# Titan_Teknic_v1p01c.net
KiCad netlist of a schematic drawn in EAGLE
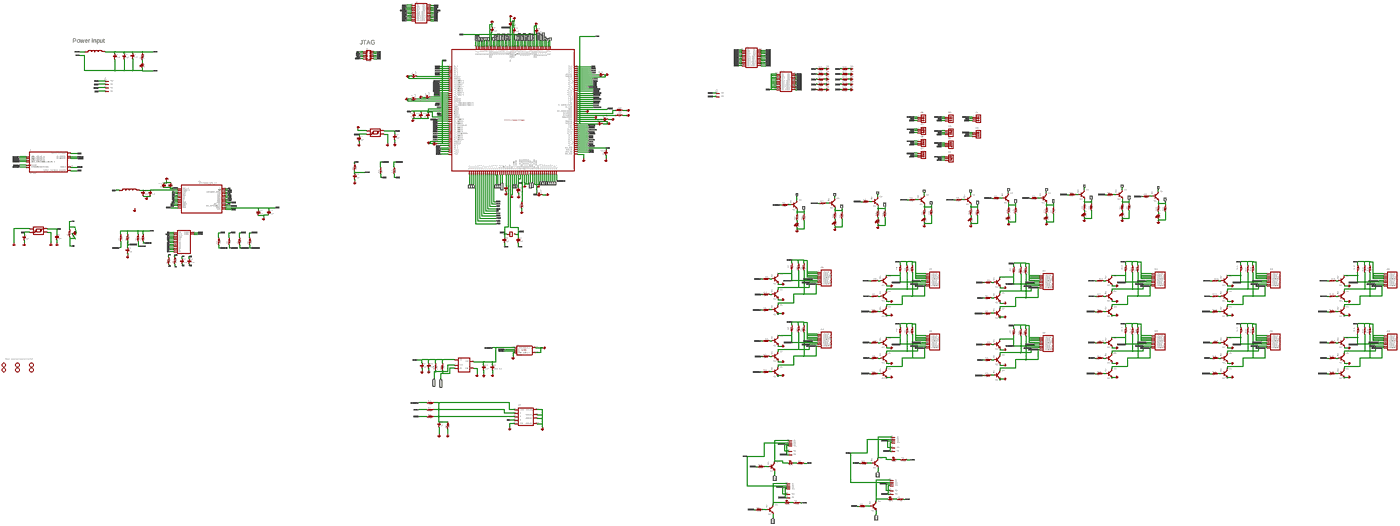
[diagram p0: schematic, sheet 1, overview]
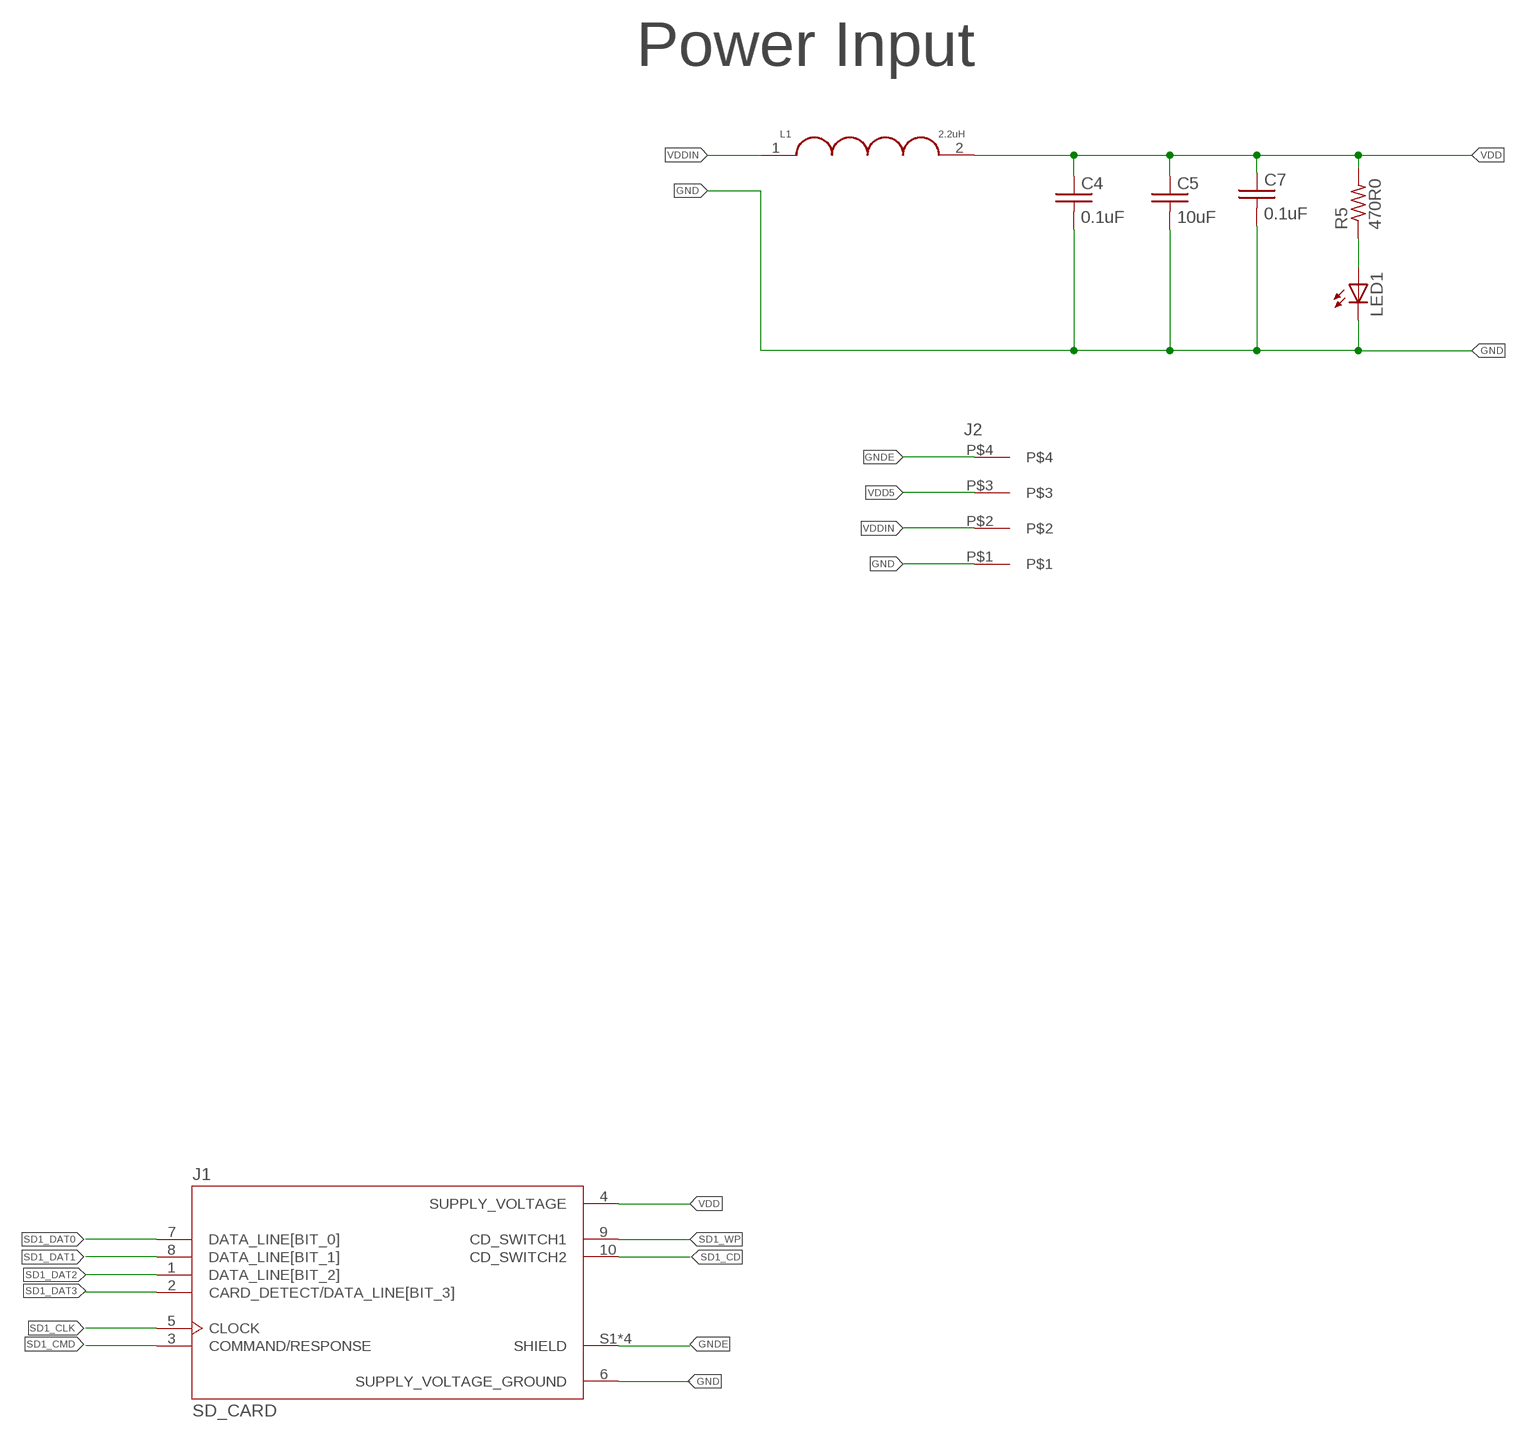
[diagram p1: schematic, sheet 1, part 1 of 9]
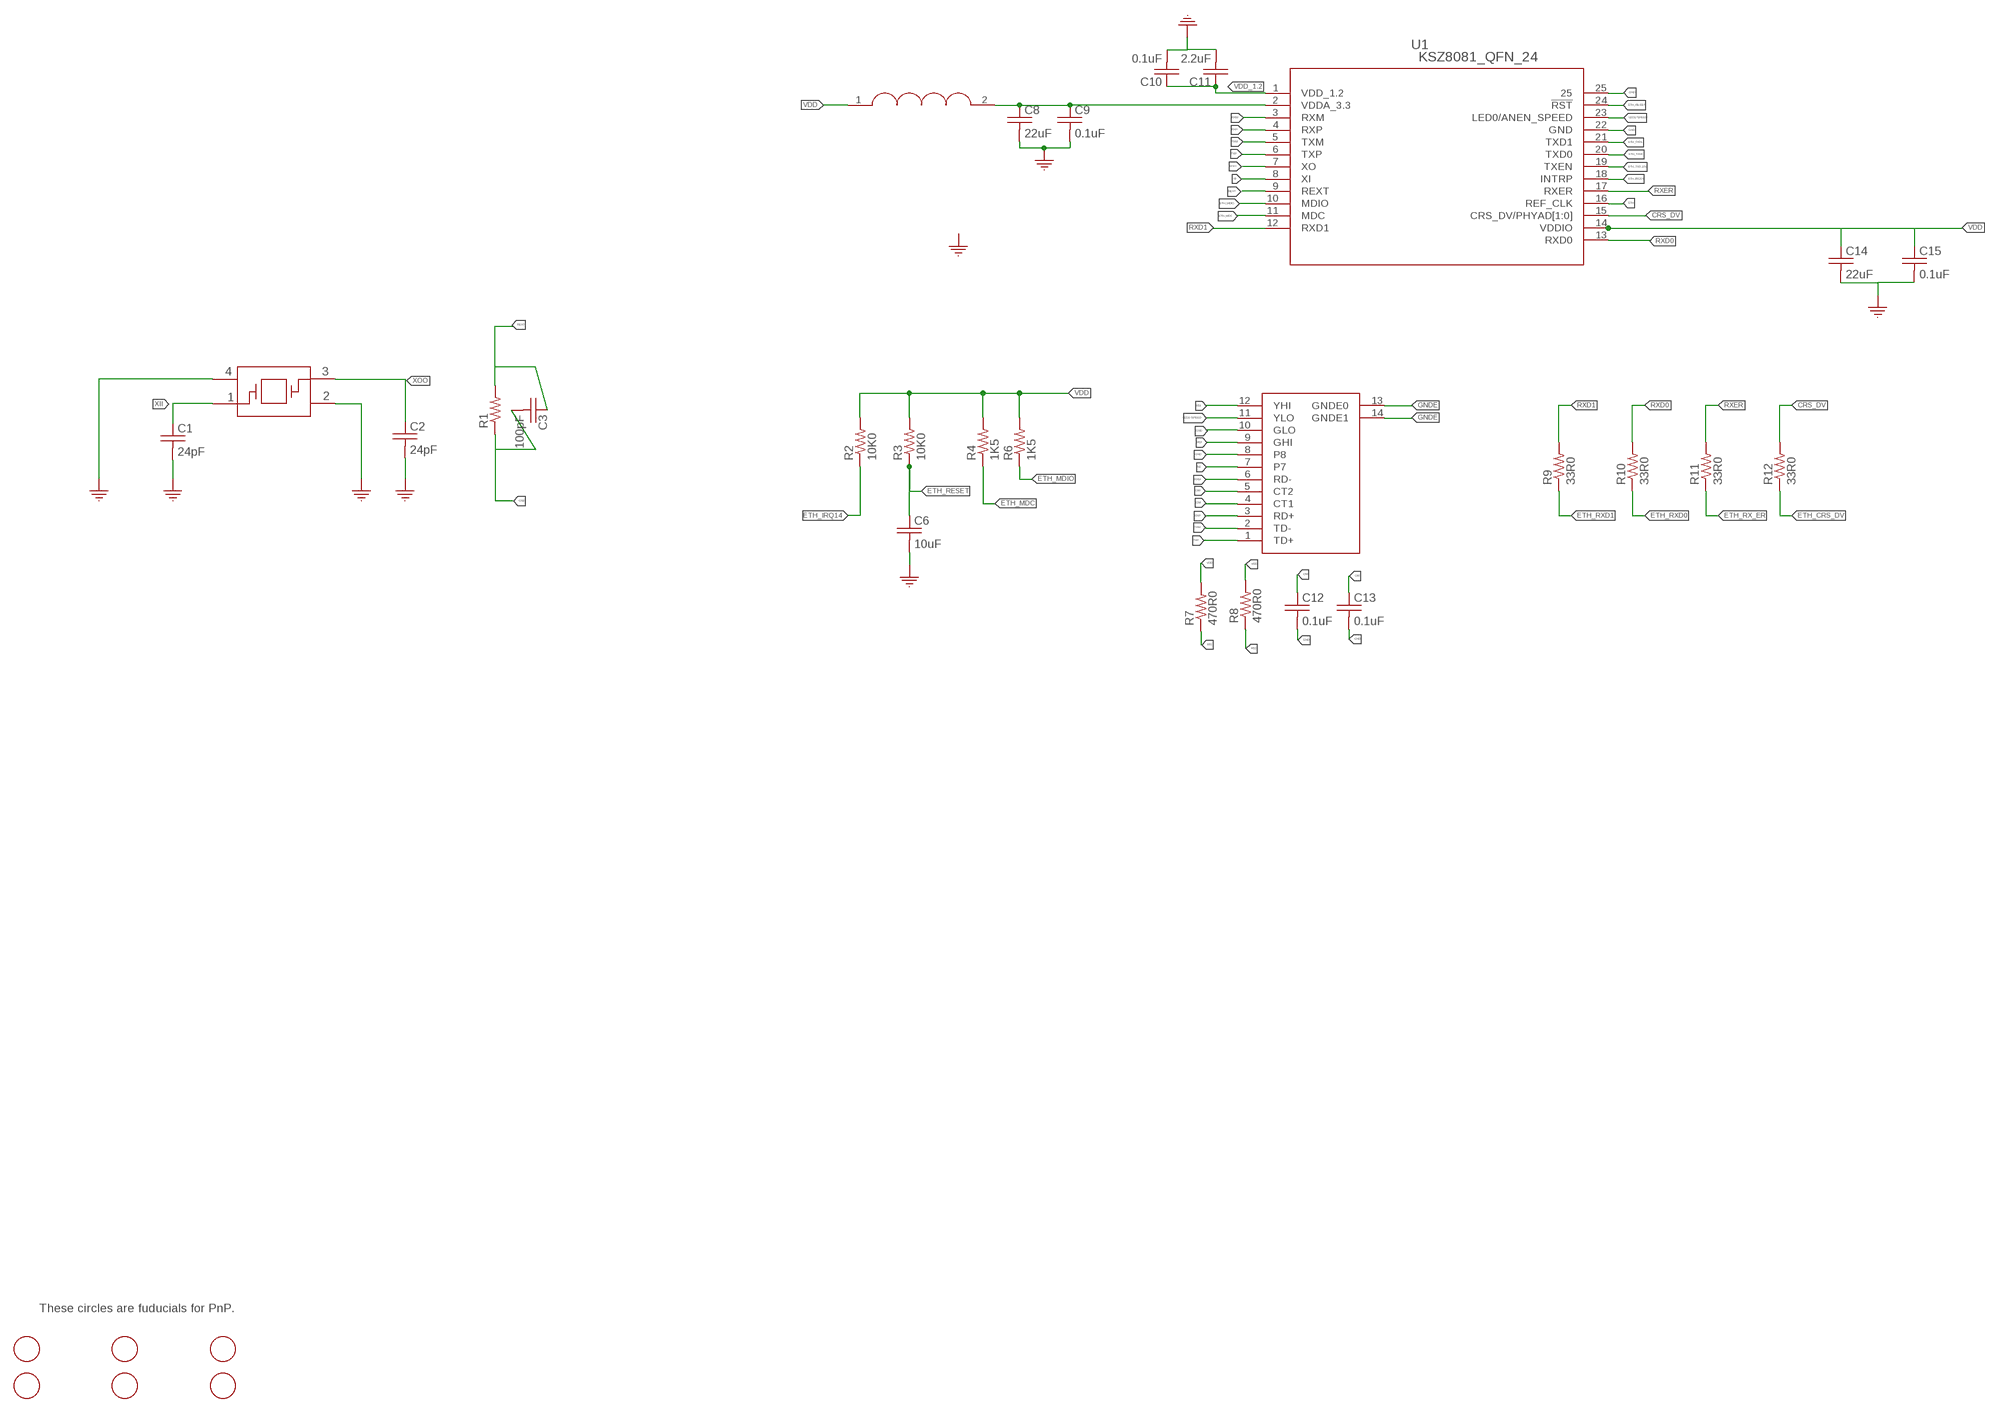
[diagram p2: schematic, sheet 1, part 2 of 9]
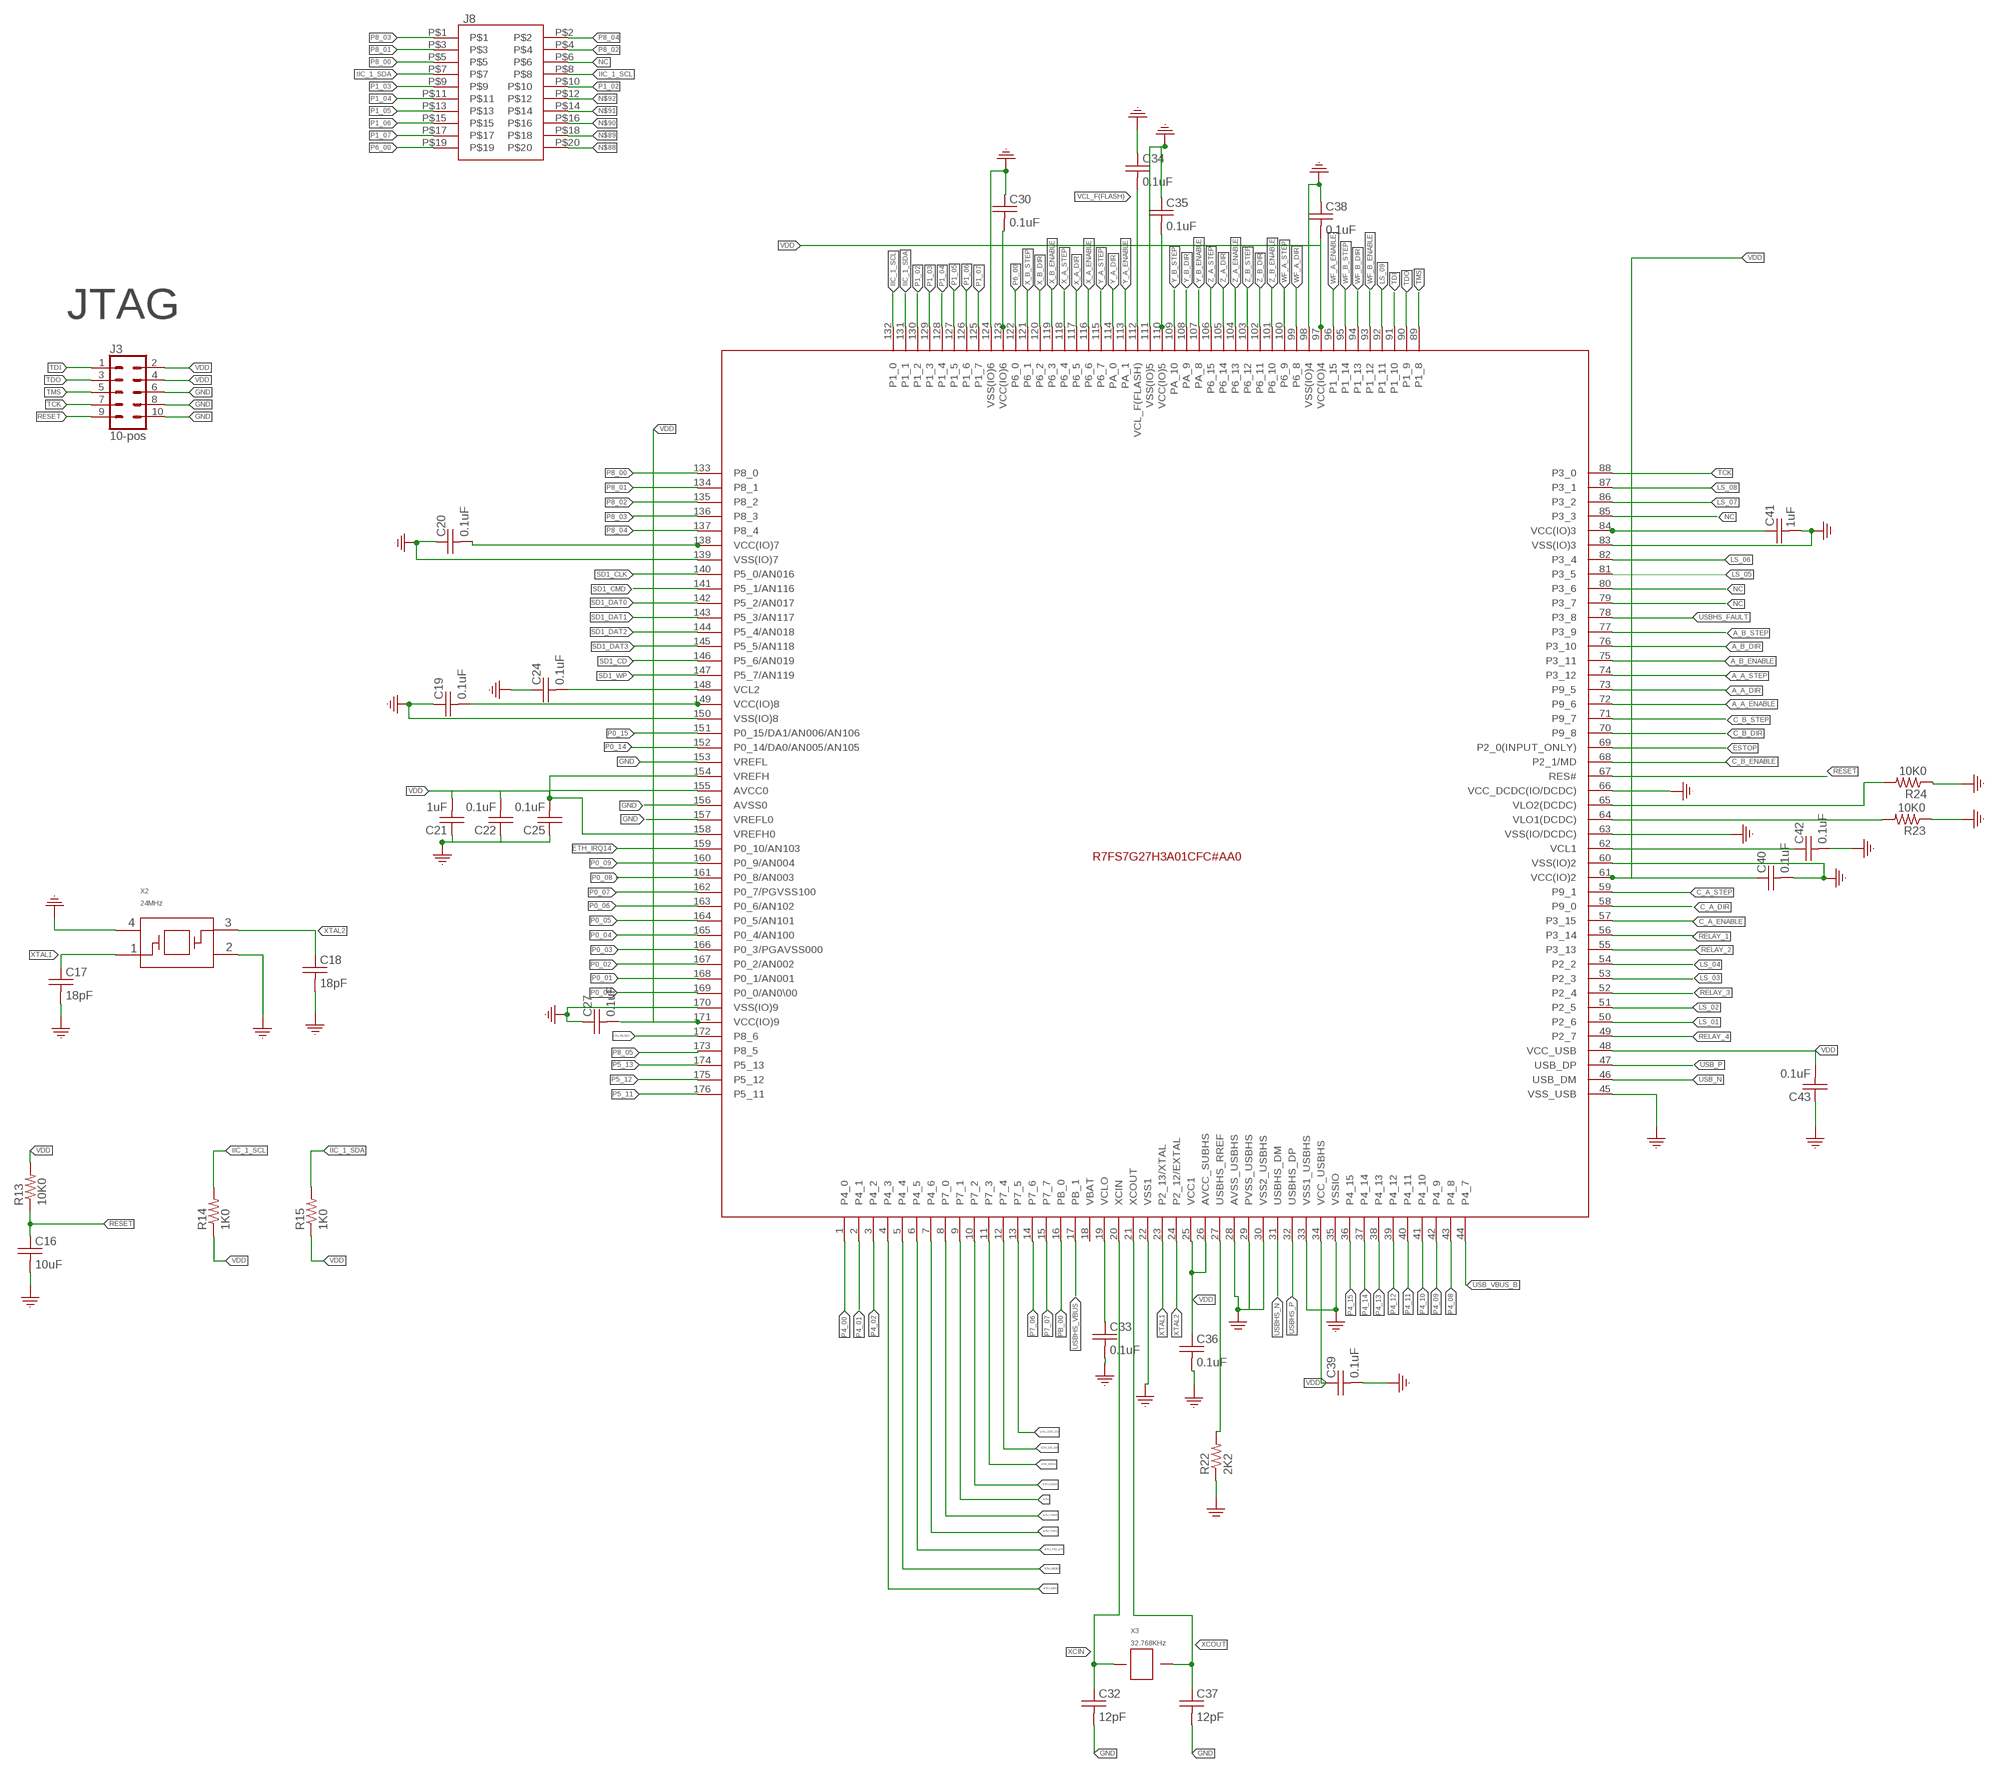
[diagram p3: schematic, sheet 1, part 3 of 9]
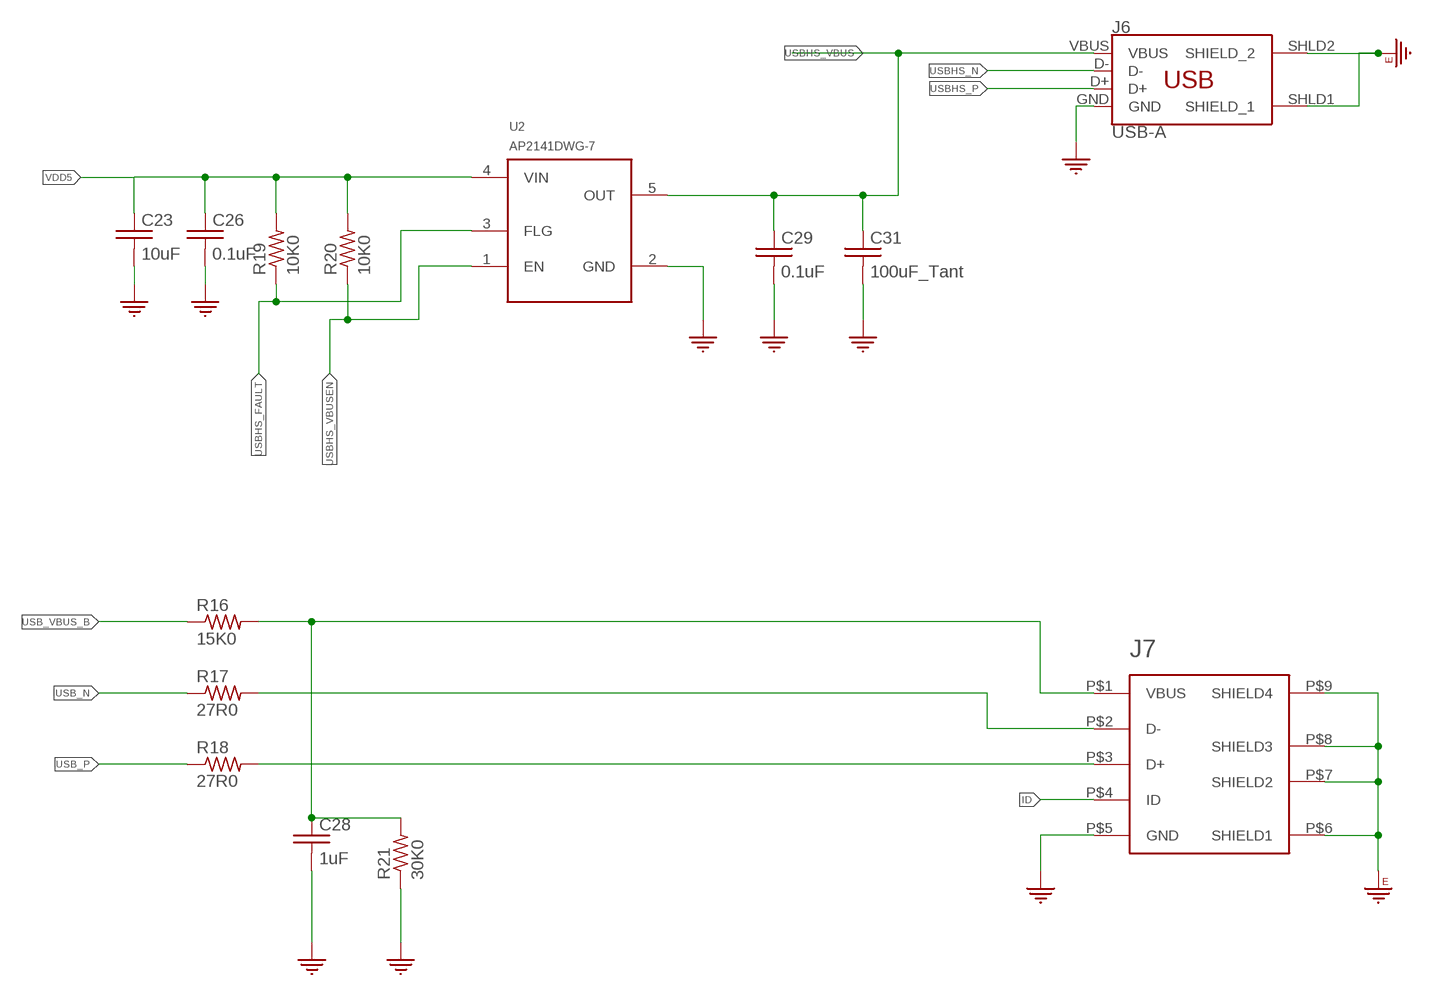
[diagram p4: schematic, sheet 1, part 4 of 9]
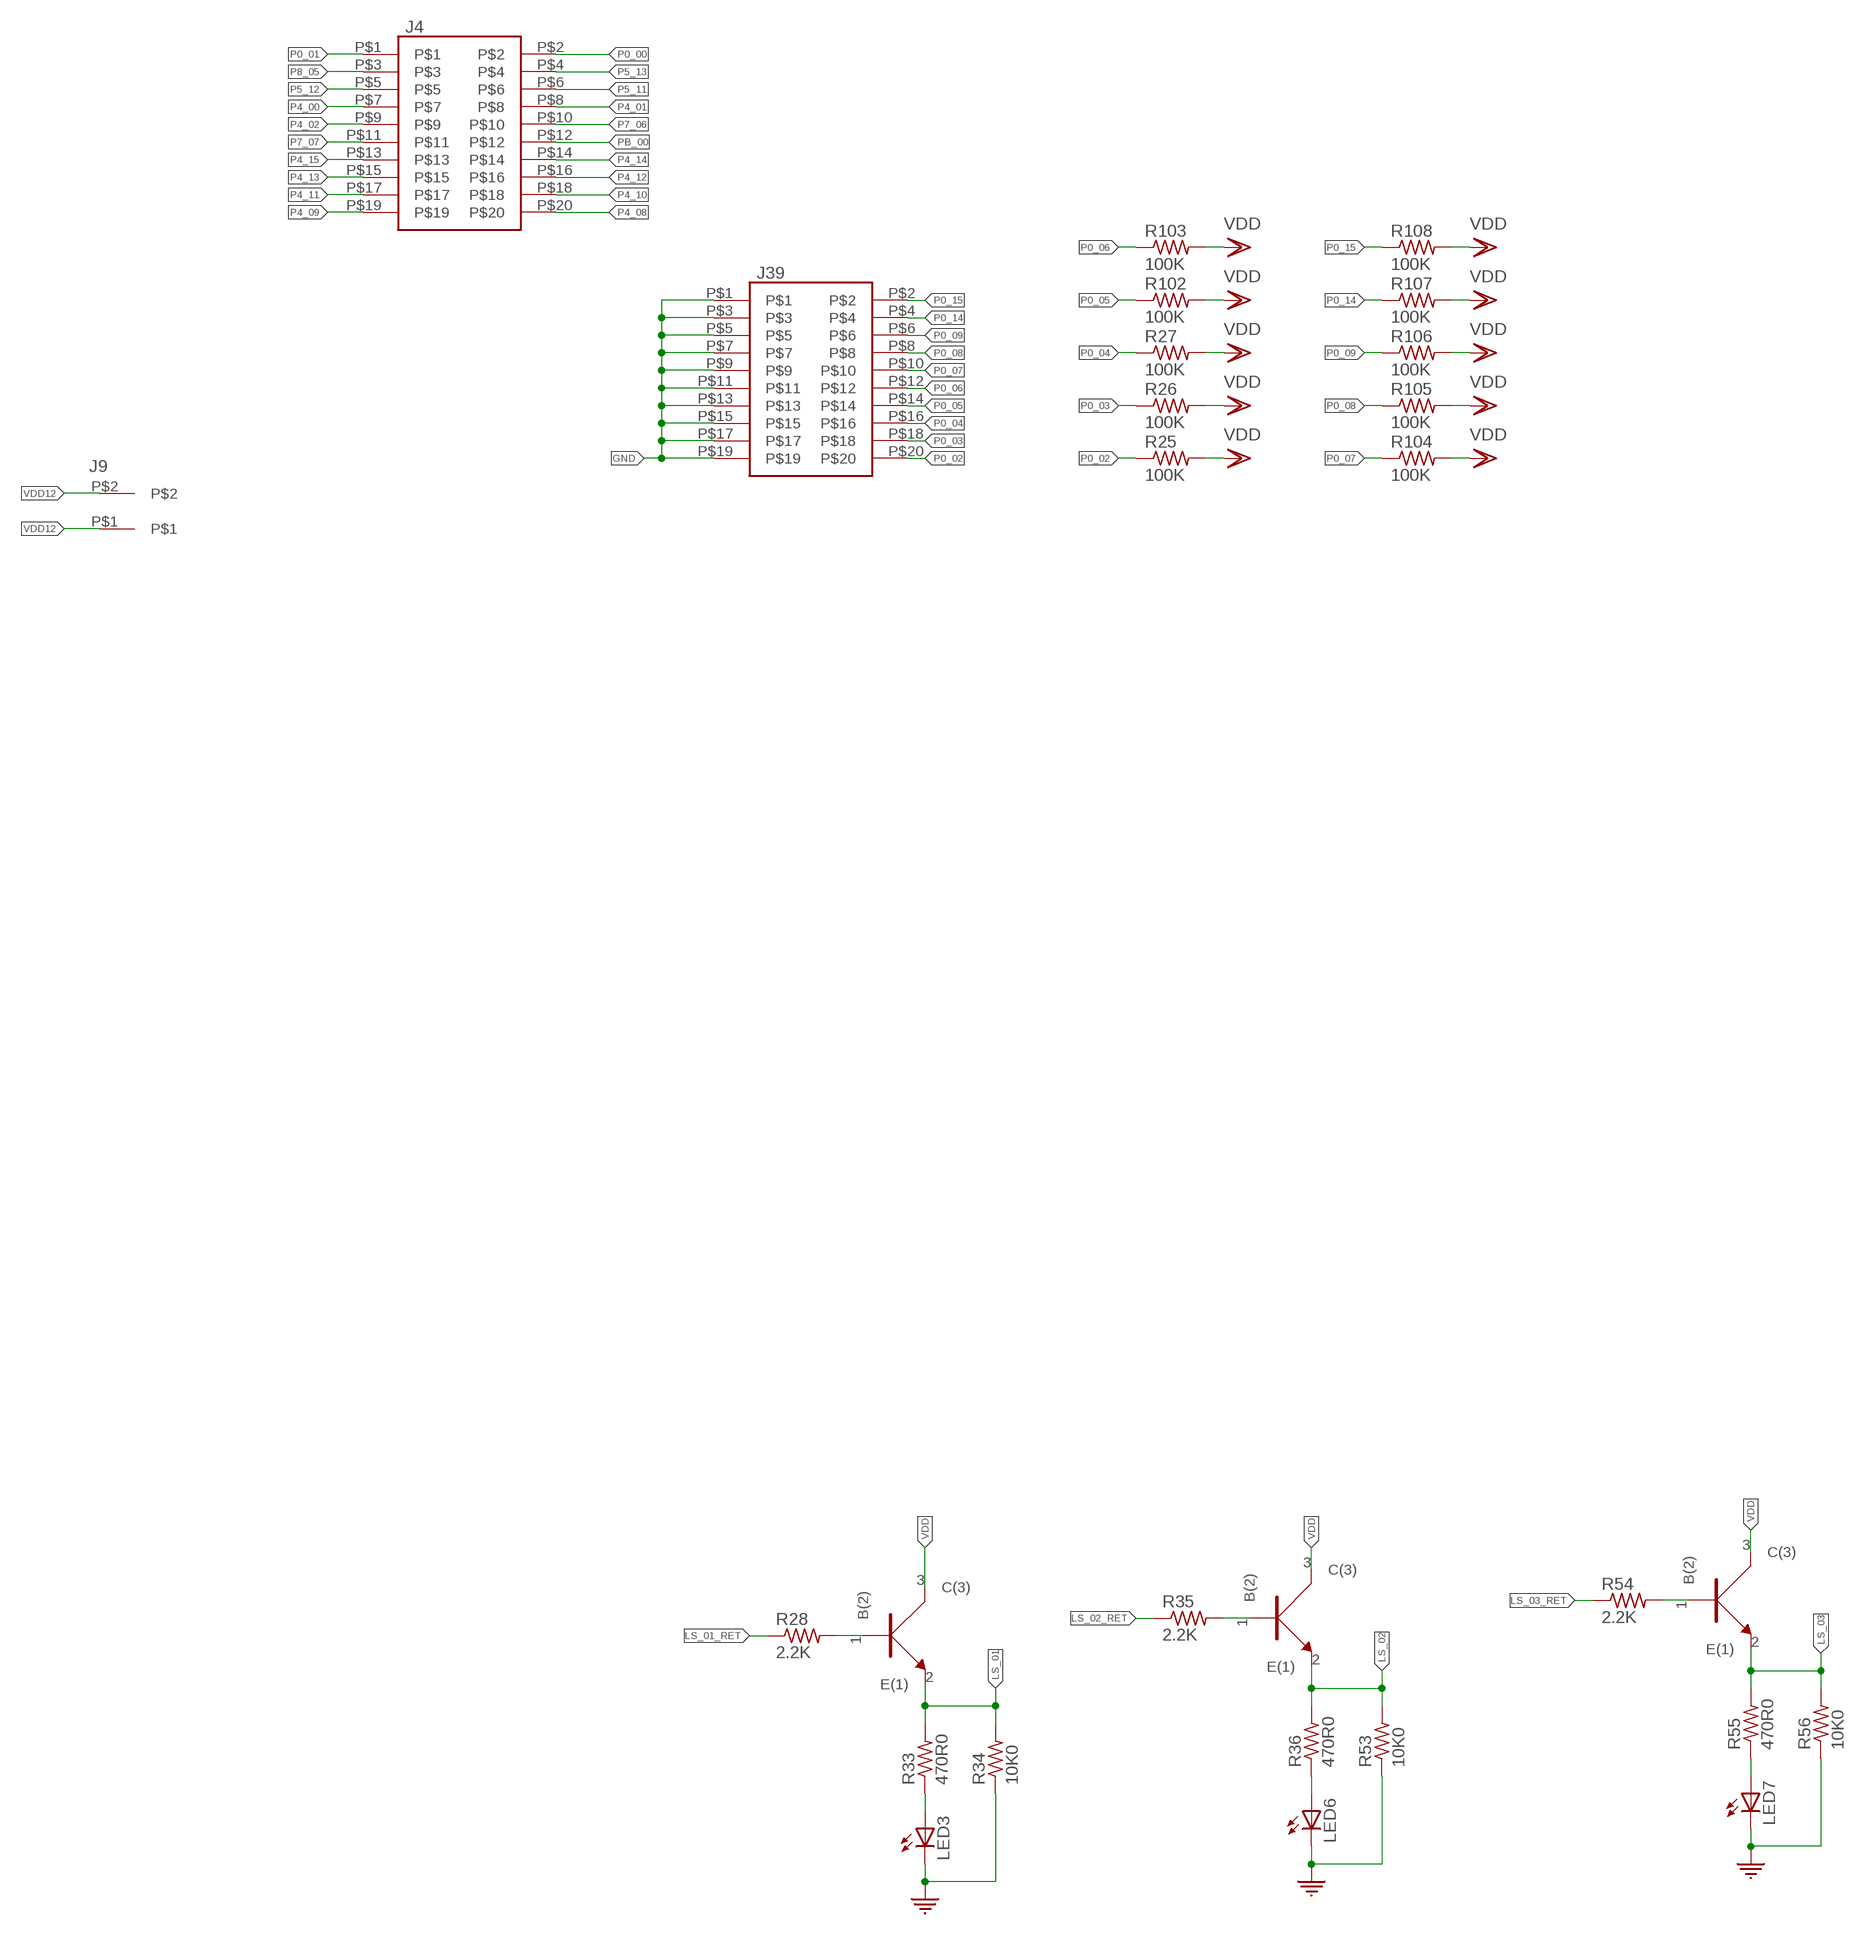
[diagram p5: schematic, sheet 1, part 5 of 9]
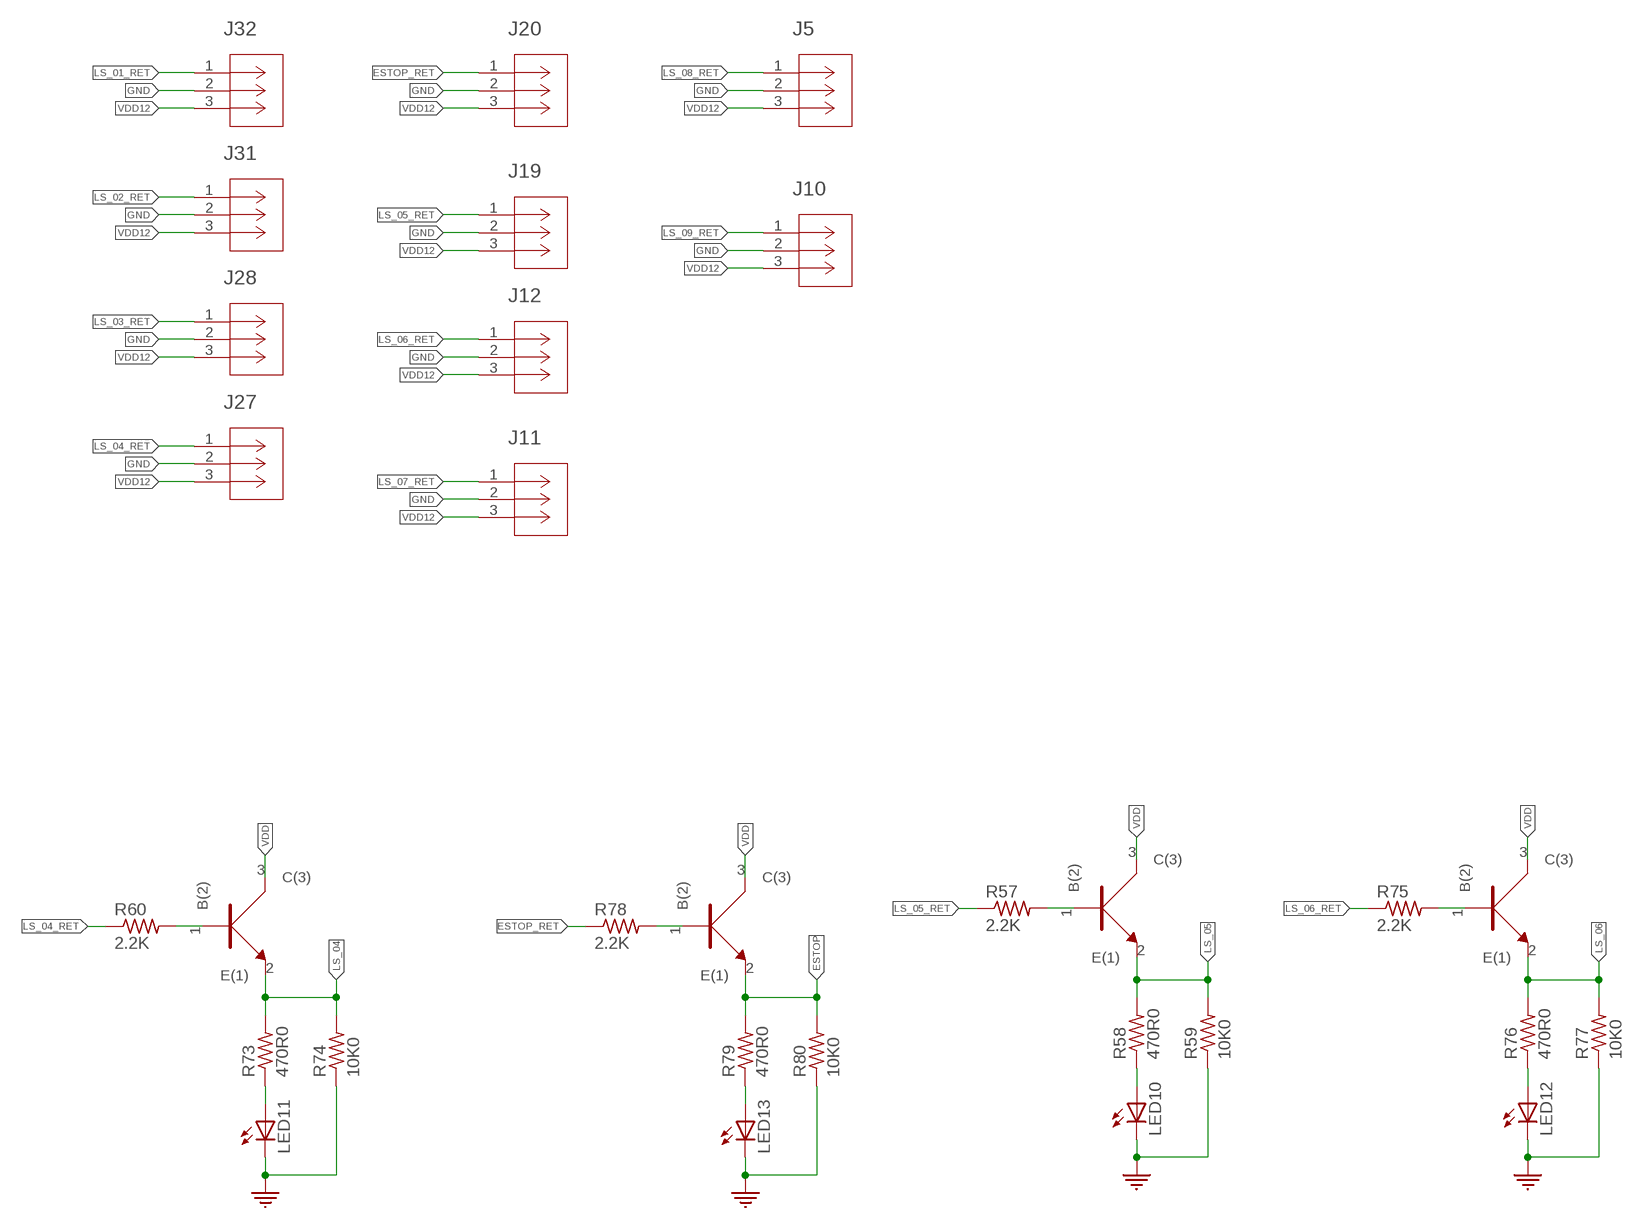
[diagram p6: schematic, sheet 1, part 6 of 9]
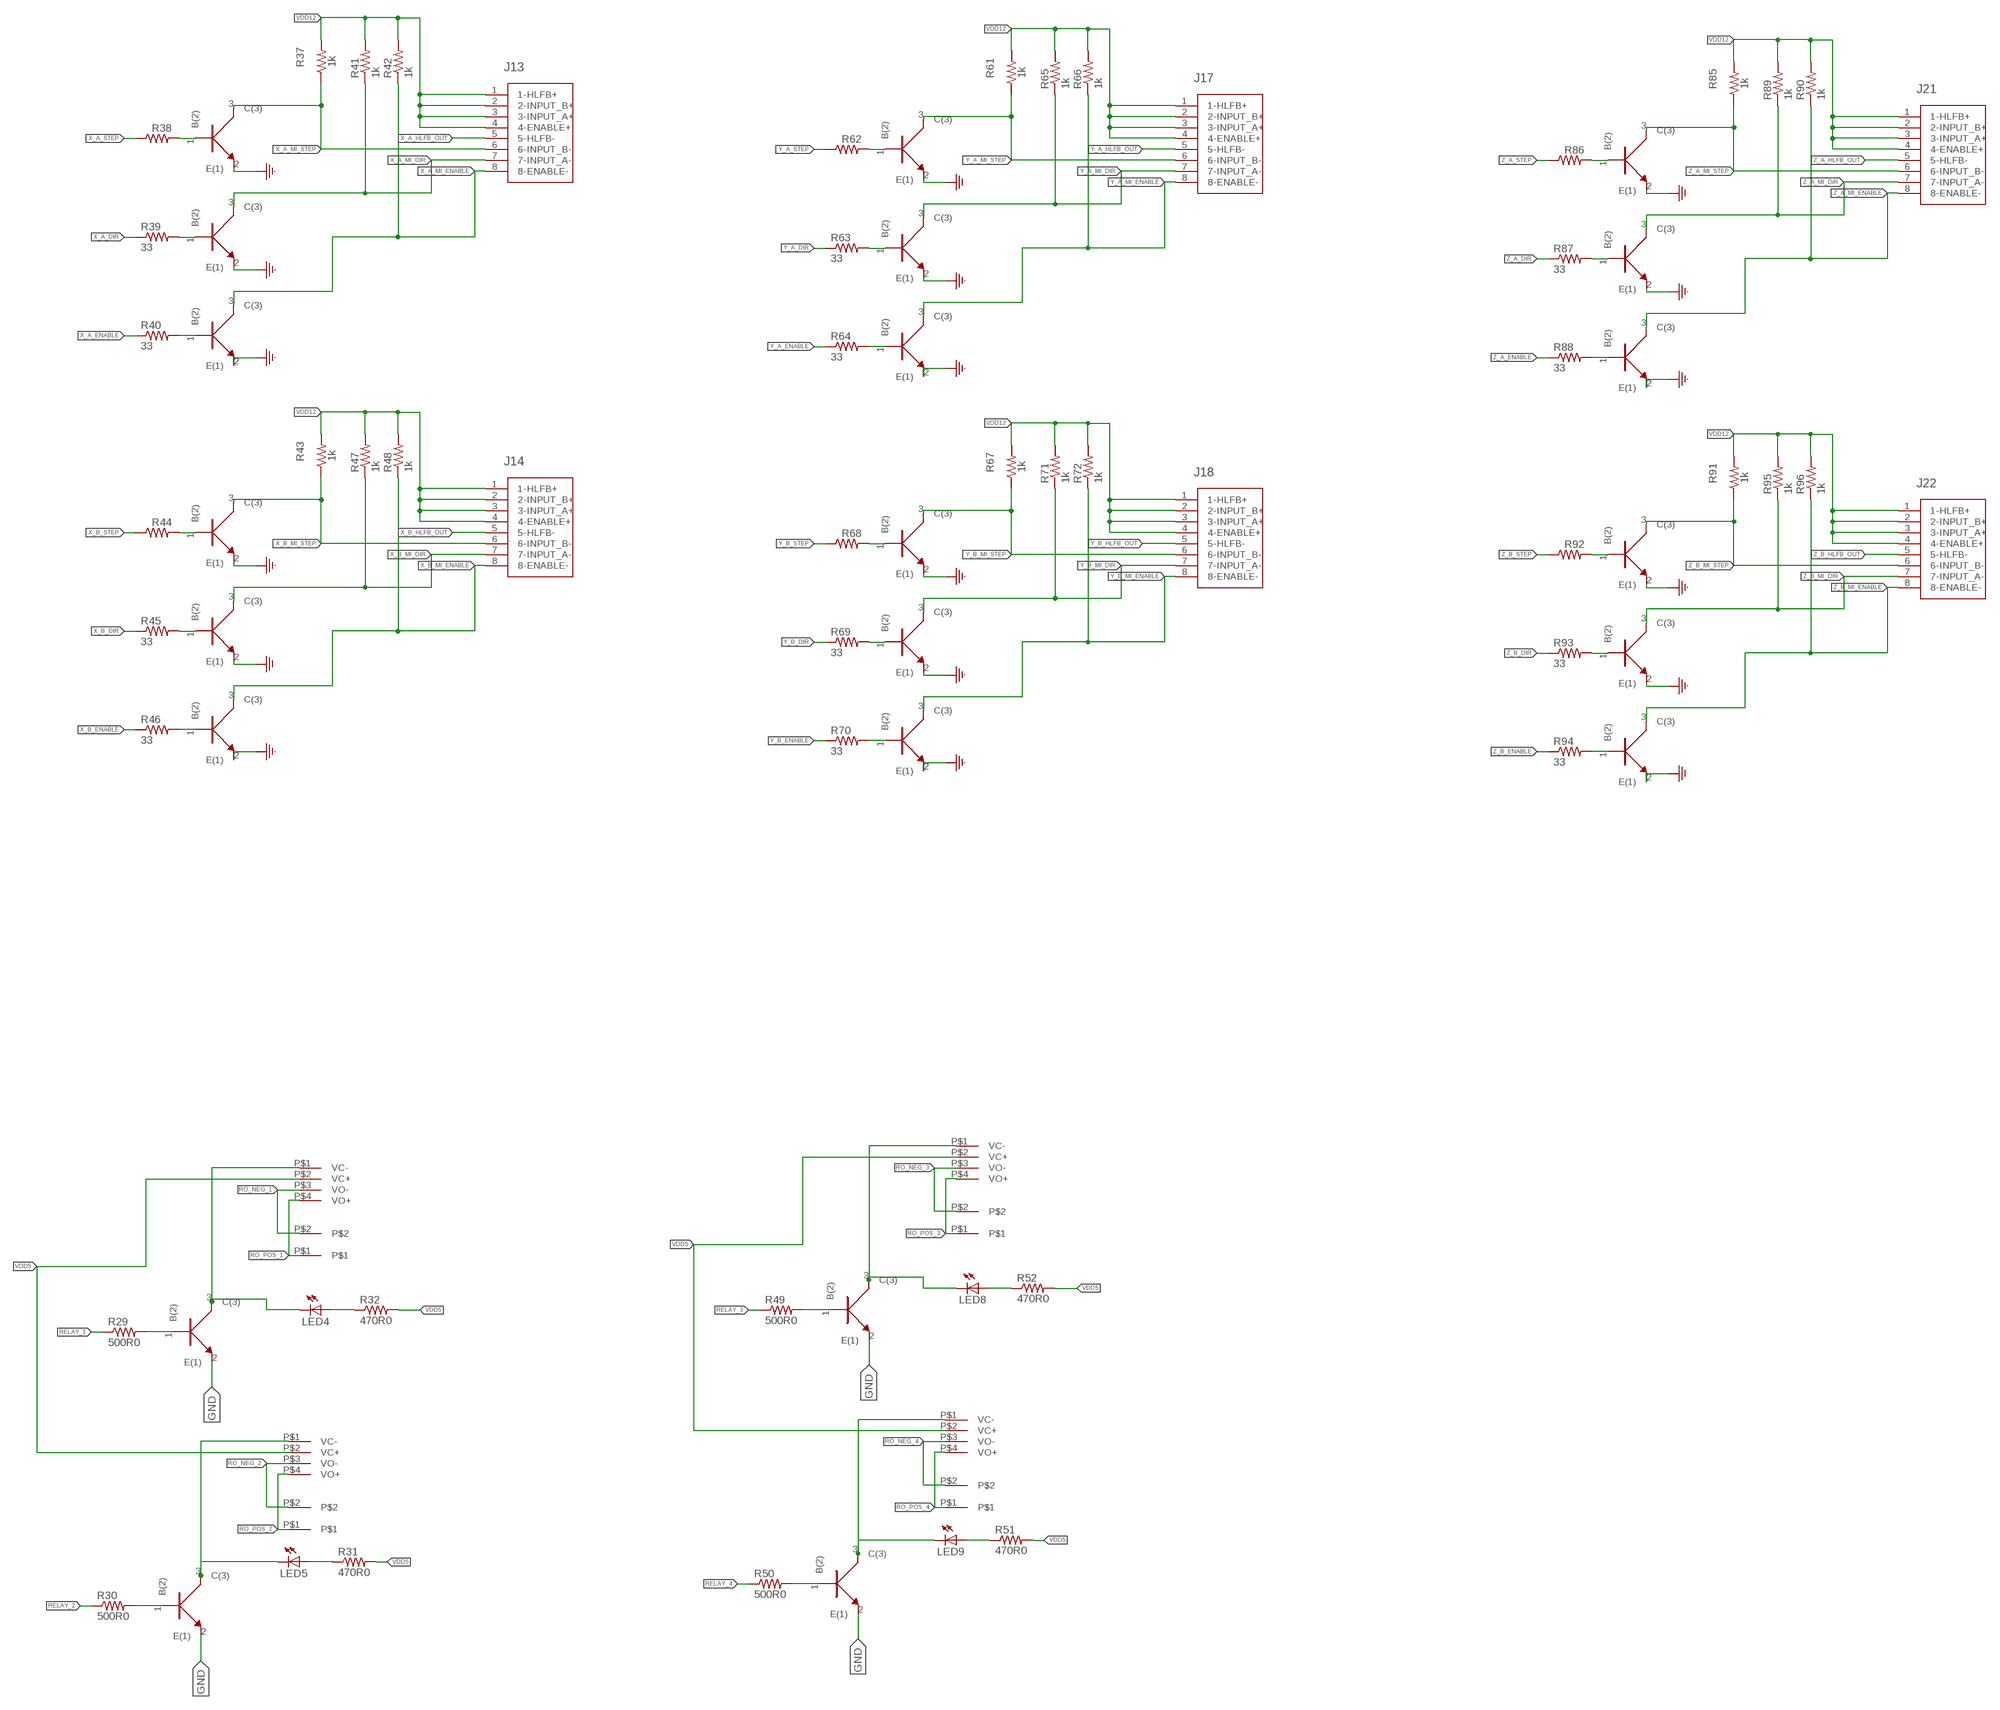
[diagram p7: schematic, sheet 1, part 7 of 9]
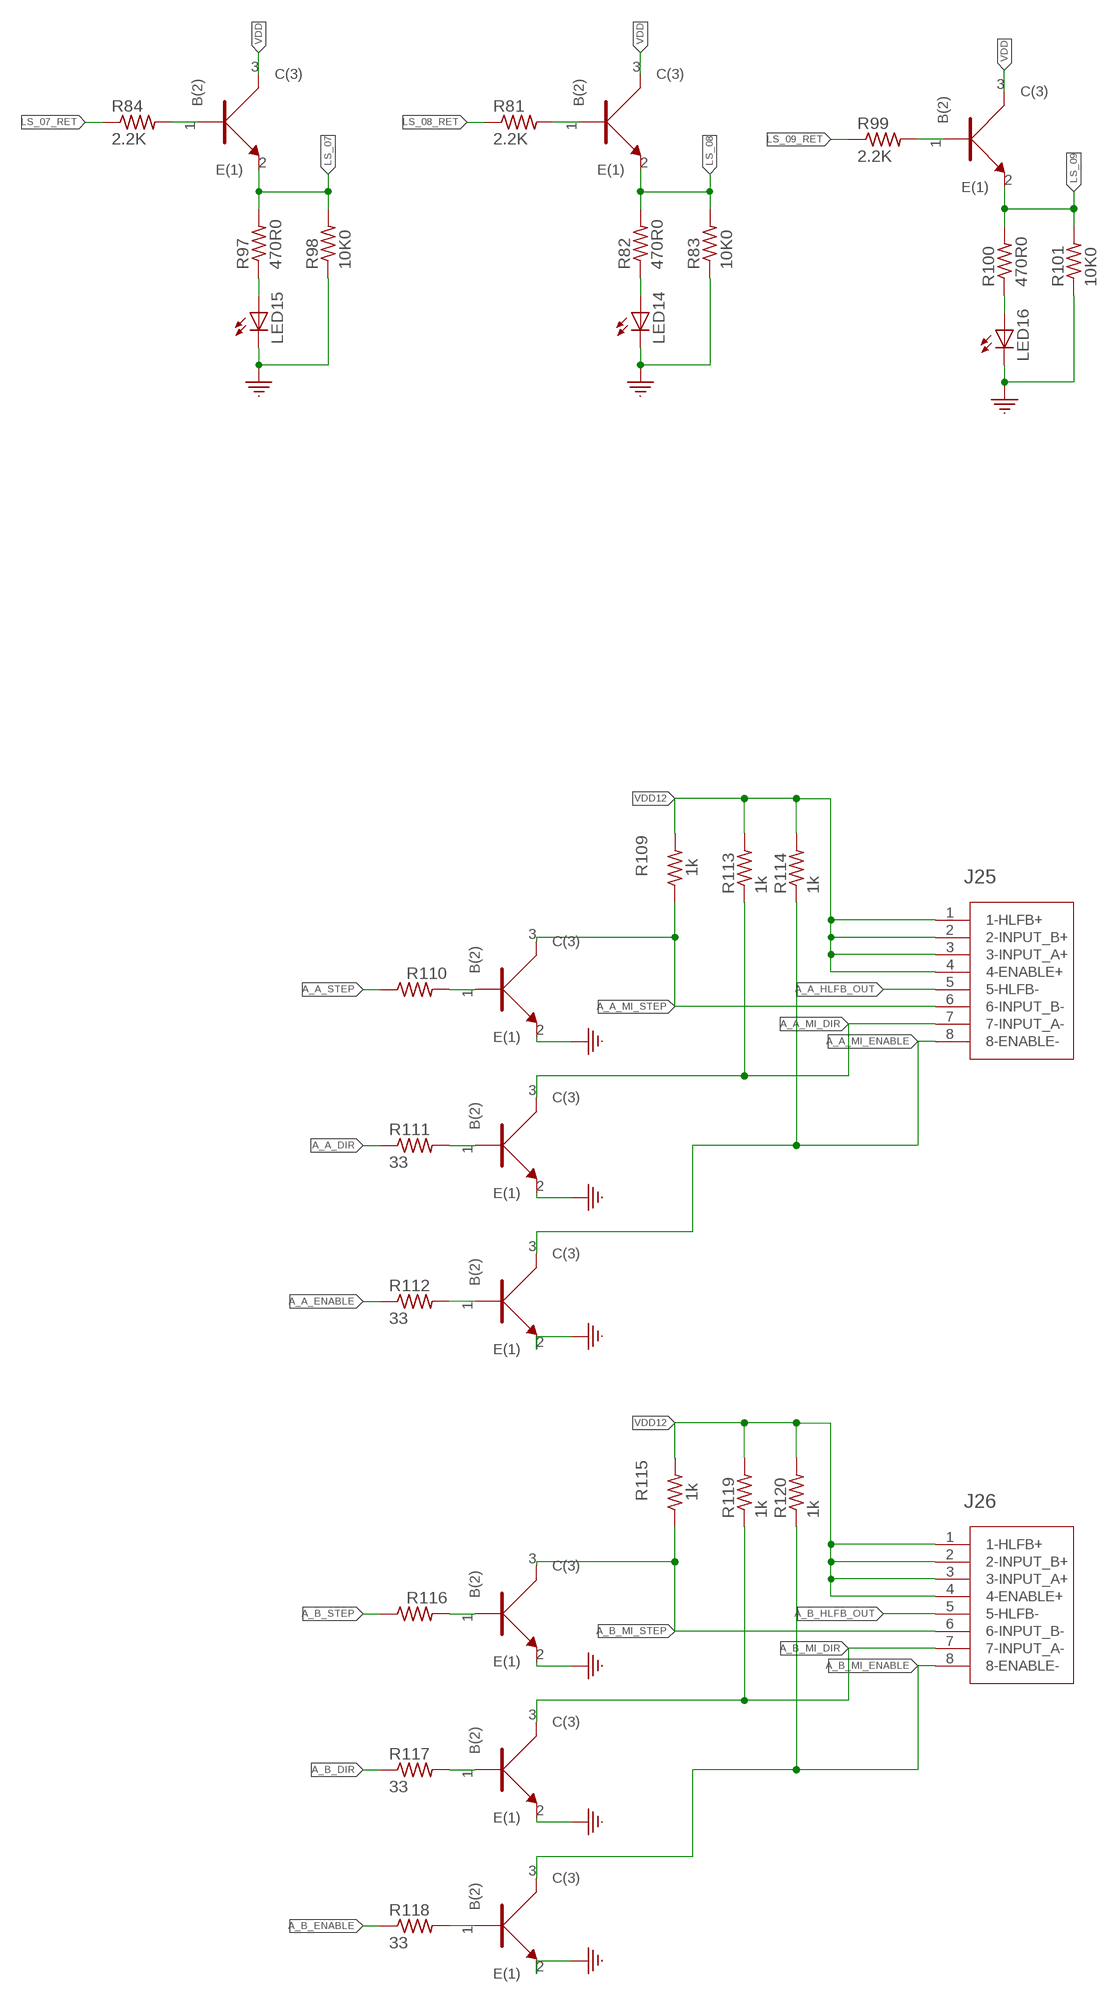
[diagram p8: schematic, sheet 1, part 8 of 9]
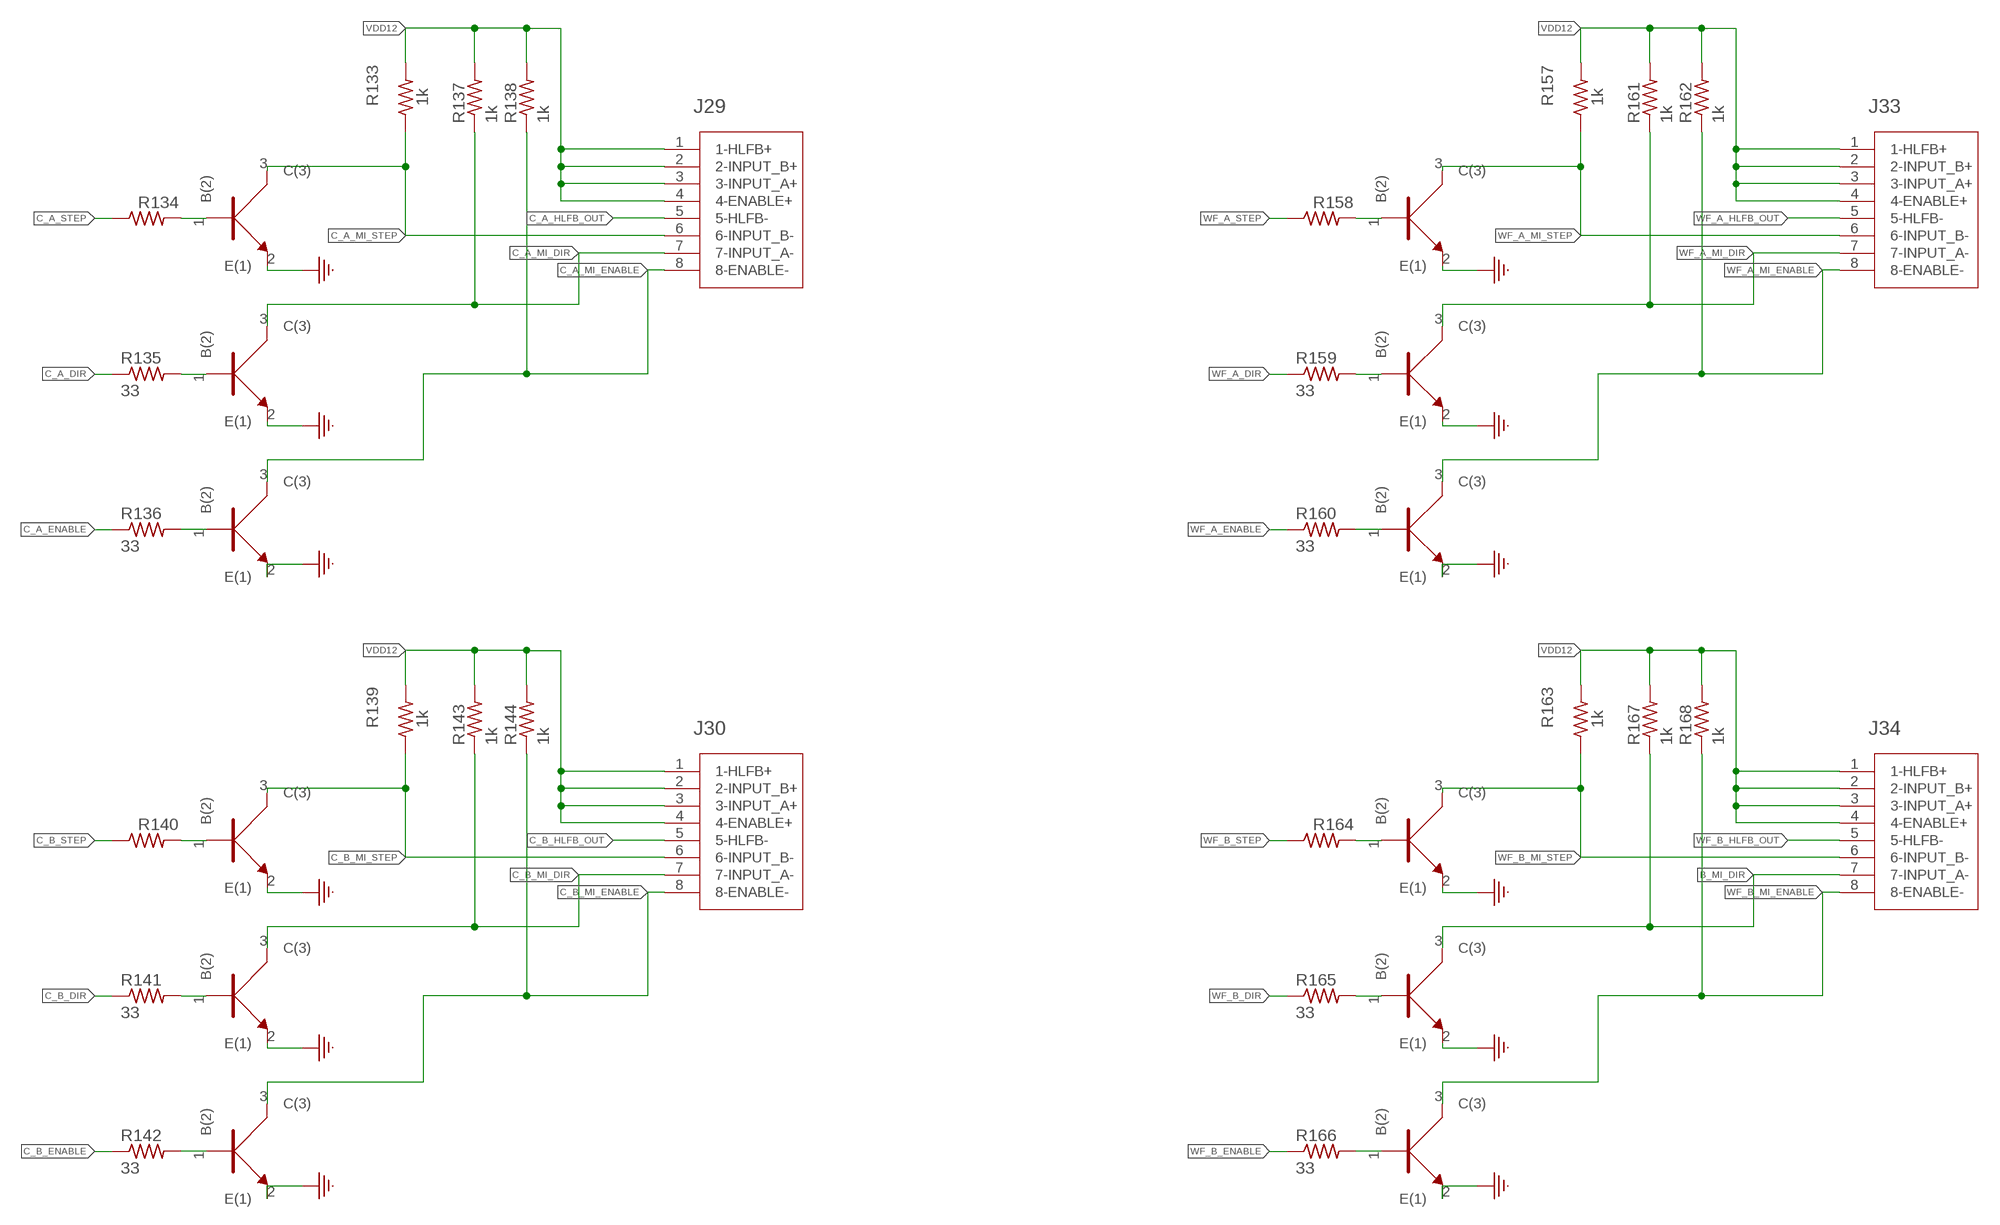
[diagram p9: schematic, sheet 1, part 9 of 9]

(export (version "E")
  (design (tool "Eeschema 10.0.6"))
  (components
    (comp (ref "AFID1")
      (value "FIDUCIAL_1MM")
      (footprint "eagle-import:FIDUCIAL_1MM")
      (libsource (lib "eagle-import") (part "FIDUCIAL_1MM"))
    )
    (comp (ref "AFID2")
      (value "FIDUCIAL_1MM")
      (footprint "eagle-import:FIDUCIAL_1MM")
      (libsource (lib "eagle-import") (part "FIDUCIAL_1MM"))
    )
    (comp (ref "AFID3")
      (value "FIDUCIAL_1MM")
      (footprint "eagle-import:FIDUCIAL_1MM")
      (libsource (lib "eagle-import") (part "FIDUCIAL_1MM"))
    )
    (comp (ref "AFID4")
      (value "FIDUCIAL_1MM")
      (footprint "eagle-import:FIDUCIAL_1MM")
      (libsource (lib "eagle-import") (part "FIDUCIAL_1MM"))
    )
    (comp (ref "AFID5")
      (value "FIDUCIAL_1MM")
      (footprint "eagle-import:FIDUCIAL_1MM")
      (libsource (lib "eagle-import") (part "FIDUCIAL_1MM"))
    )
    (comp (ref "AFID6")
      (value "FIDUCIAL_1MM")
      (footprint "eagle-import:FIDUCIAL_1MM")
      (libsource (lib "eagle-import") (part "FIDUCIAL_1MM"))
    )
    (comp (ref "C1")
      (value "24pF")
      (footprint "eagle-import:0402")
      (fields (field (name "PARTNO") "CC0402GRNPO9BN240"))
      (libsource (lib "eagle-import") (part "C_0402_24PF"))
    )
    (comp (ref "C2")
      (value "24pF")
      (footprint "eagle-import:0402")
      (fields (field (name "PARTNO") "CC0402GRNPO9BN240"))
      (libsource (lib "eagle-import") (part "C_0402_24PF"))
    )
    (comp (ref "C3")
      (value "100pF")
      (footprint "eagle-import:0402")
      (fields (field (name "PARTNO") "CL05C101JB5NNNC"))
      (libsource (lib "eagle-import") (part "C_0402_100PF"))
    )
    (comp (ref "C4")
      (value "0.1uF")
      (footprint "eagle-import:0402")
      (fields (field (name "PARTNO") "CL05F104ZO5NNNC"))
      (libsource (lib "eagle-import") (part "C_0402_0.1UF"))
    )
    (comp (ref "C5")
      (value "10uF")
      (footprint "eagle-import:0402")
      (fields (field (name "PARTNO") "CL05A106MP8NUB8"))
      (libsource (lib "eagle-import") (part "C_0402_10UF"))
    )
    (comp (ref "C6")
      (value "10uF")
      (footprint "eagle-import:0402")
      (fields (field (name "PARTNO") "CL05A106MP8NUB8"))
      (libsource (lib "eagle-import") (part "C_0402_10UF"))
    )
    (comp (ref "C7")
      (value "0.1uF")
      (footprint "eagle-import:0402")
      (fields (field (name "PARTNO") "CL05F104ZO5NNNC"))
      (libsource (lib "eagle-import") (part "C_0402_0.1UF"))
    )
    (comp (ref "C8")
      (value "22uF")
      (footprint "eagle-import:0402")
      (fields (field (name "PARTNO") "CL05A226MQ5N6J8"))
      (libsource (lib "eagle-import") (part "C_0402_22UF"))
    )
    (comp (ref "C9")
      (value "0.1uF")
      (footprint "eagle-import:0402")
      (fields (field (name "PARTNO") "CL05F104ZO5NNNC"))
      (libsource (lib "eagle-import") (part "C_0402_0.1UF"))
    )
    (comp (ref "C10")
      (value "0.1uF")
      (footprint "eagle-import:0402")
      (fields (field (name "PARTNO") "CL05F104ZO5NNNC"))
      (libsource (lib "eagle-import") (part "C_0402_0.1UF"))
    )
    (comp (ref "C11")
      (value "2.2uF")
      (footprint "eagle-import:0402")
      (fields (field (name "PARTNO") "GRM155C81C225ME15D"))
      (libsource (lib "eagle-import") (part "C_0402_2.2UF"))
    )
    (comp (ref "C12")
      (value "0.1uF")
      (footprint "eagle-import:0402")
      (fields (field (name "PARTNO") "CL05F104ZO5NNNC"))
      (libsource (lib "eagle-import") (part "C_0402_0.1UF"))
    )
    (comp (ref "C13")
      (value "0.1uF")
      (footprint "eagle-import:0402")
      (fields (field (name "PARTNO") "CL05F104ZO5NNNC"))
      (libsource (lib "eagle-import") (part "C_0402_0.1UF"))
    )
    (comp (ref "C14")
      (value "22uF")
      (footprint "eagle-import:0402")
      (fields (field (name "PARTNO") "CL05A226MQ5N6J8"))
      (libsource (lib "eagle-import") (part "C_0402_22UF"))
    )
    (comp (ref "C15")
      (value "0.1uF")
      (footprint "eagle-import:0402")
      (fields (field (name "PARTNO") "CL05F104ZO5NNNC"))
      (libsource (lib "eagle-import") (part "C_0402_0.1UF"))
    )
    (comp (ref "C16")
      (value "10uF")
      (footprint "eagle-import:0402")
      (fields (field (name "PARTNO") "CL05A106MP8NUB8"))
      (libsource (lib "eagle-import") (part "C_0402_10UF"))
    )
    (comp (ref "C17")
      (value "18pF")
      (footprint "eagle-import:0402")
      (fields (field (name "PARTNO") "UMK105CG180JV-F"))
      (libsource (lib "eagle-import") (part "C_0402_18PF"))
    )
    (comp (ref "C18")
      (value "18pF")
      (footprint "eagle-import:0402")
      (fields (field (name "PARTNO") "UMK105CG180JV-F"))
      (libsource (lib "eagle-import") (part "C_0402_18PF"))
    )
    (comp (ref "C19")
      (value "0.1uF")
      (footprint "eagle-import:0402")
      (fields (field (name "PARTNO") "CL05F104ZO5NNNC"))
      (libsource (lib "eagle-import") (part "C_0402_0.1UF"))
    )
    (comp (ref "C20")
      (value "0.1uF")
      (footprint "eagle-import:0402")
      (fields (field (name "PARTNO") "CL05F104ZO5NNNC"))
      (libsource (lib "eagle-import") (part "C_0402_0.1UF"))
    )
    (comp (ref "C21")
      (value "1uF")
      (footprint "eagle-import:0402")
      (fields (field (name "PARTNO") "CL05A105KO5NNNC"))
      (libsource (lib "eagle-import") (part "C_0402_1UF"))
    )
    (comp (ref "C22")
      (value "0.1uF")
      (footprint "eagle-import:0402")
      (fields (field (name "PARTNO") "CL05F104ZO5NNNC"))
      (libsource (lib "eagle-import") (part "C_0402_0.1UF"))
    )
    (comp (ref "C23")
      (value "10uF")
      (footprint "eagle-import:0402")
      (fields (field (name "PARTNO") "CL05A106MP8NUB8"))
      (libsource (lib "eagle-import") (part "C_0402_10UF"))
    )
    (comp (ref "C24")
      (value "0.1uF")
      (footprint "eagle-import:0402")
      (fields (field (name "PARTNO") "CL05F104ZO5NNNC"))
      (libsource (lib "eagle-import") (part "C_0402_0.1UF"))
    )
    (comp (ref "C25")
      (value "0.1uF")
      (footprint "eagle-import:0402")
      (fields (field (name "PARTNO") "CL05F104ZO5NNNC"))
      (libsource (lib "eagle-import") (part "C_0402_0.1UF"))
    )
    (comp (ref "C26")
      (value "0.1uF")
      (footprint "eagle-import:0402")
      (fields (field (name "PARTNO") "CL05F104ZO5NNNC"))
      (libsource (lib "eagle-import") (part "C_0402_0.1UF"))
    )
    (comp (ref "C27")
      (value "0.1uF")
      (footprint "eagle-import:0402")
      (fields (field (name "PARTNO") "CL05F104ZO5NNNC"))
      (libsource (lib "eagle-import") (part "C_0402_0.1UF"))
    )
    (comp (ref "C28")
      (value "1uF")
      (footprint "eagle-import:0402")
      (fields (field (name "PARTNO") "CL05A105KO5NNNC"))
      (libsource (lib "eagle-import") (part "C_0402_1UF"))
    )
    (comp (ref "C29")
      (value "0.1uF")
      (footprint "eagle-import:0402")
      (fields (field (name "PARTNO") "CL05F104ZO5NNNC"))
      (libsource (lib "eagle-import") (part "C_0402_0.1UF"))
    )
    (comp (ref "C30")
      (value "0.1uF")
      (footprint "eagle-import:0402")
      (fields (field (name "PARTNO") "CL05F104ZO5NNNC"))
      (libsource (lib "eagle-import") (part "C_0402_0.1UF"))
    )
    (comp (ref "C31")
      (value "100uF_Tant")
      (footprint "eagle-import:C1210")
      (fields (field (name "PARTNO") "TLJT107M010R0900"))
      (libsource (lib "eagle-import") (part "C_1210_100UF_TANT"))
    )
    (comp (ref "C32")
      (value "12pF")
      (footprint "eagle-import:0402")
      (fields (field (name "PARTNO") "CL05C120JB5NNNC"))
      (libsource (lib "eagle-import") (part "C_0402_12PF"))
    )
    (comp (ref "C33")
      (value "0.1uF")
      (footprint "eagle-import:0402")
      (fields (field (name "PARTNO") "CL05F104ZO5NNNC"))
      (libsource (lib "eagle-import") (part "C_0402_0.1UF"))
    )
    (comp (ref "C34")
      (value "0.1uF")
      (footprint "eagle-import:0402")
      (fields (field (name "PARTNO") "CL05F104ZO5NNNC"))
      (libsource (lib "eagle-import") (part "C_0402_0.1UF"))
    )
    (comp (ref "C35")
      (value "0.1uF")
      (footprint "eagle-import:0402")
      (fields (field (name "PARTNO") "CL05F104ZO5NNNC"))
      (libsource (lib "eagle-import") (part "C_0402_0.1UF"))
    )
    (comp (ref "C36")
      (value "0.1uF")
      (footprint "eagle-import:0402")
      (fields (field (name "PARTNO") "CL05F104ZO5NNNC"))
      (libsource (lib "eagle-import") (part "C_0402_0.1UF"))
    )
    (comp (ref "C37")
      (value "12pF")
      (footprint "eagle-import:0402")
      (fields (field (name "PARTNO") "CL05C120JB5NNNC"))
      (libsource (lib "eagle-import") (part "C_0402_12PF"))
    )
    (comp (ref "C38")
      (value "0.1uF")
      (footprint "eagle-import:0402")
      (fields (field (name "PARTNO") "CL05F104ZO5NNNC"))
      (libsource (lib "eagle-import") (part "C_0402_0.1UF"))
    )
    (comp (ref "C39")
      (value "0.1uF")
      (footprint "eagle-import:0402")
      (fields (field (name "PARTNO") "CL05F104ZO5NNNC"))
      (libsource (lib "eagle-import") (part "C_0402_0.1UF"))
    )
    (comp (ref "C40")
      (value "0.1uF")
      (footprint "eagle-import:0402")
      (fields (field (name "PARTNO") "CL05F104ZO5NNNC"))
      (libsource (lib "eagle-import") (part "C_0402_0.1UF"))
    )
    (comp (ref "C41")
      (value "1uF")
      (footprint "eagle-import:0402")
      (fields (field (name "PARTNO") "CL05A105KO5NNNC"))
      (libsource (lib "eagle-import") (part "C_0402_1UF"))
    )
    (comp (ref "C42")
      (value "0.1uF")
      (footprint "eagle-import:0402")
      (fields (field (name "PARTNO") "CL05F104ZO5NNNC"))
      (libsource (lib "eagle-import") (part "C_0402_0.1UF"))
    )
    (comp (ref "C43")
      (value "0.1uF")
      (footprint "eagle-import:0402")
      (fields (field (name "PARTNO") "CL05F104ZO5NNNC"))
      (libsource (lib "eagle-import") (part "C_0402_0.1UF"))
    )
    (comp (ref "FB1")
      (value "FB2_603")
      (footprint "eagle-import:0603")
      (fields (field (name "PARTNO") "BLM18PG121SN1D"))
      (libsource (lib "eagle-import") (part "FB_0603_120_OHM0603"))
    )
    (comp (ref "J1")
      (value "SD_CARD")
      (footprint "eagle-import:SD_CARD")
      (fields (field (name "MF") "Amphenol ICC") (field (name "PARTNO") "114-00841-68"))
      (libsource (lib "eagle-import") (part "SD_CARD_1140084168"))
    )
    (comp (ref "J2")
      (value "4-pos")
      (footprint "eagle-import:1X4_3.81MM_PITCH")
      (fields (field (name "PARTNO") "691322310004"))
      (libsource (lib "eagle-import") (part "3.81MM_1_X_4_RT_ANGLE_PLUG_HEADER"))
    )
    (comp (ref "J3")
      (value "10-pos")
      (footprint "eagle-import:2X5")
      (fields (field (name "PARTNO") "PH2RA-10-UA"))
      (libsource (lib "eagle-import") (part "CONN_05X2_RAPTH"))
    )
    (comp (ref "J4")
      (value "20-pos")
      (footprint "eagle-import:2_X_10_.1_INCH")
      (fields (field (name "PARTNO") "67996-420HLF"))
      (libsource (lib "eagle-import") (part "2_X_10_HEADER_GENERIC"))
    )
    (comp (ref "J5")
      (value "CONN_530470310_PICOBLADE_X_3")
      (footprint "eagle-import:CON_530470310_MOL")
      (fields
        (field (name "MANUFACTURER_PART_NUMBER") "530470310")
        (field (name "COPYRIGHT") "Copyright (C) 2022 Ultra Librarian. All rights reserved.")
      )
      (libsource (lib "eagle-import") (part "CONN_530470310_PICOBLADE_X_3"))
    )
    (comp (ref "J6")
      (value "USB-A")
      (footprint "eagle-import:USB_A_SMT")
      (fields (field (name "PARTNO") "87583-3010RPALF"))
      (libsource (lib "eagle-import") (part "USB_A"))
    )
    (comp (ref "J7")
      (value "USB-B-Micro")
      (footprint "eagle-import:USB_MICRO-B")
      (fields (field (name "PARTNO") "10118192-0002LF"))
      (libsource (lib "eagle-import") (part "USB_MICRO-B"))
    )
    (comp (ref "J8")
      (value "2_X_10_HEADER_GENERIC")
      (footprint "eagle-import:2_X_10_.1_INCH")
      (fields (field (name "PARTNO") "67996-420HLF"))
      (libsource (lib "eagle-import") (part "2_X_10_HEADER_GENERIC"))
    )
    (comp (ref "J9")
      (value "2-pos")
      (footprint "eagle-import:2_3.81MM_PITCH")
      (fields (field (name "PARTNO") "691322310002"))
      (libsource (lib "eagle-import") (part "3.81MM_1_X_2_RT_ANGLE_PLUG_HEADER"))
    )
    (comp (ref "J10")
      (value "CONN_530470310_PICOBLADE_X_3")
      (footprint "eagle-import:CON_530470310_MOL")
      (fields
        (field (name "MANUFACTURER_PART_NUMBER") "530470310")
        (field (name "COPYRIGHT") "Copyright (C) 2022 Ultra Librarian. All rights reserved.")
      )
      (libsource (lib "eagle-import") (part "CONN_530470310_PICOBLADE_X_3"))
    )
    (comp (ref "J11")
      (value "CONN_530470310_PICOBLADE_X_3")
      (footprint "eagle-import:CON_530470310_MOL")
      (fields
        (field (name "MANUFACTURER_PART_NUMBER") "530470310")
        (field (name "COPYRIGHT") "Copyright (C) 2022 Ultra Librarian. All rights reserved.")
      )
      (libsource (lib "eagle-import") (part "CONN_530470310_PICOBLADE_X_3"))
    )
    (comp (ref "J12")
      (value "CONN_530470310_PICOBLADE_X_3")
      (footprint "eagle-import:CON_530470310_MOL")
      (fields
        (field (name "MANUFACTURER_PART_NUMBER") "530470310")
        (field (name "COPYRIGHT") "Copyright (C) 2022 Ultra Librarian. All rights reserved.")
      )
      (libsource (lib "eagle-import") (part "CONN_530470310_PICOBLADE_X_3"))
    )
    (comp (ref "J13")
      (value "TEKNIC_MOTOR_8PIN")
      (footprint "eagle-import:CON_39281083")
      (fields
        (field (name "MANUFACTURER_PART_NUMBER") "39281083")
        (field (name "COPYRIGHT") "Copyright (C) 2022 Ultra Librarian. All rights reserved.")
      )
      (libsource (lib "eagle-import") (part "TEKNIC_MOTOR_8PIN"))
    )
    (comp (ref "J14")
      (value "TEKNIC_MOTOR_8PIN")
      (footprint "eagle-import:CON_39281083")
      (fields
        (field (name "MANUFACTURER_PART_NUMBER") "39281083")
        (field (name "COPYRIGHT") "Copyright (C) 2022 Ultra Librarian. All rights reserved.")
      )
      (libsource (lib "eagle-import") (part "TEKNIC_MOTOR_8PIN"))
    )
    (comp (ref "J15")
      (value "2-pos")
      (footprint "eagle-import:2_3.81MM_PITCH")
      (fields (field (name "PARTNO") "691322310002"))
      (libsource (lib "eagle-import") (part "3.81MM_1_X_2_RT_ANGLE_PLUG_HEADER"))
    )
    (comp (ref "J16")
      (value "2-pos")
      (footprint "eagle-import:2_3.81MM_PITCH")
      (fields (field (name "PARTNO") "691322310002"))
      (libsource (lib "eagle-import") (part "3.81MM_1_X_2_RT_ANGLE_PLUG_HEADER"))
    )
    (comp (ref "J17")
      (value "TEKNIC_MOTOR_8PIN")
      (footprint "eagle-import:CON_39281083")
      (fields
        (field (name "MANUFACTURER_PART_NUMBER") "39281083")
        (field (name "COPYRIGHT") "Copyright (C) 2022 Ultra Librarian. All rights reserved.")
      )
      (libsource (lib "eagle-import") (part "TEKNIC_MOTOR_8PIN"))
    )
    (comp (ref "J18")
      (value "TEKNIC_MOTOR_8PIN")
      (footprint "eagle-import:CON_39281083")
      (fields
        (field (name "MANUFACTURER_PART_NUMBER") "39281083")
        (field (name "COPYRIGHT") "Copyright (C) 2022 Ultra Librarian. All rights reserved.")
      )
      (libsource (lib "eagle-import") (part "TEKNIC_MOTOR_8PIN"))
    )
    (comp (ref "J19")
      (value "CONN_530470310_PICOBLADE_X_3")
      (footprint "eagle-import:CON_530470310_MOL")
      (fields
        (field (name "MANUFACTURER_PART_NUMBER") "530470310")
        (field (name "COPYRIGHT") "Copyright (C) 2022 Ultra Librarian. All rights reserved.")
      )
      (libsource (lib "eagle-import") (part "CONN_530470310_PICOBLADE_X_3"))
    )
    (comp (ref "J20")
      (value "CONN_530470310_PICOBLADE_X_3")
      (footprint "eagle-import:CON_530470310_MOL")
      (fields
        (field (name "MANUFACTURER_PART_NUMBER") "530470310")
        (field (name "COPYRIGHT") "Copyright (C) 2022 Ultra Librarian. All rights reserved.")
      )
      (libsource (lib "eagle-import") (part "CONN_530470310_PICOBLADE_X_3"))
    )
    (comp (ref "J21")
      (value "TEKNIC_MOTOR_8PIN")
      (footprint "eagle-import:CON_39281083")
      (fields
        (field (name "MANUFACTURER_PART_NUMBER") "39281083")
        (field (name "COPYRIGHT") "Copyright (C) 2022 Ultra Librarian. All rights reserved.")
      )
      (libsource (lib "eagle-import") (part "TEKNIC_MOTOR_8PIN"))
    )
    (comp (ref "J22")
      (value "TEKNIC_MOTOR_8PIN")
      (footprint "eagle-import:CON_39281083")
      (fields
        (field (name "MANUFACTURER_PART_NUMBER") "39281083")
        (field (name "COPYRIGHT") "Copyright (C) 2022 Ultra Librarian. All rights reserved.")
      )
      (libsource (lib "eagle-import") (part "TEKNIC_MOTOR_8PIN"))
    )
    (comp (ref "J23")
      (value "2-pos")
      (footprint "eagle-import:2_3.81MM_PITCH")
      (fields (field (name "PARTNO") "691322310002"))
      (libsource (lib "eagle-import") (part "3.81MM_1_X_2_RT_ANGLE_PLUG_HEADER"))
    )
    (comp (ref "J24")
      (value "2-pos")
      (footprint "eagle-import:2_3.81MM_PITCH")
      (fields (field (name "PARTNO") "691322310002"))
      (libsource (lib "eagle-import") (part "3.81MM_1_X_2_RT_ANGLE_PLUG_HEADER"))
    )
    (comp (ref "J25")
      (value "TEKNIC_MOTOR_8PIN")
      (footprint "eagle-import:CON_39281083")
      (fields
        (field (name "MANUFACTURER_PART_NUMBER") "39281083")
        (field (name "COPYRIGHT") "Copyright (C) 2022 Ultra Librarian. All rights reserved.")
      )
      (libsource (lib "eagle-import") (part "TEKNIC_MOTOR_8PIN"))
    )
    (comp (ref "J26")
      (value "TEKNIC_MOTOR_8PIN")
      (footprint "eagle-import:CON_39281083")
      (fields
        (field (name "MANUFACTURER_PART_NUMBER") "39281083")
        (field (name "COPYRIGHT") "Copyright (C) 2022 Ultra Librarian. All rights reserved.")
      )
      (libsource (lib "eagle-import") (part "TEKNIC_MOTOR_8PIN"))
    )
    (comp (ref "J27")
      (value "CONN_530470310_PICOBLADE_X_3")
      (footprint "eagle-import:CON_530470310_MOL")
      (fields
        (field (name "MANUFACTURER_PART_NUMBER") "530470310")
        (field (name "COPYRIGHT") "Copyright (C) 2022 Ultra Librarian. All rights reserved.")
      )
      (libsource (lib "eagle-import") (part "CONN_530470310_PICOBLADE_X_3"))
    )
    (comp (ref "J28")
      (value "CONN_530470310_PICOBLADE_X_3")
      (footprint "eagle-import:CON_530470310_MOL")
      (fields
        (field (name "MANUFACTURER_PART_NUMBER") "530470310")
        (field (name "COPYRIGHT") "Copyright (C) 2022 Ultra Librarian. All rights reserved.")
      )
      (libsource (lib "eagle-import") (part "CONN_530470310_PICOBLADE_X_3"))
    )
    (comp (ref "J29")
      (value "TEKNIC_MOTOR_8PIN")
      (footprint "eagle-import:CON_39281083")
      (fields
        (field (name "MANUFACTURER_PART_NUMBER") "39281083")
        (field (name "COPYRIGHT") "Copyright (C) 2022 Ultra Librarian. All rights reserved.")
      )
      (libsource (lib "eagle-import") (part "TEKNIC_MOTOR_8PIN"))
    )
    (comp (ref "J30")
      (value "TEKNIC_MOTOR_8PIN")
      (footprint "eagle-import:CON_39281083")
      (fields
        (field (name "MANUFACTURER_PART_NUMBER") "39281083")
        (field (name "COPYRIGHT") "Copyright (C) 2022 Ultra Librarian. All rights reserved.")
      )
      (libsource (lib "eagle-import") (part "TEKNIC_MOTOR_8PIN"))
    )
    (comp (ref "J31")
      (value "CONN_530470310_PICOBLADE_X_3")
      (footprint "eagle-import:CON_530470310_MOL")
      (fields
        (field (name "MANUFACTURER_PART_NUMBER") "530470310")
        (field (name "COPYRIGHT") "Copyright (C) 2022 Ultra Librarian. All rights reserved.")
      )
      (libsource (lib "eagle-import") (part "CONN_530470310_PICOBLADE_X_3"))
    )
    (comp (ref "J32")
      (value "CONN_530470310_PICOBLADE_X_3")
      (footprint "eagle-import:CON_530470310_MOL")
      (fields
        (field (name "MANUFACTURER_PART_NUMBER") "530470310")
        (field (name "COPYRIGHT") "Copyright (C) 2022 Ultra Librarian. All rights reserved.")
      )
      (libsource (lib "eagle-import") (part "CONN_530470310_PICOBLADE_X_3"))
    )
    (comp (ref "J33")
      (value "TEKNIC_MOTOR_8PIN")
      (footprint "eagle-import:CON_39281083")
      (fields
        (field (name "MANUFACTURER_PART_NUMBER") "39281083")
        (field (name "COPYRIGHT") "Copyright (C) 2022 Ultra Librarian. All rights reserved.")
      )
      (libsource (lib "eagle-import") (part "TEKNIC_MOTOR_8PIN"))
    )
    (comp (ref "J34")
      (value "TEKNIC_MOTOR_8PIN")
      (footprint "eagle-import:CON_39281083")
      (fields
        (field (name "MANUFACTURER_PART_NUMBER") "39281083")
        (field (name "COPYRIGHT") "Copyright (C) 2022 Ultra Librarian. All rights reserved.")
      )
      (libsource (lib "eagle-import") (part "TEKNIC_MOTOR_8PIN"))
    )
    (comp (ref "J39")
      (value "2_X_10_HEADER_GENERIC")
      (footprint "eagle-import:2_X_10_.1_INCH")
      (fields (field (name "PARTNO") "67996-420HLF"))
      (libsource (lib "eagle-import") (part "2_X_10_HEADER_GENERIC"))
    )
    (comp (ref "L1")
      (value "2.2uH")
      (footprint "eagle-import:1008")
      (fields (field (name "PARTNO") "LQM2HPN2R2MG0L"))
      (libsource (lib "eagle-import") (part "INDUCTOR_1008_2.2_MH_1.3A"))
    )
    (comp (ref "LED1")
      (value "Green")
      (footprint "eagle-import:0805")
      (fields (field (name "PARTNO") "LG R971-KN-1"))
      (libsource (lib "eagle-import") (part "LED_0805_GREEN"))
    )
    (comp (ref "LED3")
      (value "Green")
      (footprint "eagle-import:0805")
      (fields (field (name "PARTNO") "LG R971-KN-1"))
      (libsource (lib "eagle-import") (part "LED_0805_GREEN"))
    )
    (comp (ref "LED4")
      (value "Green")
      (footprint "eagle-import:0805")
      (fields (field (name "PARTNO") "LG R971-KN-1"))
      (libsource (lib "eagle-import") (part "LED_0805_GREEN"))
    )
    (comp (ref "LED5")
      (value "Green")
      (footprint "eagle-import:0805")
      (fields (field (name "PARTNO") "LG R971-KN-1"))
      (libsource (lib "eagle-import") (part "LED_0805_GREEN"))
    )
    (comp (ref "LED6")
      (value "Green")
      (footprint "eagle-import:0805")
      (fields (field (name "PARTNO") "LG R971-KN-1"))
      (libsource (lib "eagle-import") (part "LED_0805_GREEN"))
    )
    (comp (ref "LED7")
      (value "Green")
      (footprint "eagle-import:0805")
      (fields (field (name "PARTNO") "LG R971-KN-1"))
      (libsource (lib "eagle-import") (part "LED_0805_GREEN"))
    )
    (comp (ref "LED8")
      (value "Green")
      (footprint "eagle-import:0805")
      (fields (field (name "PARTNO") "LG R971-KN-1"))
      (libsource (lib "eagle-import") (part "LED_0805_GREEN"))
    )
    (comp (ref "LED9")
      (value "Green")
      (footprint "eagle-import:0805")
      (fields (field (name "PARTNO") "LG R971-KN-1"))
      (libsource (lib "eagle-import") (part "LED_0805_GREEN"))
    )
    (comp (ref "LED10")
      (value "Green")
      (footprint "eagle-import:0805")
      (fields (field (name "PARTNO") "LG R971-KN-1"))
      (libsource (lib "eagle-import") (part "LED_0805_GREEN"))
    )
    (comp (ref "LED11")
      (value "Green")
      (footprint "eagle-import:0805")
      (fields (field (name "PARTNO") "LG R971-KN-1"))
      (libsource (lib "eagle-import") (part "LED_0805_GREEN"))
    )
    (comp (ref "LED12")
      (value "Green")
      (footprint "eagle-import:0805")
      (fields (field (name "PARTNO") "LG R971-KN-1"))
      (libsource (lib "eagle-import") (part "LED_0805_GREEN"))
    )
    (comp (ref "LED13")
      (value "Green")
      (footprint "eagle-import:0805")
      (fields (field (name "PARTNO") "LG R971-KN-1"))
      (libsource (lib "eagle-import") (part "LED_0805_GREEN"))
    )
    (comp (ref "LED14")
      (value "Green")
      (footprint "eagle-import:0805")
      (fields (field (name "PARTNO") "LG R971-KN-1"))
      (libsource (lib "eagle-import") (part "LED_0805_GREEN"))
    )
    (comp (ref "LED15")
      (value "Green")
      (footprint "eagle-import:0805")
      (fields (field (name "PARTNO") "LG R971-KN-1"))
      (libsource (lib "eagle-import") (part "LED_0805_GREEN"))
    )
    (comp (ref "LED16")
      (value "Green")
      (footprint "eagle-import:0805")
      (fields (field (name "PARTNO") "LG R971-KN-1"))
      (libsource (lib "eagle-import") (part "LED_0805_GREEN"))
    )
    (comp (ref "R1")
      (value "6K49")
      (footprint "eagle-import:0402")
      (fields (field (name "PARTNO") "RMCF0402FT6K49"))
      (libsource (lib "eagle-import") (part "R_0402_6K49"))
    )
    (comp (ref "R2")
      (value "10K0")
      (footprint "eagle-import:0402")
      (fields (field (name "PARTNO") "RMCF0402JT10K0"))
      (libsource (lib "eagle-import") (part "R_0402_10K0"))
    )
    (comp (ref "R3")
      (value "10K0")
      (footprint "eagle-import:0402")
      (fields (field (name "PARTNO") "RMCF0402JT10K0"))
      (libsource (lib "eagle-import") (part "R_0402_10K0"))
    )
    (comp (ref "R4")
      (value "1K5")
      (footprint "eagle-import:0402")
      (fields (field (name "PARTNO") "RMCF0402JT1K50"))
      (libsource (lib "eagle-import") (part "R_0402_1K5"))
    )
    (comp (ref "R5")
      (value "470R0")
      (footprint "eagle-import:0402")
      (fields (field (name "PARTNO") "RMCF0402JT470R"))
      (libsource (lib "eagle-import") (part "R_0402_470R0"))
    )
    (comp (ref "R6")
      (value "1K5")
      (footprint "eagle-import:0402")
      (fields (field (name "PARTNO") "RMCF0402JT1K50"))
      (libsource (lib "eagle-import") (part "R_0402_1K5"))
    )
    (comp (ref "R7")
      (value "470R0")
      (footprint "eagle-import:0402")
      (fields (field (name "PARTNO") "RMCF0402JT470R"))
      (libsource (lib "eagle-import") (part "R_0402_470R0"))
    )
    (comp (ref "R8")
      (value "470R0")
      (footprint "eagle-import:0402")
      (fields (field (name "PARTNO") "RMCF0402JT470R"))
      (libsource (lib "eagle-import") (part "R_0402_470R0"))
    )
    (comp (ref "R9")
      (value "33R0")
      (footprint "eagle-import:0402")
      (fields (field (name "PARTNO") "RMCF0402JT33R0"))
      (libsource (lib "eagle-import") (part "R_0402_33R0"))
    )
    (comp (ref "R10")
      (value "33R0")
      (footprint "eagle-import:0402")
      (fields (field (name "PARTNO") "RMCF0402JT33R0"))
      (libsource (lib "eagle-import") (part "R_0402_33R0"))
    )
    (comp (ref "R11")
      (value "33R0")
      (footprint "eagle-import:0402")
      (fields (field (name "PARTNO") "RMCF0402JT33R0"))
      (libsource (lib "eagle-import") (part "R_0402_33R0"))
    )
    (comp (ref "R12")
      (value "33R0")
      (footprint "eagle-import:0402")
      (fields (field (name "PARTNO") "RMCF0402JT33R0"))
      (libsource (lib "eagle-import") (part "R_0402_33R0"))
    )
    (comp (ref "R13")
      (value "10K0")
      (footprint "eagle-import:0402")
      (fields (field (name "PARTNO") "RMCF0402JT10K0"))
      (libsource (lib "eagle-import") (part "R_0402_10K0"))
    )
    (comp (ref "R14")
      (value "1K0")
      (footprint "eagle-import:0402")
      (fields (field (name "PARTNO") "CRG0402J1K0"))
      (libsource (lib "eagle-import") (part "R_0402_1K0"))
    )
    (comp (ref "R15")
      (value "1K0")
      (footprint "eagle-import:0402")
      (fields (field (name "PARTNO") "CRG0402J1K0"))
      (libsource (lib "eagle-import") (part "R_0402_1K0"))
    )
    (comp (ref "R16")
      (value "15K0")
      (footprint "eagle-import:0402")
      (fields (field (name "PARTNO") "RMCF0402JT15K0"))
      (libsource (lib "eagle-import") (part "R_0402_15K0"))
    )
    (comp (ref "R17")
      (value "27R0")
      (footprint "eagle-import:0402")
      (fields (field (name "PARTNO") "RMCF0402JT27R0"))
      (libsource (lib "eagle-import") (part "R_0402_27R0"))
    )
    (comp (ref "R18")
      (value "27R0")
      (footprint "eagle-import:0402")
      (fields (field (name "PARTNO") "RMCF0402JT27R0"))
      (libsource (lib "eagle-import") (part "R_0402_27R0"))
    )
    (comp (ref "R19")
      (value "10K0")
      (footprint "eagle-import:0402")
      (fields (field (name "PARTNO") "RMCF0402JT10K0"))
      (libsource (lib "eagle-import") (part "R_0402_10K0"))
    )
    (comp (ref "R20")
      (value "10K0")
      (footprint "eagle-import:0402")
      (fields (field (name "PARTNO") "RMCF0402JT10K0"))
      (libsource (lib "eagle-import") (part "R_0402_10K0"))
    )
    (comp (ref "R21")
      (value "30K0")
      (footprint "eagle-import:0402")
      (fields (field (name "PARTNO") "RC0402JR-0730KL"))
      (libsource (lib "eagle-import") (part "R_0402_30K0"))
    )
    (comp (ref "R22")
      (value "2K2")
      (footprint "eagle-import:0402")
      (fields (field (name "PARTNO") "RMCF0402JT2K20"))
      (libsource (lib "eagle-import") (part "R_0402_2K2"))
    )
    (comp (ref "R23")
      (value "10K0")
      (footprint "eagle-import:0402")
      (fields (field (name "PARTNO") "RMCF0402JT10K0"))
      (libsource (lib "eagle-import") (part "R_0402_10K0"))
    )
    (comp (ref "R24")
      (value "10K0")
      (footprint "eagle-import:0402")
      (fields (field (name "PARTNO") "RMCF0402JT10K0"))
      (libsource (lib "eagle-import") (part "R_0402_10K0"))
    )
    (comp (ref "R25")
      (value "100K")
      (footprint "eagle-import:0402")
      (libsource (lib "eagle-import") (part "R_0402"))
    )
    (comp (ref "R26")
      (value "100K")
      (footprint "eagle-import:0402")
      (libsource (lib "eagle-import") (part "R_0402"))
    )
    (comp (ref "R27")
      (value "100K")
      (footprint "eagle-import:0402")
      (libsource (lib "eagle-import") (part "R_0402"))
    )
    (comp (ref "R28")
      (value "2.2K")
      (footprint "eagle-import:0402")
      (libsource (lib "eagle-import") (part "R_0402"))
    )
    (comp (ref "R29")
      (value "500R0")
      (footprint "eagle-import:0402")
      (libsource (lib "eagle-import") (part "R_0402"))
    )
    (comp (ref "R30")
      (value "500R0")
      (footprint "eagle-import:0402")
      (libsource (lib "eagle-import") (part "R_0402"))
    )
    (comp (ref "R31")
      (value "470R0")
      (footprint "eagle-import:0402")
      (fields (field (name "PARTNO") "RMCF0402JT470R"))
      (libsource (lib "eagle-import") (part "R_0402_470R0"))
    )
    (comp (ref "R32")
      (value "470R0")
      (footprint "eagle-import:0402")
      (fields (field (name "PARTNO") "RMCF0402JT470R"))
      (libsource (lib "eagle-import") (part "R_0402_470R0"))
    )
    (comp (ref "R33")
      (value "470R0")
      (footprint "eagle-import:0402")
      (fields (field (name "PARTNO") "RMCF0402JT470R"))
      (libsource (lib "eagle-import") (part "R_0402_470R0"))
    )
    (comp (ref "R34")
      (value "10K0")
      (footprint "eagle-import:0402")
      (fields (field (name "PARTNO") "RMCF0402JT10K0"))
      (libsource (lib "eagle-import") (part "R_0402_10K0"))
    )
    (comp (ref "R35")
      (value "2.2K")
      (footprint "eagle-import:0402")
      (libsource (lib "eagle-import") (part "R_0402"))
    )
    (comp (ref "R36")
      (value "470R0")
      (footprint "eagle-import:0402")
      (fields (field (name "PARTNO") "RMCF0402JT470R"))
      (libsource (lib "eagle-import") (part "R_0402_470R0"))
    )
    (comp (ref "R37")
      (value "1k")
      (footprint "eagle-import:0805")
      (libsource (lib "eagle-import") (part "R_0805"))
    )
    (comp (ref "R38")
      (value "33")
      (footprint "eagle-import:0805")
      (libsource (lib "eagle-import") (part "R_0805"))
    )
    (comp (ref "R39")
      (value "33")
      (footprint "eagle-import:0805")
      (libsource (lib "eagle-import") (part "R_0805"))
    )
    (comp (ref "R40")
      (value "33")
      (footprint "eagle-import:0805")
      (libsource (lib "eagle-import") (part "R_0805"))
    )
    (comp (ref "R41")
      (value "1k")
      (footprint "eagle-import:0805")
      (libsource (lib "eagle-import") (part "R_0805"))
    )
    (comp (ref "R42")
      (value "1k")
      (footprint "eagle-import:0805")
      (libsource (lib "eagle-import") (part "R_0805"))
    )
    (comp (ref "R43")
      (value "1k")
      (footprint "eagle-import:0805")
      (libsource (lib "eagle-import") (part "R_0805"))
    )
    (comp (ref "R44")
      (value "33")
      (footprint "eagle-import:0805")
      (libsource (lib "eagle-import") (part "R_0805"))
    )
    (comp (ref "R45")
      (value "33")
      (footprint "eagle-import:0805")
      (libsource (lib "eagle-import") (part "R_0805"))
    )
    (comp (ref "R46")
      (value "33")
      (footprint "eagle-import:0805")
      (libsource (lib "eagle-import") (part "R_0805"))
    )
    (comp (ref "R47")
      (value "1k")
      (footprint "eagle-import:0805")
      (libsource (lib "eagle-import") (part "R_0805"))
    )
    (comp (ref "R48")
      (value "1k")
      (footprint "eagle-import:0805")
      (libsource (lib "eagle-import") (part "R_0805"))
    )
    (comp (ref "R49")
      (value "500R0")
      (footprint "eagle-import:0402")
      (libsource (lib "eagle-import") (part "R_0402"))
    )
    (comp (ref "R50")
      (value "500R0")
      (footprint "eagle-import:0402")
      (libsource (lib "eagle-import") (part "R_0402"))
    )
    (comp (ref "R51")
      (value "470R0")
      (footprint "eagle-import:0402")
      (fields (field (name "PARTNO") "RMCF0402JT470R"))
      (libsource (lib "eagle-import") (part "R_0402_470R0"))
    )
    (comp (ref "R52")
      (value "470R0")
      (footprint "eagle-import:0402")
      (fields (field (name "PARTNO") "RMCF0402JT470R"))
      (libsource (lib "eagle-import") (part "R_0402_470R0"))
    )
    (comp (ref "R53")
      (value "10K0")
      (footprint "eagle-import:0402")
      (fields (field (name "PARTNO") "RMCF0402JT10K0"))
      (libsource (lib "eagle-import") (part "R_0402_10K0"))
    )
    (comp (ref "R54")
      (value "2.2K")
      (footprint "eagle-import:0402")
      (libsource (lib "eagle-import") (part "R_0402"))
    )
    (comp (ref "R55")
      (value "470R0")
      (footprint "eagle-import:0402")
      (fields (field (name "PARTNO") "RMCF0402JT470R"))
      (libsource (lib "eagle-import") (part "R_0402_470R0"))
    )
    (comp (ref "R56")
      (value "10K0")
      (footprint "eagle-import:0402")
      (fields (field (name "PARTNO") "RMCF0402JT10K0"))
      (libsource (lib "eagle-import") (part "R_0402_10K0"))
    )
    (comp (ref "R57")
      (value "2.2K")
      (footprint "eagle-import:0402")
      (libsource (lib "eagle-import") (part "R_0402"))
    )
    (comp (ref "R58")
      (value "470R0")
      (footprint "eagle-import:0402")
      (fields (field (name "PARTNO") "RMCF0402JT470R"))
      (libsource (lib "eagle-import") (part "R_0402_470R0"))
    )
    (comp (ref "R59")
      (value "10K0")
      (footprint "eagle-import:0402")
      (fields (field (name "PARTNO") "RMCF0402JT10K0"))
      (libsource (lib "eagle-import") (part "R_0402_10K0"))
    )
    (comp (ref "R60")
      (value "2.2K")
      (footprint "eagle-import:0402")
      (libsource (lib "eagle-import") (part "R_0402"))
    )
    (comp (ref "R61")
      (value "1k")
      (footprint "eagle-import:0805")
      (libsource (lib "eagle-import") (part "R_0805"))
    )
    (comp (ref "R62")
      (value "33")
      (footprint "eagle-import:0805")
      (libsource (lib "eagle-import") (part "R_0805"))
    )
    (comp (ref "R63")
      (value "33")
      (footprint "eagle-import:0805")
      (libsource (lib "eagle-import") (part "R_0805"))
    )
    (comp (ref "R64")
      (value "33")
      (footprint "eagle-import:0805")
      (libsource (lib "eagle-import") (part "R_0805"))
    )
    (comp (ref "R65")
      (value "1k")
      (footprint "eagle-import:0805")
      (libsource (lib "eagle-import") (part "R_0805"))
    )
    (comp (ref "R66")
      (value "1k")
      (footprint "eagle-import:0805")
      (libsource (lib "eagle-import") (part "R_0805"))
    )
    (comp (ref "R67")
      (value "1k")
      (footprint "eagle-import:0805")
      (libsource (lib "eagle-import") (part "R_0805"))
    )
    (comp (ref "R68")
      (value "33")
      (footprint "eagle-import:0805")
      (libsource (lib "eagle-import") (part "R_0805"))
    )
    (comp (ref "R69")
      (value "33")
      (footprint "eagle-import:0805")
      (libsource (lib "eagle-import") (part "R_0805"))
    )
    (comp (ref "R70")
      (value "33")
      (footprint "eagle-import:0805")
      (libsource (lib "eagle-import") (part "R_0805"))
    )
    (comp (ref "R71")
      (value "1k")
      (footprint "eagle-import:0805")
      (libsource (lib "eagle-import") (part "R_0805"))
    )
    (comp (ref "R72")
      (value "1k")
      (footprint "eagle-import:0805")
      (libsource (lib "eagle-import") (part "R_0805"))
    )
    (comp (ref "R73")
      (value "470R0")
      (footprint "eagle-import:0402")
      (fields (field (name "PARTNO") "RMCF0402JT470R"))
      (libsource (lib "eagle-import") (part "R_0402_470R0"))
    )
    (comp (ref "R74")
      (value "10K0")
      (footprint "eagle-import:0402")
      (fields (field (name "PARTNO") "RMCF0402JT10K0"))
      (libsource (lib "eagle-import") (part "R_0402_10K0"))
    )
    (comp (ref "R75")
      (value "2.2K")
      (footprint "eagle-import:0402")
      (libsource (lib "eagle-import") (part "R_0402"))
    )
    (comp (ref "R76")
      (value "470R0")
      (footprint "eagle-import:0402")
      (fields (field (name "PARTNO") "RMCF0402JT470R"))
      (libsource (lib "eagle-import") (part "R_0402_470R0"))
    )
    (comp (ref "R77")
      (value "10K0")
      (footprint "eagle-import:0402")
      (fields (field (name "PARTNO") "RMCF0402JT10K0"))
      (libsource (lib "eagle-import") (part "R_0402_10K0"))
    )
    (comp (ref "R78")
      (value "2.2K")
      (footprint "eagle-import:0402")
      (libsource (lib "eagle-import") (part "R_0402"))
    )
    (comp (ref "R79")
      (value "470R0")
      (footprint "eagle-import:0402")
      (fields (field (name "PARTNO") "RMCF0402JT470R"))
      (libsource (lib "eagle-import") (part "R_0402_470R0"))
    )
    (comp (ref "R80")
      (value "10K0")
      (footprint "eagle-import:0402")
      (fields (field (name "PARTNO") "RMCF0402JT10K0"))
      (libsource (lib "eagle-import") (part "R_0402_10K0"))
    )
    (comp (ref "R81")
      (value "2.2K")
      (footprint "eagle-import:0402")
      (libsource (lib "eagle-import") (part "R_0402"))
    )
    (comp (ref "R82")
      (value "470R0")
      (footprint "eagle-import:0402")
      (fields (field (name "PARTNO") "RMCF0402JT470R"))
      (libsource (lib "eagle-import") (part "R_0402_470R0"))
    )
    (comp (ref "R83")
      (value "10K0")
      (footprint "eagle-import:0402")
      (fields (field (name "PARTNO") "RMCF0402JT10K0"))
      (libsource (lib "eagle-import") (part "R_0402_10K0"))
    )
    (comp (ref "R84")
      (value "2.2K")
      (footprint "eagle-import:0402")
      (libsource (lib "eagle-import") (part "R_0402"))
    )
    (comp (ref "R85")
      (value "1k")
      (footprint "eagle-import:0805")
      (libsource (lib "eagle-import") (part "R_0805"))
    )
    (comp (ref "R86")
      (value "33")
      (footprint "eagle-import:0805")
      (libsource (lib "eagle-import") (part "R_0805"))
    )
    (comp (ref "R87")
      (value "33")
      (footprint "eagle-import:0805")
      (libsource (lib "eagle-import") (part "R_0805"))
    )
    (comp (ref "R88")
      (value "33")
      (footprint "eagle-import:0805")
      (libsource (lib "eagle-import") (part "R_0805"))
    )
    (comp (ref "R89")
      (value "1k")
      (footprint "eagle-import:0805")
      (libsource (lib "eagle-import") (part "R_0805"))
    )
    (comp (ref "R90")
      (value "1k")
      (footprint "eagle-import:0805")
      (libsource (lib "eagle-import") (part "R_0805"))
    )
    (comp (ref "R91")
      (value "1k")
      (footprint "eagle-import:0805")
      (libsource (lib "eagle-import") (part "R_0805"))
    )
    (comp (ref "R92")
      (value "33")
      (footprint "eagle-import:0805")
      (libsource (lib "eagle-import") (part "R_0805"))
    )
    (comp (ref "R93")
      (value "33")
      (footprint "eagle-import:0805")
      (libsource (lib "eagle-import") (part "R_0805"))
    )
    (comp (ref "R94")
      (value "33")
      (footprint "eagle-import:0805")
      (libsource (lib "eagle-import") (part "R_0805"))
    )
    (comp (ref "R95")
      (value "1k")
      (footprint "eagle-import:0805")
      (libsource (lib "eagle-import") (part "R_0805"))
    )
    (comp (ref "R96")
      (value "1k")
      (footprint "eagle-import:0805")
      (libsource (lib "eagle-import") (part "R_0805"))
    )
    (comp (ref "R97")
      (value "470R0")
      (footprint "eagle-import:0402")
      (fields (field (name "PARTNO") "RMCF0402JT470R"))
      (libsource (lib "eagle-import") (part "R_0402_470R0"))
    )
    (comp (ref "R98")
      (value "10K0")
      (footprint "eagle-import:0402")
      (fields (field (name "PARTNO") "RMCF0402JT10K0"))
      (libsource (lib "eagle-import") (part "R_0402_10K0"))
    )
    (comp (ref "R99")
      (value "2.2K")
      (footprint "eagle-import:0402")
      (libsource (lib "eagle-import") (part "R_0402"))
    )
    (comp (ref "R100")
      (value "470R0")
      (footprint "eagle-import:0402")
      (fields (field (name "PARTNO") "RMCF0402JT470R"))
      (libsource (lib "eagle-import") (part "R_0402_470R0"))
    )
    (comp (ref "R101")
      (value "10K0")
      (footprint "eagle-import:0402")
      (fields (field (name "PARTNO") "RMCF0402JT10K0"))
      (libsource (lib "eagle-import") (part "R_0402_10K0"))
    )
    (comp (ref "R102")
      (value "100K")
      (footprint "eagle-import:0402")
      (libsource (lib "eagle-import") (part "R_0402"))
    )
    (comp (ref "R103")
      (value "100K")
      (footprint "eagle-import:0402")
      (libsource (lib "eagle-import") (part "R_0402"))
    )
    (comp (ref "R104")
      (value "100K")
      (footprint "eagle-import:0402")
      (libsource (lib "eagle-import") (part "R_0402"))
    )
    (comp (ref "R105")
      (value "100K")
      (footprint "eagle-import:0402")
      (libsource (lib "eagle-import") (part "R_0402"))
    )
    (comp (ref "R106")
      (value "100K")
      (footprint "eagle-import:0402")
      (libsource (lib "eagle-import") (part "R_0402"))
    )
    (comp (ref "R107")
      (value "100K")
      (footprint "eagle-import:0402")
      (libsource (lib "eagle-import") (part "R_0402"))
    )
    (comp (ref "R108")
      (value "100K")
      (footprint "eagle-import:0402")
      (libsource (lib "eagle-import") (part "R_0402"))
    )
    (comp (ref "R109")
      (value "1k")
      (footprint "eagle-import:0805")
      (libsource (lib "eagle-import") (part "R_0805"))
    )
    (comp (ref "R110")
      (value "33")
      (footprint "eagle-import:0805")
      (libsource (lib "eagle-import") (part "R_0805"))
    )
    (comp (ref "R111")
      (value "33")
      (footprint "eagle-import:0805")
      (libsource (lib "eagle-import") (part "R_0805"))
    )
    (comp (ref "R112")
      (value "33")
      (footprint "eagle-import:0805")
      (libsource (lib "eagle-import") (part "R_0805"))
    )
    (comp (ref "R113")
      (value "1k")
      (footprint "eagle-import:0805")
      (libsource (lib "eagle-import") (part "R_0805"))
    )
    (comp (ref "R114")
      (value "1k")
      (footprint "eagle-import:0805")
      (libsource (lib "eagle-import") (part "R_0805"))
    )
    (comp (ref "R115")
      (value "1k")
      (footprint "eagle-import:0805")
      (libsource (lib "eagle-import") (part "R_0805"))
    )
    (comp (ref "R116")
      (value "33")
      (footprint "eagle-import:0805")
      (libsource (lib "eagle-import") (part "R_0805"))
    )
    (comp (ref "R117")
      (value "33")
      (footprint "eagle-import:0805")
      (libsource (lib "eagle-import") (part "R_0805"))
    )
    (comp (ref "R118")
      (value "33")
      (footprint "eagle-import:0805")
      (libsource (lib "eagle-import") (part "R_0805"))
    )
    (comp (ref "R119")
      (value "1k")
      (footprint "eagle-import:0805")
      (libsource (lib "eagle-import") (part "R_0805"))
    )
    (comp (ref "R120")
      (value "1k")
      (footprint "eagle-import:0805")
      (libsource (lib "eagle-import") (part "R_0805"))
    )
    (comp (ref "R133")
      (value "1k")
      (footprint "eagle-import:0805")
      (libsource (lib "eagle-import") (part "R_0805"))
    )
    (comp (ref "R134")
      (value "33")
      (footprint "eagle-import:0805")
      (libsource (lib "eagle-import") (part "R_0805"))
    )
    (comp (ref "R135")
      (value "33")
      (footprint "eagle-import:0805")
      (libsource (lib "eagle-import") (part "R_0805"))
    )
    (comp (ref "R136")
      (value "33")
      (footprint "eagle-import:0805")
      (libsource (lib "eagle-import") (part "R_0805"))
    )
    (comp (ref "R137")
      (value "1k")
      (footprint "eagle-import:0805")
      (libsource (lib "eagle-import") (part "R_0805"))
    )
    (comp (ref "R138")
      (value "1k")
      (footprint "eagle-import:0805")
      (libsource (lib "eagle-import") (part "R_0805"))
    )
    (comp (ref "R139")
      (value "1k")
      (footprint "eagle-import:0805")
      (libsource (lib "eagle-import") (part "R_0805"))
    )
    (comp (ref "R140")
      (value "33")
      (footprint "eagle-import:0805")
      (libsource (lib "eagle-import") (part "R_0805"))
    )
    (comp (ref "R141")
      (value "33")
      (footprint "eagle-import:0805")
      (libsource (lib "eagle-import") (part "R_0805"))
    )
    (comp (ref "R142")
      (value "33")
      (footprint "eagle-import:0805")
      (libsource (lib "eagle-import") (part "R_0805"))
    )
    (comp (ref "R143")
      (value "1k")
      (footprint "eagle-import:0805")
      (libsource (lib "eagle-import") (part "R_0805"))
    )
    (comp (ref "R144")
      (value "1k")
      (footprint "eagle-import:0805")
      (libsource (lib "eagle-import") (part "R_0805"))
    )
    (comp (ref "R157")
      (value "1k")
      (footprint "eagle-import:0805")
      (libsource (lib "eagle-import") (part "R_0805"))
    )
    (comp (ref "R158")
      (value "33")
      (footprint "eagle-import:0805")
      (libsource (lib "eagle-import") (part "R_0805"))
    )
    (comp (ref "R159")
      (value "33")
      (footprint "eagle-import:0805")
      (libsource (lib "eagle-import") (part "R_0805"))
    )
    (comp (ref "R160")
      (value "33")
      (footprint "eagle-import:0805")
      (libsource (lib "eagle-import") (part "R_0805"))
    )
    (comp (ref "R161")
      (value "1k")
      (footprint "eagle-import:0805")
      (libsource (lib "eagle-import") (part "R_0805"))
    )
    (comp (ref "R162")
      (value "1k")
      (footprint "eagle-import:0805")
      (libsource (lib "eagle-import") (part "R_0805"))
    )
    (comp (ref "R163")
      (value "1k")
      (footprint "eagle-import:0805")
      (libsource (lib "eagle-import") (part "R_0805"))
    )
    (comp (ref "R164")
      (value "33")
      (footprint "eagle-import:0805")
      (libsource (lib "eagle-import") (part "R_0805"))
    )
    (comp (ref "R165")
      (value "33")
      (footprint "eagle-import:0805")
      (libsource (lib "eagle-import") (part "R_0805"))
    )
    (comp (ref "R166")
      (value "33")
      (footprint "eagle-import:0805")
      (libsource (lib "eagle-import") (part "R_0805"))
    )
    (comp (ref "R167")
      (value "1k")
      (footprint "eagle-import:0805")
      (libsource (lib "eagle-import") (part "R_0805"))
    )
    (comp (ref "R168")
      (value "1k")
      (footprint "eagle-import:0805")
      (libsource (lib "eagle-import") (part "R_0805"))
    )
    (comp (ref "RJ1")
      (value "RJ45")
      (footprint "eagle-import:RJ45_TH_ELEC")
      (fields (field (name "PARTNO") "13F-64GYD2PL2NL"))
      (libsource (lib "eagle-import") (part "RJ45_WITH_ELEC"))
    )
    (comp (ref "U$1")
      (value "RELAY_KYOTO_KF0604D")
      (footprint "eagle-import:RELAY_KYOTO_KF0604D")
      (libsource (lib "eagle-import") (part "RELAY_KYOTO_KF0604D"))
    )
    (comp (ref "U$2")
      (value "RELAY_KYOTO_KF0604D")
      (footprint "eagle-import:RELAY_KYOTO_KF0604D")
      (libsource (lib "eagle-import") (part "RELAY_KYOTO_KF0604D"))
    )
    (comp (ref "U$7")
      (value "RELAY_KYOTO_KF0604D")
      (footprint "eagle-import:RELAY_KYOTO_KF0604D")
      (libsource (lib "eagle-import") (part "RELAY_KYOTO_KF0604D"))
    )
    (comp (ref "U$8")
      (value "RELAY_KYOTO_KF0604D")
      (footprint "eagle-import:RELAY_KYOTO_KF0604D")
      (libsource (lib "eagle-import") (part "RELAY_KYOTO_KF0604D"))
    )
    (comp (ref "U1")
      (value "KSZ8081_QFN_24")
      (footprint "eagle-import:QFN-24-M")
      (fields (field (name "PARTNO") "KSZ8081RNACA"))
      (libsource (lib "eagle-import") (part "KSZ8081RNACAQFN-24-M"))
    )
    (comp (ref "U2")
      (value "AP2151DWG-7")
      (footprint "eagle-import:SOT-23-5")
      (fields (field (name "PARTNO") "AP2151WG-7"))
      (libsource (lib "eagle-import") (part "AP2151DWG-7"))
    )
    (comp (ref "U3")
      (value "S7G2LQFP176")
      (footprint "eagle-import:LQFP176_24X24")
      (fields (field (name "PARTNO") "R7FS7G27H3A01CFC#AA0"))
      (libsource (lib "eagle-import") (part "RENESAS_S7G2_X_176"))
    )
    (comp (ref "U5")
      (value "NPN")
      (footprint "eagle-import:SOT323")
      (fields (field (name "PARTNO") "BC846BW_NPN"))
      (libsource (lib "eagle-import") (part "BC846BW"))
    )
    (comp (ref "U6")
      (value "NPN")
      (footprint "eagle-import:SOT323")
      (fields (field (name "PARTNO") "BC846BW_NPN"))
      (libsource (lib "eagle-import") (part "BC846BW"))
    )
    (comp (ref "U7")
      (value "NPN")
      (footprint "eagle-import:SOT323")
      (fields (field (name "PARTNO") "BC846BW_NPN"))
      (libsource (lib "eagle-import") (part "BC846BW"))
    )
    (comp (ref "U8")
      (value "NPN")
      (footprint "eagle-import:SOT323")
      (fields (field (name "PARTNO") "BC846BW_NPN"))
      (libsource (lib "eagle-import") (part "BC846BW"))
    )
    (comp (ref "U9")
      (value "NPN")
      (footprint "eagle-import:SOT323")
      (fields (field (name "PARTNO") "BC846BW_NPN"))
      (libsource (lib "eagle-import") (part "BC846BW"))
    )
    (comp (ref "U10")
      (value "NPN")
      (footprint "eagle-import:SOT323")
      (fields (field (name "PARTNO") "BC846BW_NPN"))
      (libsource (lib "eagle-import") (part "BC846BW"))
    )
    (comp (ref "U11")
      (value "NPN")
      (footprint "eagle-import:SOT323")
      (fields (field (name "PARTNO") "BC846BW_NPN"))
      (libsource (lib "eagle-import") (part "BC846BW"))
    )
    (comp (ref "U12")
      (value "NPN")
      (footprint "eagle-import:SOT323")
      (fields (field (name "PARTNO") "BC846BW_NPN"))
      (libsource (lib "eagle-import") (part "BC846BW"))
    )
    (comp (ref "U13")
      (value "NPN")
      (footprint "eagle-import:SOT323")
      (fields (field (name "PARTNO") "BC846BW_NPN"))
      (libsource (lib "eagle-import") (part "BC846BW"))
    )
    (comp (ref "U14")
      (value "NPN")
      (footprint "eagle-import:SOT323")
      (fields (field (name "PARTNO") "BC846BW_NPN"))
      (libsource (lib "eagle-import") (part "BC846BW"))
    )
    (comp (ref "U15")
      (value "NPN")
      (footprint "eagle-import:SOT323")
      (fields (field (name "PARTNO") "BC846BW_NPN"))
      (libsource (lib "eagle-import") (part "BC846BW"))
    )
    (comp (ref "U16")
      (value "NPN")
      (footprint "eagle-import:SOT323")
      (fields (field (name "PARTNO") "BC846BW_NPN"))
      (libsource (lib "eagle-import") (part "BC846BW"))
    )
    (comp (ref "U17")
      (value "NPN")
      (footprint "eagle-import:SOT323")
      (fields (field (name "PARTNO") "BC846BW_NPN"))
      (libsource (lib "eagle-import") (part "BC846BW"))
    )
    (comp (ref "U18")
      (value "NPN")
      (footprint "eagle-import:SOT323")
      (fields (field (name "PARTNO") "BC846BW_NPN"))
      (libsource (lib "eagle-import") (part "BC846BW"))
    )
    (comp (ref "U19")
      (value "NPN")
      (footprint "eagle-import:SOT323")
      (fields (field (name "PARTNO") "BC846BW_NPN"))
      (libsource (lib "eagle-import") (part "BC846BW"))
    )
    (comp (ref "U20")
      (value "NPN")
      (footprint "eagle-import:SOT323")
      (fields (field (name "PARTNO") "BC846BW_NPN"))
      (libsource (lib "eagle-import") (part "BC846BW"))
    )
    (comp (ref "U21")
      (value "NPN")
      (footprint "eagle-import:SOT323")
      (fields (field (name "PARTNO") "BC846BW_NPN"))
      (libsource (lib "eagle-import") (part "BC846BW"))
    )
    (comp (ref "U22")
      (value "NPN")
      (footprint "eagle-import:SOT323")
      (fields (field (name "PARTNO") "BC846BW_NPN"))
      (libsource (lib "eagle-import") (part "BC846BW"))
    )
    (comp (ref "U23")
      (value "NPN")
      (footprint "eagle-import:SOT323")
      (fields (field (name "PARTNO") "BC846BW_NPN"))
      (libsource (lib "eagle-import") (part "BC846BW"))
    )
    (comp (ref "U24")
      (value "NPN")
      (footprint "eagle-import:SOT323")
      (fields (field (name "PARTNO") "BC846BW_NPN"))
      (libsource (lib "eagle-import") (part "BC846BW"))
    )
    (comp (ref "U25")
      (value "NPN")
      (footprint "eagle-import:SOT323")
      (fields (field (name "PARTNO") "BC846BW_NPN"))
      (libsource (lib "eagle-import") (part "BC846BW"))
    )
    (comp (ref "U26")
      (value "NPN")
      (footprint "eagle-import:SOT323")
      (fields (field (name "PARTNO") "BC846BW_NPN"))
      (libsource (lib "eagle-import") (part "BC846BW"))
    )
    (comp (ref "U27")
      (value "NPN")
      (footprint "eagle-import:SOT323")
      (fields (field (name "PARTNO") "BC846BW_NPN"))
      (libsource (lib "eagle-import") (part "BC846BW"))
    )
    (comp (ref "U28")
      (value "NPN")
      (footprint "eagle-import:SOT323")
      (fields (field (name "PARTNO") "BC846BW_NPN"))
      (libsource (lib "eagle-import") (part "BC846BW"))
    )
    (comp (ref "U29")
      (value "NPN")
      (footprint "eagle-import:SOT323")
      (fields (field (name "PARTNO") "BC846BW_NPN"))
      (libsource (lib "eagle-import") (part "BC846BW"))
    )
    (comp (ref "U30")
      (value "NPN")
      (footprint "eagle-import:SOT323")
      (fields (field (name "PARTNO") "BC846BW_NPN"))
      (libsource (lib "eagle-import") (part "BC846BW"))
    )
    (comp (ref "U34")
      (value "NPN")
      (footprint "eagle-import:SOT323")
      (fields (field (name "PARTNO") "BC846BW_NPN"))
      (libsource (lib "eagle-import") (part "BC846BW"))
    )
    (comp (ref "U35")
      (value "NPN")
      (footprint "eagle-import:SOT323")
      (fields (field (name "PARTNO") "BC846BW_NPN"))
      (libsource (lib "eagle-import") (part "BC846BW"))
    )
    (comp (ref "U36")
      (value "NPN")
      (footprint "eagle-import:SOT323")
      (fields (field (name "PARTNO") "BC846BW_NPN"))
      (libsource (lib "eagle-import") (part "BC846BW"))
    )
    (comp (ref "U37")
      (value "NPN")
      (footprint "eagle-import:SOT323")
      (fields (field (name "PARTNO") "BC846BW_NPN"))
      (libsource (lib "eagle-import") (part "BC846BW"))
    )
    (comp (ref "U38")
      (value "NPN")
      (footprint "eagle-import:SOT323")
      (fields (field (name "PARTNO") "BC846BW_NPN"))
      (libsource (lib "eagle-import") (part "BC846BW"))
    )
    (comp (ref "U39")
      (value "NPN")
      (footprint "eagle-import:SOT323")
      (fields (field (name "PARTNO") "BC846BW_NPN"))
      (libsource (lib "eagle-import") (part "BC846BW"))
    )
    (comp (ref "U46")
      (value "NPN")
      (footprint "eagle-import:SOT323")
      (fields (field (name "PARTNO") "BC846BW_NPN"))
      (libsource (lib "eagle-import") (part "BC846BW"))
    )
    (comp (ref "U47")
      (value "NPN")
      (footprint "eagle-import:SOT323")
      (fields (field (name "PARTNO") "BC846BW_NPN"))
      (libsource (lib "eagle-import") (part "BC846BW"))
    )
    (comp (ref "U48")
      (value "NPN")
      (footprint "eagle-import:SOT323")
      (fields (field (name "PARTNO") "BC846BW_NPN"))
      (libsource (lib "eagle-import") (part "BC846BW"))
    )
    (comp (ref "U49")
      (value "NPN")
      (footprint "eagle-import:SOT323")
      (fields (field (name "PARTNO") "BC846BW_NPN"))
      (libsource (lib "eagle-import") (part "BC846BW"))
    )
    (comp (ref "U50")
      (value "NPN")
      (footprint "eagle-import:SOT323")
      (fields (field (name "PARTNO") "BC846BW_NPN"))
      (libsource (lib "eagle-import") (part "BC846BW"))
    )
    (comp (ref "U51")
      (value "NPN")
      (footprint "eagle-import:SOT323")
      (fields (field (name "PARTNO") "BC846BW_NPN"))
      (libsource (lib "eagle-import") (part "BC846BW"))
    )
    (comp (ref "U58")
      (value "NPN")
      (footprint "eagle-import:SOT323")
      (fields (field (name "PARTNO") "BC846BW_NPN"))
      (libsource (lib "eagle-import") (part "BC846BW"))
    )
    (comp (ref "U59")
      (value "NPN")
      (footprint "eagle-import:SOT323")
      (fields (field (name "PARTNO") "BC846BW_NPN"))
      (libsource (lib "eagle-import") (part "BC846BW"))
    )
    (comp (ref "U60")
      (value "NPN")
      (footprint "eagle-import:SOT323")
      (fields (field (name "PARTNO") "BC846BW_NPN"))
      (libsource (lib "eagle-import") (part "BC846BW"))
    )
    (comp (ref "U61")
      (value "NPN")
      (footprint "eagle-import:SOT323")
      (fields (field (name "PARTNO") "BC846BW_NPN"))
      (libsource (lib "eagle-import") (part "BC846BW"))
    )
    (comp (ref "U62")
      (value "NPN")
      (footprint "eagle-import:SOT323")
      (fields (field (name "PARTNO") "BC846BW_NPN"))
      (libsource (lib "eagle-import") (part "BC846BW"))
    )
    (comp (ref "U63")
      (value "NPN")
      (footprint "eagle-import:SOT323")
      (fields (field (name "PARTNO") "BC846BW_NPN"))
      (libsource (lib "eagle-import") (part "BC846BW"))
    )
    (comp (ref "U70")
      (value "NPN")
      (footprint "eagle-import:SOT323")
      (fields (field (name "PARTNO") "BC846BW_NPN"))
      (libsource (lib "eagle-import") (part "BC846BW"))
    )
    (comp (ref "U71")
      (value "NPN")
      (footprint "eagle-import:SOT323")
      (fields (field (name "PARTNO") "BC846BW_NPN"))
      (libsource (lib "eagle-import") (part "BC846BW"))
    )
    (comp (ref "U72")
      (value "NPN")
      (footprint "eagle-import:SOT323")
      (fields (field (name "PARTNO") "BC846BW_NPN"))
      (libsource (lib "eagle-import") (part "BC846BW"))
    )
    (comp (ref "U73")
      (value "NPN")
      (footprint "eagle-import:SOT323")
      (fields (field (name "PARTNO") "BC846BW_NPN"))
      (libsource (lib "eagle-import") (part "BC846BW"))
    )
    (comp (ref "U74")
      (value "NPN")
      (footprint "eagle-import:SOT323")
      (fields (field (name "PARTNO") "BC846BW_NPN"))
      (libsource (lib "eagle-import") (part "BC846BW"))
    )
    (comp (ref "U75")
      (value "NPN")
      (footprint "eagle-import:SOT323")
      (fields (field (name "PARTNO") "BC846BW_NPN"))
      (libsource (lib "eagle-import") (part "BC846BW"))
    )
    (comp (ref "X1")
      (value "25MHz")
      (footprint "eagle-import:SMD_3225")
      (fields (field (name "PARTNO") "FA-238 25.0000MB-B3"))
      (libsource (lib "eagle-import") (part "XTAL_25_MHZ"))
    )
    (comp (ref "X2")
      (value "24MHz")
      (footprint "eagle-import:SMD_3225")
      (fields (field (name "PARTNO") "FA-238 24.0000MB-C3 "))
      (libsource (lib "eagle-import") (part "XTAL_24_MHZ"))
    )
    (comp (ref "X3")
      (value "32.768KHz")
      (footprint "eagle-import:SMD_X_2_PADS")
      (fields (field (name "PARTNO") "ABS07-32.768KHZ-T"))
      (libsource (lib "eagle-import") (part "XTAL_32.768KHZ"))
    )
  )
  (nets
    (net (code "1") (name "A_A_DIR") (class "Default")
      (node (ref "R111") (pin "1") (pinfunction "1_1") (pintype "passive"))
      (node (ref "U3") (pin "73") (pinfunction "P9_5_73") (pintype "bidirectional"))
    )
    (net (code "2") (name "A_A_ENABLE") (class "Default")
      (node (ref "R112") (pin "1") (pinfunction "1_1") (pintype "passive"))
      (node (ref "U3") (pin "72") (pinfunction "P9_6_72") (pintype "bidirectional"))
    )
    (net (code "3") (name "A_A_HLFB_OUT") (class "Default")
      (node (ref "J25") (pin "5") (pinfunction "5-HLFB-_5") (pintype "passive"))
    )
    (net (code "4") (name "A_A_MI_DIR") (class "Default")
      (node (ref "J25") (pin "7") (pinfunction "7-INPUT_A-_7") (pintype "passive"))
      (node (ref "R113") (pin "1") (pinfunction "1_1") (pintype "passive"))
      (node (ref "U47") (pin "3") (pinfunction "C(3)_3") (pintype "input"))
    )
    (net (code "5") (name "A_A_MI_ENABLE") (class "Default")
      (node (ref "J25") (pin "8") (pinfunction "8-ENABLE-_8") (pintype "passive"))
      (node (ref "R114") (pin "1") (pinfunction "1_1") (pintype "passive"))
      (node (ref "U48") (pin "3") (pinfunction "C(3)_3") (pintype "input"))
    )
    (net (code "6") (name "A_A_MI_STEP") (class "Default")
      (node (ref "J25") (pin "6") (pinfunction "6-INPUT_B-_6") (pintype "passive"))
      (node (ref "R109") (pin "1") (pinfunction "1_1") (pintype "passive"))
      (node (ref "U46") (pin "3") (pinfunction "C(3)_3") (pintype "input"))
    )
    (net (code "7") (name "A_A_STEP") (class "Default")
      (node (ref "R110") (pin "1") (pinfunction "1_1") (pintype "passive"))
      (node (ref "U3") (pin "74") (pinfunction "P3_12_74") (pintype "bidirectional"))
    )
    (net (code "8") (name "A_B_DIR") (class "Default")
      (node (ref "R117") (pin "1") (pinfunction "1_1") (pintype "passive"))
      (node (ref "U3") (pin "76") (pinfunction "P3_10_76") (pintype "bidirectional"))
    )
    (net (code "9") (name "A_B_ENABLE") (class "Default")
      (node (ref "R118") (pin "1") (pinfunction "1_1") (pintype "passive"))
      (node (ref "U3") (pin "75") (pinfunction "P3_11_75") (pintype "bidirectional"))
    )
    (net (code "10") (name "A_B_HLFB_OUT") (class "Default")
      (node (ref "J26") (pin "5") (pinfunction "5-HLFB-_5") (pintype "passive"))
    )
    (net (code "11") (name "A_B_MI_DIR") (class "Default")
      (node (ref "J26") (pin "7") (pinfunction "7-INPUT_A-_7") (pintype "passive"))
      (node (ref "R119") (pin "1") (pinfunction "1_1") (pintype "passive"))
      (node (ref "U50") (pin "3") (pinfunction "C(3)_3") (pintype "input"))
    )
    (net (code "12") (name "A_B_MI_ENABLE") (class "Default")
      (node (ref "J26") (pin "8") (pinfunction "8-ENABLE-_8") (pintype "passive"))
      (node (ref "R120") (pin "1") (pinfunction "1_1") (pintype "passive"))
      (node (ref "U51") (pin "3") (pinfunction "C(3)_3") (pintype "input"))
    )
    (net (code "13") (name "A_B_MI_STEP") (class "Default")
      (node (ref "J26") (pin "6") (pinfunction "6-INPUT_B-_6") (pintype "passive"))
      (node (ref "R115") (pin "1") (pinfunction "1_1") (pintype "passive"))
      (node (ref "U49") (pin "3") (pinfunction "C(3)_3") (pintype "input"))
    )
    (net (code "14") (name "A_B_STEP") (class "Default")
      (node (ref "R116") (pin "1") (pinfunction "1_1") (pintype "passive"))
      (node (ref "U3") (pin "77") (pinfunction "P3_9_77") (pintype "bidirectional"))
    )
    (net (code "15") (name "B_MI_DIR") (class "Default")
      (node (ref "J34") (pin "7") (pinfunction "7-INPUT_A-_7") (pintype "passive"))
      (node (ref "R167") (pin "1") (pinfunction "1_1") (pintype "passive"))
      (node (ref "U74") (pin "3") (pinfunction "C(3)_3") (pintype "input"))
    )
    (net (code "16") (name "C58") (class "Default")
      (node (ref "C12") (pin "P$1") (pinfunction "1_P$1") (pintype "passive"))
      (node (ref "RJ1") (pin "4") (pinfunction "CT1_4") (pintype "bidirectional"))
    )
    (net (code "17") (name "C60") (class "Default")
      (node (ref "C13") (pin "P$1") (pinfunction "1_P$1") (pintype "passive"))
      (node (ref "RJ1") (pin "5") (pinfunction "CT2_5") (pintype "bidirectional"))
    )
    (net (code "18") (name "CRS_DV") (class "Default")
      (node (ref "R12") (pin "P$2") (pinfunction "2_P$2") (pintype "passive"))
      (node (ref "U1") (pin "15") (pinfunction "CRS_DV/PHYAD[1:0]_15") (pintype "bidirectional"))
    )
    (net (code "19") (name "C_A_DIR") (class "Default")
      (node (ref "R135") (pin "1") (pinfunction "1_1") (pintype "passive"))
      (node (ref "U3") (pin "58") (pinfunction "P9_0_58") (pintype "bidirectional"))
    )
    (net (code "20") (name "C_A_ENABLE") (class "Default")
      (node (ref "R136") (pin "1") (pinfunction "1_1") (pintype "passive"))
      (node (ref "U3") (pin "57") (pinfunction "P3_15_57") (pintype "bidirectional"))
    )
    (net (code "21") (name "C_A_HLFB_OUT") (class "Default")
      (node (ref "J29") (pin "5") (pinfunction "5-HLFB-_5") (pintype "passive"))
    )
    (net (code "22") (name "C_A_MI_DIR") (class "Default")
      (node (ref "J29") (pin "7") (pinfunction "7-INPUT_A-_7") (pintype "passive"))
      (node (ref "R137") (pin "1") (pinfunction "1_1") (pintype "passive"))
      (node (ref "U59") (pin "3") (pinfunction "C(3)_3") (pintype "input"))
    )
    (net (code "23") (name "C_A_MI_ENABLE") (class "Default")
      (node (ref "J29") (pin "8") (pinfunction "8-ENABLE-_8") (pintype "passive"))
      (node (ref "R138") (pin "1") (pinfunction "1_1") (pintype "passive"))
      (node (ref "U60") (pin "3") (pinfunction "C(3)_3") (pintype "input"))
    )
    (net (code "24") (name "C_A_MI_STEP") (class "Default")
      (node (ref "J29") (pin "6") (pinfunction "6-INPUT_B-_6") (pintype "passive"))
      (node (ref "R133") (pin "1") (pinfunction "1_1") (pintype "passive"))
      (node (ref "U58") (pin "3") (pinfunction "C(3)_3") (pintype "input"))
    )
    (net (code "25") (name "C_A_STEP") (class "Default")
      (node (ref "R134") (pin "1") (pinfunction "1_1") (pintype "passive"))
      (node (ref "U3") (pin "59") (pinfunction "P9_1_59") (pintype "bidirectional"))
    )
    (net (code "26") (name "C_B_DIR") (class "Default")
      (node (ref "R141") (pin "1") (pinfunction "1_1") (pintype "passive"))
      (node (ref "U3") (pin "70") (pinfunction "P9_8_70") (pintype "bidirectional"))
    )
    (net (code "27") (name "C_B_ENABLE") (class "Default")
      (node (ref "R142") (pin "1") (pinfunction "1_1") (pintype "passive"))
      (node (ref "U3") (pin "68") (pinfunction "P2_1/MD_68") (pintype "bidirectional"))
    )
    (net (code "28") (name "C_B_HLFB_OUT") (class "Default")
      (node (ref "J30") (pin "5") (pinfunction "5-HLFB-_5") (pintype "passive"))
    )
    (net (code "29") (name "C_B_MI_DIR") (class "Default")
      (node (ref "J30") (pin "7") (pinfunction "7-INPUT_A-_7") (pintype "passive"))
      (node (ref "R143") (pin "1") (pinfunction "1_1") (pintype "passive"))
      (node (ref "U62") (pin "3") (pinfunction "C(3)_3") (pintype "input"))
    )
    (net (code "30") (name "C_B_MI_ENABLE") (class "Default")
      (node (ref "J30") (pin "8") (pinfunction "8-ENABLE-_8") (pintype "passive"))
      (node (ref "R144") (pin "1") (pinfunction "1_1") (pintype "passive"))
      (node (ref "U63") (pin "3") (pinfunction "C(3)_3") (pintype "input"))
    )
    (net (code "31") (name "C_B_MI_STEP") (class "Default")
      (node (ref "J30") (pin "6") (pinfunction "6-INPUT_B-_6") (pintype "passive"))
      (node (ref "R139") (pin "1") (pinfunction "1_1") (pintype "passive"))
      (node (ref "U61") (pin "3") (pinfunction "C(3)_3") (pintype "input"))
    )
    (net (code "32") (name "C_B_STEP") (class "Default")
      (node (ref "R140") (pin "1") (pinfunction "1_1") (pintype "passive"))
      (node (ref "U3") (pin "71") (pinfunction "P9_7_71") (pintype "bidirectional"))
    )
    (net (code "33") (name "ESTOP") (class "Default")
      (node (ref "R79") (pin "P$2") (pinfunction "2_P$2") (pintype "passive"))
      (node (ref "R80") (pin "P$2") (pinfunction "2_P$2") (pintype "passive"))
      (node (ref "U21") (pin "2") (pinfunction "E(1)_2") (pintype "output"))
      (node (ref "U3") (pin "69") (pinfunction "P2_0(INPUT_ONLY)_69") (pintype "bidirectional"))
    )
    (net (code "34") (name "ESTOP_RET") (class "Default")
      (node (ref "J20") (pin "1") (pinfunction "1_1") (pintype "passive"))
      (node (ref "R78") (pin "P$1") (pinfunction "1_P$1") (pintype "passive"))
    )
    (net (code "35") (name "ETH") (class "Default")
      (node (ref "U1") (pin "16") (pinfunction "REF_CLK_16") (pintype "bidirectional"))
      (node (ref "U3") (pin "9") (pinfunction "P7_1_9") (pintype "bidirectional"))
    )
    (net (code "36") (name "ETH_CRS_DV") (class "Default")
      (node (ref "R12") (pin "P$1") (pinfunction "1_P$1") (pintype "passive"))
      (node (ref "U3") (pin "13") (pinfunction "P7_5_13") (pintype "bidirectional"))
    )
    (net (code "37") (name "ETH_IRQ14") (class "Default")
      (node (ref "R2") (pin "P$1") (pinfunction "1_P$1") (pintype "passive"))
      (node (ref "U1") (pin "18") (pinfunction "INTRP_18") (pintype "bidirectional"))
      (node (ref "U3") (pin "159") (pinfunction "P0_10/AN103_159") (pintype "bidirectional"))
    )
    (net (code "38") (name "ETH_MDC") (class "Default")
      (node (ref "R4") (pin "P$1") (pinfunction "1_P$1") (pintype "passive"))
      (node (ref "U1") (pin "11") (pinfunction "MDC_11") (pintype "input"))
      (node (ref "U3") (pin "4") (pinfunction "P4_3_4") (pintype "bidirectional"))
    )
    (net (code "39") (name "ETH_MDIO") (class "Default")
      (node (ref "R6") (pin "P$1") (pinfunction "1_P$1") (pintype "passive"))
      (node (ref "U1") (pin "10") (pinfunction "MDIO_10") (pintype "bidirectional"))
      (node (ref "U3") (pin "5") (pinfunction "P4_4_5") (pintype "bidirectional"))
    )
    (net (code "40") (name "ETH_RESET") (class "Default")
      (node (ref "C6") (pin "P$1") (pinfunction "1_P$1") (pintype "passive"))
      (node (ref "R3") (pin "P$1") (pinfunction "1_P$1") (pintype "passive"))
      (node (ref "U1") (pin "24") (pinfunction "~{RST}_24") (pintype "input"))
      (node (ref "U3") (pin "172") (pinfunction "P8_6_172") (pintype "bidirectional"))
    )
    (net (code "41") (name "ETH_RXD0") (class "Default")
      (node (ref "R10") (pin "P$1") (pinfunction "1_P$1") (pintype "passive"))
      (node (ref "U3") (pin "10") (pinfunction "P7_2_10") (pintype "bidirectional"))
    )
    (net (code "42") (name "ETH_RXD1") (class "Default")
      (node (ref "R9") (pin "P$1") (pinfunction "1_P$1") (pintype "passive"))
      (node (ref "U3") (pin "11") (pinfunction "P7_3_11") (pintype "bidirectional"))
    )
    (net (code "43") (name "ETH_RX_ER") (class "Default")
      (node (ref "R11") (pin "P$1") (pinfunction "1_P$1") (pintype "passive"))
      (node (ref "U3") (pin "12") (pinfunction "P7_4_12") (pintype "bidirectional"))
    )
    (net (code "44") (name "ETH_TXD0") (class "Default")
      (node (ref "U1") (pin "20") (pinfunction "TXD0_20") (pintype "input"))
      (node (ref "U3") (pin "8") (pinfunction "P7_0_8") (pintype "bidirectional"))
    )
    (net (code "45") (name "ETH_TXD1") (class "Default")
      (node (ref "U1") (pin "21") (pinfunction "TXD1_21") (pintype "bidirectional"))
      (node (ref "U3") (pin "7") (pinfunction "P4_6_7") (pintype "bidirectional"))
    )
    (net (code "46") (name "ETH_TXD_EN") (class "Default")
      (node (ref "U1") (pin "19") (pinfunction "TXEN_19") (pintype "input"))
      (node (ref "U3") (pin "6") (pinfunction "P4_5_6") (pintype "bidirectional"))
    )
    (net (code "47") (name "GND") (class "Default")
      (node (ref "C1") (pin "P$2") (pinfunction "2_P$2") (pintype "passive"))
      (node (ref "C10") (pin "P$2") (pinfunction "2_P$2") (pintype "passive"))
      (node (ref "C11") (pin "P$2") (pinfunction "2_P$2") (pintype "passive"))
      (node (ref "C12") (pin "P$2") (pinfunction "2_P$2") (pintype "passive"))
      (node (ref "C13") (pin "P$2") (pinfunction "2_P$2") (pintype "passive"))
      (node (ref "C14") (pin "P$2") (pinfunction "2_P$2") (pintype "passive"))
      (node (ref "C15") (pin "P$2") (pinfunction "2_P$2") (pintype "passive"))
      (node (ref "C16") (pin "P$2") (pinfunction "2_P$2") (pintype "passive"))
      (node (ref "C17") (pin "P$2") (pinfunction "2_P$2") (pintype "passive"))
      (node (ref "C18") (pin "P$2") (pinfunction "2_P$2") (pintype "passive"))
      (node (ref "C19") (pin "P$1") (pinfunction "1_P$1") (pintype "passive"))
      (node (ref "C2") (pin "P$2") (pinfunction "2_P$2") (pintype "passive"))
      (node (ref "C20") (pin "P$1") (pinfunction "1_P$1") (pintype "passive"))
      (node (ref "C21") (pin "P$1") (pinfunction "1_P$1") (pintype "passive"))
      (node (ref "C22") (pin "P$1") (pinfunction "1_P$1") (pintype "passive"))
      (node (ref "C23") (pin "P$2") (pinfunction "2_P$2") (pintype "passive"))
      (node (ref "C24") (pin "P$1") (pinfunction "1_P$1") (pintype "passive"))
      (node (ref "C25") (pin "P$1") (pinfunction "1_P$1") (pintype "passive"))
      (node (ref "C26") (pin "P$2") (pinfunction "2_P$2") (pintype "passive"))
      (node (ref "C27") (pin "P$1") (pinfunction "1_P$1") (pintype "passive"))
      (node (ref "C28") (pin "P$2") (pinfunction "2_P$2") (pintype "passive"))
      (node (ref "C29") (pin "P$2") (pinfunction "2_P$2") (pintype "passive"))
      (node (ref "C3") (pin "P$2") (pinfunction "2_P$2") (pintype "passive"))
      (node (ref "C30") (pin "P$1") (pinfunction "1_P$1") (pintype "passive"))
      (node (ref "C31") (pin "2") (pinfunction "2_2") (pintype "passive"))
      (node (ref "C32") (pin "P$2") (pinfunction "2_P$2") (pintype "passive"))
      (node (ref "C33") (pin "P$2") (pinfunction "2_P$2") (pintype "passive"))
      (node (ref "C34") (pin "P$1") (pinfunction "1_P$1") (pintype "passive"))
      (node (ref "C35") (pin "P$1") (pinfunction "1_P$1") (pintype "passive"))
      (node (ref "C36") (pin "P$2") (pinfunction "2_P$2") (pintype "passive"))
      (node (ref "C37") (pin "P$2") (pinfunction "2_P$2") (pintype "passive"))
      (node (ref "C38") (pin "P$1") (pinfunction "1_P$1") (pintype "passive"))
      (node (ref "C39") (pin "P$2") (pinfunction "2_P$2") (pintype "passive"))
      (node (ref "C4") (pin "P$2") (pinfunction "2_P$2") (pintype "passive"))
      (node (ref "C40") (pin "P$2") (pinfunction "2_P$2") (pintype "passive"))
      (node (ref "C41") (pin "P$2") (pinfunction "2_P$2") (pintype "passive"))
      (node (ref "C42") (pin "P$2") (pinfunction "2_P$2") (pintype "passive"))
      (node (ref "C43") (pin "P$1") (pinfunction "1_P$1") (pintype "passive"))
      (node (ref "C5") (pin "P$2") (pinfunction "2_P$2") (pintype "passive"))
      (node (ref "C6") (pin "P$2") (pinfunction "2_P$2") (pintype "passive"))
      (node (ref "C7") (pin "P$2") (pinfunction "2_P$2") (pintype "passive"))
      (node (ref "C8") (pin "P$2") (pinfunction "2_P$2") (pintype "passive"))
      (node (ref "C9") (pin "P$2") (pinfunction "2_P$2") (pintype "passive"))
      (node (ref "J1") (pin "6") (pinfunction "SUPPLY_VOLTAGE_GROUND_6") (pintype "power_in"))
      (node (ref "J10") (pin "2") (pinfunction "2_2") (pintype "passive"))
      (node (ref "J11") (pin "2") (pinfunction "2_2") (pintype "passive"))
      (node (ref "J12") (pin "2") (pinfunction "2_2") (pintype "passive"))
      (node (ref "J19") (pin "2") (pinfunction "2_2") (pintype "passive"))
      (node (ref "J2") (pin "P$1") (pinfunction "P$1_P$1") (pintype "bidirectional"))
      (node (ref "J20") (pin "2") (pinfunction "2_2") (pintype "passive"))
      (node (ref "J27") (pin "2") (pinfunction "2_2") (pintype "passive"))
      (node (ref "J28") (pin "2") (pinfunction "2_2") (pintype "passive"))
      (node (ref "J3") (pin "10") (pinfunction "10_10") (pintype "passive"))
      (node (ref "J3") (pin "6") (pinfunction "6_6") (pintype "passive"))
      (node (ref "J3") (pin "8") (pinfunction "8_8") (pintype "passive"))
      (node (ref "J31") (pin "2") (pinfunction "2_2") (pintype "passive"))
      (node (ref "J32") (pin "2") (pinfunction "2_2") (pintype "passive"))
      (node (ref "J39") (pin "P$1") (pinfunction "P$1_P$1") (pintype "bidirectional"))
      (node (ref "J39") (pin "P$11") (pinfunction "P$11_P$11") (pintype "bidirectional"))
      (node (ref "J39") (pin "P$13") (pinfunction "P$13_P$13") (pintype "bidirectional"))
      (node (ref "J39") (pin "P$15") (pinfunction "P$15_P$15") (pintype "bidirectional"))
      (node (ref "J39") (pin "P$17") (pinfunction "P$17_P$17") (pintype "bidirectional"))
      (node (ref "J39") (pin "P$19") (pinfunction "P$19_P$19") (pintype "bidirectional"))
      (node (ref "J39") (pin "P$3") (pinfunction "P$3_P$3") (pintype "bidirectional"))
      (node (ref "J39") (pin "P$5") (pinfunction "P$5_P$5") (pintype "bidirectional"))
      (node (ref "J39") (pin "P$7") (pinfunction "P$7_P$7") (pintype "bidirectional"))
      (node (ref "J39") (pin "P$9") (pinfunction "P$9_P$9") (pintype "bidirectional"))
      (node (ref "J5") (pin "2") (pinfunction "2_2") (pintype "passive"))
      (node (ref "J6") (pin "GND") (pinfunction "GND_GND") (pintype "power_in"))
      (node (ref "J7") (pin "P$5") (pinfunction "GND_P$5") (pintype "bidirectional"))
      (node (ref "LED1") (pin "2") (pinfunction "C_2") (pintype "passive"))
      (node (ref "LED10") (pin "2") (pinfunction "C_2") (pintype "passive"))
      (node (ref "LED11") (pin "2") (pinfunction "C_2") (pintype "passive"))
      (node (ref "LED12") (pin "2") (pinfunction "C_2") (pintype "passive"))
      (node (ref "LED13") (pin "2") (pinfunction "C_2") (pintype "passive"))
      (node (ref "LED14") (pin "2") (pinfunction "C_2") (pintype "passive"))
      (node (ref "LED15") (pin "2") (pinfunction "C_2") (pintype "passive"))
      (node (ref "LED16") (pin "2") (pinfunction "C_2") (pintype "passive"))
      (node (ref "LED3") (pin "2") (pinfunction "C_2") (pintype "passive"))
      (node (ref "LED6") (pin "2") (pinfunction "C_2") (pintype "passive"))
      (node (ref "LED7") (pin "2") (pinfunction "C_2") (pintype "passive"))
      (node (ref "R1") (pin "P$1") (pinfunction "1_P$1") (pintype "passive"))
      (node (ref "R101") (pin "P$1") (pinfunction "1_P$1") (pintype "passive"))
      (node (ref "R21") (pin "P$1") (pinfunction "1_P$1") (pintype "passive"))
      (node (ref "R22") (pin "P$1") (pinfunction "1_P$1") (pintype "passive"))
      (node (ref "R23") (pin "P$1") (pinfunction "1_P$1") (pintype "passive"))
      (node (ref "R24") (pin "P$1") (pinfunction "1_P$1") (pintype "passive"))
      (node (ref "R34") (pin "P$1") (pinfunction "1_P$1") (pintype "passive"))
      (node (ref "R53") (pin "P$1") (pinfunction "1_P$1") (pintype "passive"))
      (node (ref "R56") (pin "P$1") (pinfunction "1_P$1") (pintype "passive"))
      (node (ref "R59") (pin "P$1") (pinfunction "1_P$1") (pintype "passive"))
      (node (ref "R74") (pin "P$1") (pinfunction "1_P$1") (pintype "passive"))
      (node (ref "R77") (pin "P$1") (pinfunction "1_P$1") (pintype "passive"))
      (node (ref "R80") (pin "P$1") (pinfunction "1_P$1") (pintype "passive"))
      (node (ref "R83") (pin "P$1") (pinfunction "1_P$1") (pintype "passive"))
      (node (ref "R98") (pin "P$1") (pinfunction "1_P$1") (pintype "passive"))
      (node (ref "RJ1") (pin "10") (pinfunction "GLO_10") (pintype "bidirectional"))
      (node (ref "RJ1") (pin "8") (pinfunction "P8_8") (pintype "bidirectional"))
      (node (ref "U1") (pin "22") (pinfunction "GND_22") (pintype "power_in"))
      (node (ref "U1") (pin "25") (pinfunction "25_25") (pintype "passive"))
      (node (ref "U10") (pin "2") (pinfunction "E(1)_2") (pintype "output"))
      (node (ref "U11") (pin "2") (pinfunction "E(1)_2") (pintype "output"))
      (node (ref "U12") (pin "2") (pinfunction "E(1)_2") (pintype "output"))
      (node (ref "U13") (pin "2") (pinfunction "E(1)_2") (pintype "output"))
      (node (ref "U14") (pin "2") (pinfunction "E(1)_2") (pintype "output"))
      (node (ref "U15") (pin "2") (pinfunction "E(1)_2") (pintype "output"))
      (node (ref "U16") (pin "2") (pinfunction "E(1)_2") (pintype "output"))
      (node (ref "U17") (pin "2") (pinfunction "E(1)_2") (pintype "output"))
      (node (ref "U2") (pin "2") (pinfunction "GND_2") (pintype "input"))
      (node (ref "U22") (pin "2") (pinfunction "E(1)_2") (pintype "output"))
      (node (ref "U23") (pin "2") (pinfunction "E(1)_2") (pintype "output"))
      (node (ref "U24") (pin "2") (pinfunction "E(1)_2") (pintype "output"))
      (node (ref "U25") (pin "2") (pinfunction "E(1)_2") (pintype "output"))
      (node (ref "U26") (pin "2") (pinfunction "E(1)_2") (pintype "output"))
      (node (ref "U27") (pin "2") (pinfunction "E(1)_2") (pintype "output"))
      (node (ref "U3") (pin "111") (pinfunction "VSS(IO)5_111") (pintype "bidirectional"))
      (node (ref "U3") (pin "124") (pinfunction "VSS(IO)6_124") (pintype "bidirectional"))
      (node (ref "U3") (pin "139") (pinfunction "VSS(IO)7_139") (pintype "bidirectional"))
      (node (ref "U3") (pin "150") (pinfunction "VSS(IO)8_150") (pintype "bidirectional"))
      (node (ref "U3") (pin "153") (pinfunction "VREFL_153") (pintype "bidirectional"))
      (node (ref "U3") (pin "156") (pinfunction "AVSS0_156") (pintype "bidirectional"))
      (node (ref "U3") (pin "157") (pinfunction "VREFL0_157") (pintype "bidirectional"))
      (node (ref "U3") (pin "170") (pinfunction "VSS(IO)9_170") (pintype "bidirectional"))
      (node (ref "U3") (pin "22") (pinfunction "VSS1_22") (pintype "bidirectional"))
      (node (ref "U3") (pin "28") (pinfunction "AVSS_USBHS_28") (pintype "bidirectional"))
      (node (ref "U3") (pin "29") (pinfunction "PVSS_USBHS_29") (pintype "bidirectional"))
      (node (ref "U3") (pin "30") (pinfunction "VSS2_USBHS_30") (pintype "bidirectional"))
      (node (ref "U3") (pin "33") (pinfunction "VSS1_USBHS_33") (pintype "bidirectional"))
      (node (ref "U3") (pin "35") (pinfunction "VSSIO_35") (pintype "bidirectional"))
      (node (ref "U3") (pin "45") (pinfunction "VSS_USB_45") (pintype "bidirectional"))
      (node (ref "U3") (pin "60") (pinfunction "VSS(IO)2_60") (pintype "bidirectional"))
      (node (ref "U3") (pin "63") (pinfunction "VSS(IO/DCDC)_63") (pintype "bidirectional"))
      (node (ref "U3") (pin "66") (pinfunction "VCC_DCDC(IO/DCDC)_66") (pintype "bidirectional"))
      (node (ref "U3") (pin "83") (pinfunction "VSS(IO)3_83") (pintype "bidirectional"))
      (node (ref "U3") (pin "98") (pinfunction "VSS(IO)4_98") (pintype "bidirectional"))
      (node (ref "U34") (pin "2") (pinfunction "E(1)_2") (pintype "output"))
      (node (ref "U35") (pin "2") (pinfunction "E(1)_2") (pintype "output"))
      (node (ref "U36") (pin "2") (pinfunction "E(1)_2") (pintype "output"))
      (node (ref "U37") (pin "2") (pinfunction "E(1)_2") (pintype "output"))
      (node (ref "U38") (pin "2") (pinfunction "E(1)_2") (pintype "output"))
      (node (ref "U39") (pin "2") (pinfunction "E(1)_2") (pintype "output"))
      (node (ref "U46") (pin "2") (pinfunction "E(1)_2") (pintype "output"))
      (node (ref "U47") (pin "2") (pinfunction "E(1)_2") (pintype "output"))
      (node (ref "U48") (pin "2") (pinfunction "E(1)_2") (pintype "output"))
      (node (ref "U49") (pin "2") (pinfunction "E(1)_2") (pintype "output"))
      (node (ref "U50") (pin "2") (pinfunction "E(1)_2") (pintype "output"))
      (node (ref "U51") (pin "2") (pinfunction "E(1)_2") (pintype "output"))
      (node (ref "U58") (pin "2") (pinfunction "E(1)_2") (pintype "output"))
      (node (ref "U59") (pin "2") (pinfunction "E(1)_2") (pintype "output"))
      (node (ref "U6") (pin "2") (pinfunction "E(1)_2") (pintype "output"))
      (node (ref "U60") (pin "2") (pinfunction "E(1)_2") (pintype "output"))
      (node (ref "U61") (pin "2") (pinfunction "E(1)_2") (pintype "output"))
      (node (ref "U62") (pin "2") (pinfunction "E(1)_2") (pintype "output"))
      (node (ref "U63") (pin "2") (pinfunction "E(1)_2") (pintype "output"))
      (node (ref "U7") (pin "2") (pinfunction "E(1)_2") (pintype "output"))
      (node (ref "U70") (pin "2") (pinfunction "E(1)_2") (pintype "output"))
      (node (ref "U71") (pin "2") (pinfunction "E(1)_2") (pintype "output"))
      (node (ref "U72") (pin "2") (pinfunction "E(1)_2") (pintype "output"))
      (node (ref "U73") (pin "2") (pinfunction "E(1)_2") (pintype "output"))
      (node (ref "U74") (pin "2") (pinfunction "E(1)_2") (pintype "output"))
      (node (ref "U75") (pin "2") (pinfunction "E(1)_2") (pintype "output"))
      (node (ref "X1") (pin "2") (pinfunction "2_2") (pintype "bidirectional"))
      (node (ref "X1") (pin "4") (pinfunction "4_4") (pintype "bidirectional"))
      (node (ref "X2") (pin "2") (pinfunction "2_2") (pintype "bidirectional"))
      (node (ref "X2") (pin "4") (pinfunction "4_4") (pintype "bidirectional"))
    )
    (net (code "48") (name "GNDE") (class "Default")
      (node (ref "J1") (pin "S1") (pinfunction "SHIELD_S1") (pintype "passive"))
      (node (ref "J1") (pin "S2") (pinfunction "SHIELD_S2") (pintype "passive"))
      (node (ref "J1") (pin "S3") (pinfunction "SHIELD_S3") (pintype "passive"))
      (node (ref "J1") (pin "S4") (pinfunction "SHIELD_S4") (pintype "passive"))
      (node (ref "J2") (pin "P$4") (pinfunction "P$4_P$4") (pintype "bidirectional"))
      (node (ref "J6") (pin "SHLD1") (pinfunction "SHIELD_1_SHLD1") (pintype "bidirectional"))
      (node (ref "J6") (pin "SHLD2") (pinfunction "SHIELD_2_SHLD2") (pintype "bidirectional"))
      (node (ref "J7") (pin "P$6") (pinfunction "SHIELD1_P$6") (pintype "bidirectional"))
      (node (ref "J7") (pin "P$7") (pinfunction "SHIELD2_P$7") (pintype "bidirectional"))
      (node (ref "J7") (pin "P$8") (pinfunction "SHIELD3_P$8") (pintype "bidirectional"))
      (node (ref "J7") (pin "P$9") (pinfunction "SHIELD4_P$9") (pintype "bidirectional"))
      (node (ref "RJ1") (pin "13") (pinfunction "GNDE0_13") (pintype "bidirectional"))
      (node (ref "RJ1") (pin "14") (pinfunction "GNDE1_14") (pintype "bidirectional"))
    )
    (net (code "49") (name "ID") (class "Default")
      (node (ref "J7") (pin "P$4") (pinfunction "ID_P$4") (pintype "bidirectional"))
    )
    (net (code "50") (name "IIC_1_SCL") (class "Default")
      (node (ref "J8") (pin "P$8") (pinfunction "P$8_P$8") (pintype "bidirectional"))
      (node (ref "R14") (pin "P$2") (pinfunction "2_P$2") (pintype "passive"))
      (node (ref "U3") (pin "132") (pinfunction "P1_0_132") (pintype "bidirectional"))
    )
    (net (code "51") (name "IIC_1_SDA") (class "Default")
      (node (ref "J8") (pin "P$7") (pinfunction "P$7_P$7") (pintype "bidirectional"))
      (node (ref "R15") (pin "P$2") (pinfunction "2_P$2") (pintype "passive"))
      (node (ref "U3") (pin "131") (pinfunction "P1_1_131") (pintype "bidirectional"))
    )
    (net (code "52") (name "LED1{slash}SPEED") (class "Default")
      (node (ref "RJ1") (pin "11") (pinfunction "YLO_11") (pintype "bidirectional"))
      (node (ref "U1") (pin "23") (pinfunction "LED0/ANEN_SPEED_23") (pintype "bidirectional"))
    )
    (net (code "53") (name "LS_01") (class "Default")
      (node (ref "R33") (pin "P$2") (pinfunction "2_P$2") (pintype "passive"))
      (node (ref "R34") (pin "P$2") (pinfunction "2_P$2") (pintype "passive"))
      (node (ref "U3") (pin "50") (pinfunction "P2_6_50") (pintype "bidirectional"))
      (node (ref "U5") (pin "2") (pinfunction "E(1)_2") (pintype "output"))
    )
    (net (code "54") (name "LS_01_RET") (class "Default")
      (node (ref "J32") (pin "1") (pinfunction "1_1") (pintype "passive"))
      (node (ref "R28") (pin "P$1") (pinfunction "1_P$1") (pintype "passive"))
    )
    (net (code "55") (name "LS_02") (class "Default")
      (node (ref "R36") (pin "P$2") (pinfunction "2_P$2") (pintype "passive"))
      (node (ref "R53") (pin "P$2") (pinfunction "2_P$2") (pintype "passive"))
      (node (ref "U3") (pin "51") (pinfunction "P2_5_51") (pintype "bidirectional"))
      (node (ref "U8") (pin "2") (pinfunction "E(1)_2") (pintype "output"))
    )
    (net (code "56") (name "LS_02_RET") (class "Default")
      (node (ref "J31") (pin "1") (pinfunction "1_1") (pintype "passive"))
      (node (ref "R35") (pin "P$1") (pinfunction "1_P$1") (pintype "passive"))
    )
    (net (code "57") (name "LS_03") (class "Default")
      (node (ref "R55") (pin "P$2") (pinfunction "2_P$2") (pintype "passive"))
      (node (ref "R56") (pin "P$2") (pinfunction "2_P$2") (pintype "passive"))
      (node (ref "U3") (pin "53") (pinfunction "P2_3_53") (pintype "bidirectional"))
      (node (ref "U9") (pin "2") (pinfunction "E(1)_2") (pintype "output"))
    )
    (net (code "58") (name "LS_03_RET") (class "Default")
      (node (ref "J28") (pin "1") (pinfunction "1_1") (pintype "passive"))
      (node (ref "R54") (pin "P$1") (pinfunction "1_P$1") (pintype "passive"))
    )
    (net (code "59") (name "LS_04") (class "Default")
      (node (ref "R73") (pin "P$2") (pinfunction "2_P$2") (pintype "passive"))
      (node (ref "R74") (pin "P$2") (pinfunction "2_P$2") (pintype "passive"))
      (node (ref "U19") (pin "2") (pinfunction "E(1)_2") (pintype "output"))
      (node (ref "U3") (pin "54") (pinfunction "P2_2_54") (pintype "bidirectional"))
    )
    (net (code "60") (name "LS_04_RET") (class "Default")
      (node (ref "J27") (pin "1") (pinfunction "1_1") (pintype "passive"))
      (node (ref "R60") (pin "P$1") (pinfunction "1_P$1") (pintype "passive"))
    )
    (net (code "61") (name "LS_05") (class "Default")
      (node (ref "R58") (pin "P$2") (pinfunction "2_P$2") (pintype "passive"))
      (node (ref "R59") (pin "P$2") (pinfunction "2_P$2") (pintype "passive"))
      (node (ref "U18") (pin "2") (pinfunction "E(1)_2") (pintype "output"))
      (node (ref "U3") (pin "81") (pinfunction "P3_5_81") (pintype "bidirectional"))
    )
    (net (code "62") (name "LS_05_RET") (class "Default")
      (node (ref "J19") (pin "1") (pinfunction "1_1") (pintype "passive"))
      (node (ref "R57") (pin "P$1") (pinfunction "1_P$1") (pintype "passive"))
    )
    (net (code "63") (name "LS_06") (class "Default")
      (node (ref "R76") (pin "P$2") (pinfunction "2_P$2") (pintype "passive"))
      (node (ref "R77") (pin "P$2") (pinfunction "2_P$2") (pintype "passive"))
      (node (ref "U20") (pin "2") (pinfunction "E(1)_2") (pintype "output"))
      (node (ref "U3") (pin "82") (pinfunction "P3_4_82") (pintype "bidirectional"))
    )
    (net (code "64") (name "LS_06_RET") (class "Default")
      (node (ref "J12") (pin "1") (pinfunction "1_1") (pintype "passive"))
      (node (ref "R75") (pin "P$1") (pinfunction "1_P$1") (pintype "passive"))
    )
    (net (code "65") (name "LS_07") (class "Default")
      (node (ref "R97") (pin "P$2") (pinfunction "2_P$2") (pintype "passive"))
      (node (ref "R98") (pin "P$2") (pinfunction "2_P$2") (pintype "passive"))
      (node (ref "U29") (pin "2") (pinfunction "E(1)_2") (pintype "output"))
      (node (ref "U3") (pin "86") (pinfunction "P3_2_86") (pintype "bidirectional"))
    )
    (net (code "66") (name "LS_07_RET") (class "Default")
      (node (ref "J11") (pin "1") (pinfunction "1_1") (pintype "passive"))
      (node (ref "R84") (pin "P$1") (pinfunction "1_P$1") (pintype "passive"))
    )
    (net (code "67") (name "LS_08") (class "Default")
      (node (ref "R82") (pin "P$2") (pinfunction "2_P$2") (pintype "passive"))
      (node (ref "R83") (pin "P$2") (pinfunction "2_P$2") (pintype "passive"))
      (node (ref "U28") (pin "2") (pinfunction "E(1)_2") (pintype "output"))
      (node (ref "U3") (pin "87") (pinfunction "P3_1_87") (pintype "bidirectional"))
    )
    (net (code "68") (name "LS_08_RET") (class "Default")
      (node (ref "J5") (pin "1") (pinfunction "1_1") (pintype "passive"))
      (node (ref "R81") (pin "P$1") (pinfunction "1_P$1") (pintype "passive"))
    )
    (net (code "69") (name "LS_09") (class "Default")
      (node (ref "R100") (pin "P$2") (pinfunction "2_P$2") (pintype "passive"))
      (node (ref "R101") (pin "P$2") (pinfunction "2_P$2") (pintype "passive"))
      (node (ref "U3") (pin "92") (pinfunction "P1_11_92") (pintype "bidirectional"))
      (node (ref "U30") (pin "2") (pinfunction "E(1)_2") (pintype "output"))
    )
    (net (code "70") (name "LS_09_RET") (class "Default")
      (node (ref "J10") (pin "1") (pinfunction "1_1") (pintype "passive"))
      (node (ref "R99") (pin "P$1") (pinfunction "1_P$1") (pintype "passive"))
    )
    (net (code "71") (name "N$88") (class "Default")
      (node (ref "J8") (pin "P$20") (pinfunction "P$20_P$20") (pintype "bidirectional"))
    )
    (net (code "72") (name "N$89") (class "Default")
      (node (ref "J8") (pin "P$18") (pinfunction "P$18_P$18") (pintype "bidirectional"))
    )
    (net (code "73") (name "N$90") (class "Default")
      (node (ref "J8") (pin "P$16") (pinfunction "P$16_P$16") (pintype "bidirectional"))
    )
    (net (code "74") (name "N$91") (class "Default")
      (node (ref "J8") (pin "P$14") (pinfunction "P$14_P$14") (pintype "bidirectional"))
    )
    (net (code "75") (name "N$92") (class "Default")
      (node (ref "J8") (pin "P$12") (pinfunction "P$12_P$12") (pintype "bidirectional"))
    )
    (net (code "76") (name "NC") (class "Default")
      (node (ref "J8") (pin "P$6") (pinfunction "P$6_P$6") (pintype "bidirectional"))
      (node (ref "RJ1") (pin "7") (pinfunction "P7_7") (pintype "bidirectional"))
      (node (ref "U3") (pin "79") (pinfunction "P3_7_79") (pintype "bidirectional"))
      (node (ref "U3") (pin "80") (pinfunction "P3_6_80") (pintype "bidirectional"))
      (node (ref "U3") (pin "85") (pinfunction "P3_3_85") (pintype "bidirectional"))
    )
    (net (code "77") (name "Net-(C8-1)") (class "Default")
      (node (ref "C8") (pin "P$1") (pinfunction "1_P$1") (pintype "passive"))
      (node (ref "C9") (pin "P$1") (pinfunction "1_P$1") (pintype "passive"))
      (node (ref "FB1") (pin "2") (pinfunction "P$2_2") (pintype "bidirectional"))
      (node (ref "U1") (pin "2") (pinfunction "VDDA_3.3_2") (pintype "power_in"))
    )
    (net (code "78") (name "Net-(C24-2)") (class "Default")
      (node (ref "C24") (pin "P$2") (pinfunction "2_P$2") (pintype "passive"))
      (node (ref "U3") (pin "148") (pinfunction "VCL2_148") (pintype "bidirectional"))
    )
    (net (code "79") (name "Net-(C28-1)") (class "Default")
      (node (ref "C28") (pin "P$1") (pinfunction "1_P$1") (pintype "passive"))
      (node (ref "J7") (pin "P$1") (pinfunction "VBUS_P$1") (pintype "bidirectional"))
      (node (ref "R16") (pin "P$2") (pinfunction "2_P$2") (pintype "passive"))
      (node (ref "R21") (pin "P$2") (pinfunction "2_P$2") (pintype "passive"))
    )
    (net (code "80") (name "Net-(C33-1)") (class "Default")
      (node (ref "C33") (pin "P$1") (pinfunction "1_P$1") (pintype "passive"))
      (node (ref "U3") (pin "19") (pinfunction "VCLO_19") (pintype "bidirectional"))
    )
    (net (code "81") (name "Net-(C42-1)") (class "Default")
      (node (ref "C42") (pin "P$1") (pinfunction "1_P$1") (pintype "passive"))
      (node (ref "U3") (pin "62") (pinfunction "VCL1_62") (pintype "bidirectional"))
    )
    (net (code "82") (name "Net-(J7-D+)") (class "Default")
      (node (ref "J7") (pin "P$3") (pinfunction "D+_P$3") (pintype "bidirectional"))
      (node (ref "R18") (pin "P$2") (pinfunction "2_P$2") (pintype "passive"))
    )
    (net (code "83") (name "Net-(J7-D-)") (class "Default")
      (node (ref "J7") (pin "P$2") (pinfunction "D-_P$2") (pintype "bidirectional"))
      (node (ref "R17") (pin "P$2") (pinfunction "2_P$2") (pintype "passive"))
    )
    (net (code "84") (name "Net-(LED1-A)") (class "Default")
      (node (ref "LED1") (pin "1") (pinfunction "A_1") (pintype "passive"))
      (node (ref "R5") (pin "P$1") (pinfunction "1_P$1") (pintype "passive"))
    )
    (net (code "85") (name "Net-(LED3-A)") (class "Default")
      (node (ref "LED3") (pin "1") (pinfunction "A_1") (pintype "passive"))
      (node (ref "R33") (pin "P$1") (pinfunction "1_P$1") (pintype "passive"))
    )
    (net (code "86") (name "Net-(LED4-A)") (class "Default")
      (node (ref "LED4") (pin "1") (pinfunction "A_1") (pintype "passive"))
      (node (ref "R32") (pin "P$1") (pinfunction "1_P$1") (pintype "passive"))
    )
    (net (code "87") (name "Net-(LED4-C)") (class "Default")
      (node (ref "LED4") (pin "2") (pinfunction "C_2") (pintype "passive"))
      (node (ref "U$1") (pin "P$1") (pinfunction "VC-_P$1") (pintype "bidirectional"))
      (node (ref "U6") (pin "3") (pinfunction "C(3)_3") (pintype "input"))
    )
    (net (code "88") (name "Net-(LED5-A)") (class "Default")
      (node (ref "LED5") (pin "1") (pinfunction "A_1") (pintype "passive"))
      (node (ref "R31") (pin "P$1") (pinfunction "1_P$1") (pintype "passive"))
    )
    (net (code "89") (name "Net-(LED5-C)") (class "Default")
      (node (ref "LED5") (pin "2") (pinfunction "C_2") (pintype "passive"))
      (node (ref "U$2") (pin "P$1") (pinfunction "VC-_P$1") (pintype "bidirectional"))
      (node (ref "U7") (pin "3") (pinfunction "C(3)_3") (pintype "input"))
    )
    (net (code "90") (name "Net-(LED6-A)") (class "Default")
      (node (ref "LED6") (pin "1") (pinfunction "A_1") (pintype "passive"))
      (node (ref "R36") (pin "P$1") (pinfunction "1_P$1") (pintype "passive"))
    )
    (net (code "91") (name "Net-(LED7-A)") (class "Default")
      (node (ref "LED7") (pin "1") (pinfunction "A_1") (pintype "passive"))
      (node (ref "R55") (pin "P$1") (pinfunction "1_P$1") (pintype "passive"))
    )
    (net (code "92") (name "Net-(LED8-A)") (class "Default")
      (node (ref "LED8") (pin "1") (pinfunction "A_1") (pintype "passive"))
      (node (ref "R52") (pin "P$1") (pinfunction "1_P$1") (pintype "passive"))
    )
    (net (code "93") (name "Net-(LED8-C)") (class "Default")
      (node (ref "LED8") (pin "2") (pinfunction "C_2") (pintype "passive"))
      (node (ref "U$7") (pin "P$1") (pinfunction "VC-_P$1") (pintype "bidirectional"))
      (node (ref "U16") (pin "3") (pinfunction "C(3)_3") (pintype "input"))
    )
    (net (code "94") (name "Net-(LED9-A)") (class "Default")
      (node (ref "LED9") (pin "1") (pinfunction "A_1") (pintype "passive"))
      (node (ref "R51") (pin "P$1") (pinfunction "1_P$1") (pintype "passive"))
    )
    (net (code "95") (name "Net-(LED9-C)") (class "Default")
      (node (ref "LED9") (pin "2") (pinfunction "C_2") (pintype "passive"))
      (node (ref "U$8") (pin "P$1") (pinfunction "VC-_P$1") (pintype "bidirectional"))
      (node (ref "U17") (pin "3") (pinfunction "C(3)_3") (pintype "input"))
    )
    (net (code "96") (name "Net-(LED10-A)") (class "Default")
      (node (ref "LED10") (pin "1") (pinfunction "A_1") (pintype "passive"))
      (node (ref "R58") (pin "P$1") (pinfunction "1_P$1") (pintype "passive"))
    )
    (net (code "97") (name "Net-(LED11-A)") (class "Default")
      (node (ref "LED11") (pin "1") (pinfunction "A_1") (pintype "passive"))
      (node (ref "R73") (pin "P$1") (pinfunction "1_P$1") (pintype "passive"))
    )
    (net (code "98") (name "Net-(LED12-A)") (class "Default")
      (node (ref "LED12") (pin "1") (pinfunction "A_1") (pintype "passive"))
      (node (ref "R76") (pin "P$1") (pinfunction "1_P$1") (pintype "passive"))
    )
    (net (code "99") (name "Net-(LED13-A)") (class "Default")
      (node (ref "LED13") (pin "1") (pinfunction "A_1") (pintype "passive"))
      (node (ref "R79") (pin "P$1") (pinfunction "1_P$1") (pintype "passive"))
    )
    (net (code "100") (name "Net-(LED14-A)") (class "Default")
      (node (ref "LED14") (pin "1") (pinfunction "A_1") (pintype "passive"))
      (node (ref "R82") (pin "P$1") (pinfunction "1_P$1") (pintype "passive"))
    )
    (net (code "101") (name "Net-(LED15-A)") (class "Default")
      (node (ref "LED15") (pin "1") (pinfunction "A_1") (pintype "passive"))
      (node (ref "R97") (pin "P$1") (pinfunction "1_P$1") (pintype "passive"))
    )
    (net (code "102") (name "Net-(LED16-A)") (class "Default")
      (node (ref "LED16") (pin "1") (pinfunction "A_1") (pintype "passive"))
      (node (ref "R100") (pin "P$1") (pinfunction "1_P$1") (pintype "passive"))
    )
    (net (code "103") (name "Net-(R22-2)") (class "Default")
      (node (ref "R22") (pin "P$2") (pinfunction "2_P$2") (pintype "passive"))
      (node (ref "U3") (pin "27") (pinfunction "USBHS_RREF_27") (pintype "bidirectional"))
    )
    (net (code "104") (name "Net-(R23-2)") (class "Default")
      (node (ref "R23") (pin "P$2") (pinfunction "2_P$2") (pintype "passive"))
      (node (ref "U3") (pin "64") (pinfunction "VLO1(DCDC)_64") (pintype "bidirectional"))
    )
    (net (code "105") (name "Net-(R24-2)") (class "Default")
      (node (ref "R24") (pin "P$2") (pinfunction "2_P$2") (pintype "passive"))
      (node (ref "U3") (pin "65") (pinfunction "VLO2(DCDC)_65") (pintype "bidirectional"))
    )
    (net (code "106") (name "Net-(R28-2)") (class "Default")
      (node (ref "R28") (pin "P$2") (pinfunction "2_P$2") (pintype "passive"))
      (node (ref "U5") (pin "1") (pinfunction "B(2)_1") (pintype "input"))
    )
    (net (code "107") (name "Net-(R29-2)") (class "Default")
      (node (ref "R29") (pin "P$2") (pinfunction "2_P$2") (pintype "passive"))
      (node (ref "U6") (pin "1") (pinfunction "B(2)_1") (pintype "input"))
    )
    (net (code "108") (name "Net-(R30-2)") (class "Default")
      (node (ref "R30") (pin "P$2") (pinfunction "2_P$2") (pintype "passive"))
      (node (ref "U7") (pin "1") (pinfunction "B(2)_1") (pintype "input"))
    )
    (net (code "109") (name "Net-(R35-2)") (class "Default")
      (node (ref "R35") (pin "P$2") (pinfunction "2_P$2") (pintype "passive"))
      (node (ref "U8") (pin "1") (pinfunction "B(2)_1") (pintype "input"))
    )
    (net (code "110") (name "Net-(R49-2)") (class "Default")
      (node (ref "R49") (pin "P$2") (pinfunction "2_P$2") (pintype "passive"))
      (node (ref "U16") (pin "1") (pinfunction "B(2)_1") (pintype "input"))
    )
    (net (code "111") (name "Net-(R50-2)") (class "Default")
      (node (ref "R50") (pin "P$2") (pinfunction "2_P$2") (pintype "passive"))
      (node (ref "U17") (pin "1") (pinfunction "B(2)_1") (pintype "input"))
    )
    (net (code "112") (name "Net-(R54-2)") (class "Default")
      (node (ref "R54") (pin "P$2") (pinfunction "2_P$2") (pintype "passive"))
      (node (ref "U9") (pin "1") (pinfunction "B(2)_1") (pintype "input"))
    )
    (net (code "113") (name "Net-(R57-2)") (class "Default")
      (node (ref "R57") (pin "P$2") (pinfunction "2_P$2") (pintype "passive"))
      (node (ref "U18") (pin "1") (pinfunction "B(2)_1") (pintype "input"))
    )
    (net (code "114") (name "Net-(R60-2)") (class "Default")
      (node (ref "R60") (pin "P$2") (pinfunction "2_P$2") (pintype "passive"))
      (node (ref "U19") (pin "1") (pinfunction "B(2)_1") (pintype "input"))
    )
    (net (code "115") (name "Net-(R75-2)") (class "Default")
      (node (ref "R75") (pin "P$2") (pinfunction "2_P$2") (pintype "passive"))
      (node (ref "U20") (pin "1") (pinfunction "B(2)_1") (pintype "input"))
    )
    (net (code "116") (name "Net-(R78-2)") (class "Default")
      (node (ref "R78") (pin "P$2") (pinfunction "2_P$2") (pintype "passive"))
      (node (ref "U21") (pin "1") (pinfunction "B(2)_1") (pintype "input"))
    )
    (net (code "117") (name "Net-(R81-2)") (class "Default")
      (node (ref "R81") (pin "P$2") (pinfunction "2_P$2") (pintype "passive"))
      (node (ref "U28") (pin "1") (pinfunction "B(2)_1") (pintype "input"))
    )
    (net (code "118") (name "Net-(R84-2)") (class "Default")
      (node (ref "R84") (pin "P$2") (pinfunction "2_P$2") (pintype "passive"))
      (node (ref "U29") (pin "1") (pinfunction "B(2)_1") (pintype "input"))
    )
    (net (code "119") (name "Net-(R99-2)") (class "Default")
      (node (ref "R99") (pin "P$2") (pinfunction "2_P$2") (pintype "passive"))
      (node (ref "U30") (pin "1") (pinfunction "B(2)_1") (pintype "input"))
    )
    (net (code "120") (name "Net-(U10-B(2))") (class "Default")
      (node (ref "R38") (pin "2") (pinfunction "2_2") (pintype "passive"))
      (node (ref "U10") (pin "1") (pinfunction "B(2)_1") (pintype "input"))
    )
    (net (code "121") (name "Net-(U11-B(2))") (class "Default")
      (node (ref "R39") (pin "2") (pinfunction "2_2") (pintype "passive"))
      (node (ref "U11") (pin "1") (pinfunction "B(2)_1") (pintype "input"))
    )
    (net (code "122") (name "Net-(U12-B(2))") (class "Default")
      (node (ref "R40") (pin "2") (pinfunction "2_2") (pintype "passive"))
      (node (ref "U12") (pin "1") (pinfunction "B(2)_1") (pintype "input"))
    )
    (net (code "123") (name "Net-(U13-B(2))") (class "Default")
      (node (ref "R44") (pin "2") (pinfunction "2_2") (pintype "passive"))
      (node (ref "U13") (pin "1") (pinfunction "B(2)_1") (pintype "input"))
    )
    (net (code "124") (name "Net-(U14-B(2))") (class "Default")
      (node (ref "R45") (pin "2") (pinfunction "2_2") (pintype "passive"))
      (node (ref "U14") (pin "1") (pinfunction "B(2)_1") (pintype "input"))
    )
    (net (code "125") (name "Net-(U15-B(2))") (class "Default")
      (node (ref "R46") (pin "2") (pinfunction "2_2") (pintype "passive"))
      (node (ref "U15") (pin "1") (pinfunction "B(2)_1") (pintype "input"))
    )
    (net (code "126") (name "Net-(U22-B(2))") (class "Default")
      (node (ref "R62") (pin "2") (pinfunction "2_2") (pintype "passive"))
      (node (ref "U22") (pin "1") (pinfunction "B(2)_1") (pintype "input"))
    )
    (net (code "127") (name "Net-(U23-B(2))") (class "Default")
      (node (ref "R63") (pin "2") (pinfunction "2_2") (pintype "passive"))
      (node (ref "U23") (pin "1") (pinfunction "B(2)_1") (pintype "input"))
    )
    (net (code "128") (name "Net-(U24-B(2))") (class "Default")
      (node (ref "R64") (pin "2") (pinfunction "2_2") (pintype "passive"))
      (node (ref "U24") (pin "1") (pinfunction "B(2)_1") (pintype "input"))
    )
    (net (code "129") (name "Net-(U25-B(2))") (class "Default")
      (node (ref "R68") (pin "2") (pinfunction "2_2") (pintype "passive"))
      (node (ref "U25") (pin "1") (pinfunction "B(2)_1") (pintype "input"))
    )
    (net (code "130") (name "Net-(U26-B(2))") (class "Default")
      (node (ref "R69") (pin "2") (pinfunction "2_2") (pintype "passive"))
      (node (ref "U26") (pin "1") (pinfunction "B(2)_1") (pintype "input"))
    )
    (net (code "131") (name "Net-(U27-B(2))") (class "Default")
      (node (ref "R70") (pin "2") (pinfunction "2_2") (pintype "passive"))
      (node (ref "U27") (pin "1") (pinfunction "B(2)_1") (pintype "input"))
    )
    (net (code "132") (name "Net-(U34-B(2))") (class "Default")
      (node (ref "R86") (pin "2") (pinfunction "2_2") (pintype "passive"))
      (node (ref "U34") (pin "1") (pinfunction "B(2)_1") (pintype "input"))
    )
    (net (code "133") (name "Net-(U35-B(2))") (class "Default")
      (node (ref "R87") (pin "2") (pinfunction "2_2") (pintype "passive"))
      (node (ref "U35") (pin "1") (pinfunction "B(2)_1") (pintype "input"))
    )
    (net (code "134") (name "Net-(U36-B(2))") (class "Default")
      (node (ref "R88") (pin "2") (pinfunction "2_2") (pintype "passive"))
      (node (ref "U36") (pin "1") (pinfunction "B(2)_1") (pintype "input"))
    )
    (net (code "135") (name "Net-(U37-B(2))") (class "Default")
      (node (ref "R92") (pin "2") (pinfunction "2_2") (pintype "passive"))
      (node (ref "U37") (pin "1") (pinfunction "B(2)_1") (pintype "input"))
    )
    (net (code "136") (name "Net-(U38-B(2))") (class "Default")
      (node (ref "R93") (pin "2") (pinfunction "2_2") (pintype "passive"))
      (node (ref "U38") (pin "1") (pinfunction "B(2)_1") (pintype "input"))
    )
    (net (code "137") (name "Net-(U39-B(2))") (class "Default")
      (node (ref "R94") (pin "2") (pinfunction "2_2") (pintype "passive"))
      (node (ref "U39") (pin "1") (pinfunction "B(2)_1") (pintype "input"))
    )
    (net (code "138") (name "Net-(U46-B(2))") (class "Default")
      (node (ref "R110") (pin "2") (pinfunction "2_2") (pintype "passive"))
      (node (ref "U46") (pin "1") (pinfunction "B(2)_1") (pintype "input"))
    )
    (net (code "139") (name "Net-(U47-B(2))") (class "Default")
      (node (ref "R111") (pin "2") (pinfunction "2_2") (pintype "passive"))
      (node (ref "U47") (pin "1") (pinfunction "B(2)_1") (pintype "input"))
    )
    (net (code "140") (name "Net-(U48-B(2))") (class "Default")
      (node (ref "R112") (pin "2") (pinfunction "2_2") (pintype "passive"))
      (node (ref "U48") (pin "1") (pinfunction "B(2)_1") (pintype "input"))
    )
    (net (code "141") (name "Net-(U49-B(2))") (class "Default")
      (node (ref "R116") (pin "2") (pinfunction "2_2") (pintype "passive"))
      (node (ref "U49") (pin "1") (pinfunction "B(2)_1") (pintype "input"))
    )
    (net (code "142") (name "Net-(U50-B(2))") (class "Default")
      (node (ref "R117") (pin "2") (pinfunction "2_2") (pintype "passive"))
      (node (ref "U50") (pin "1") (pinfunction "B(2)_1") (pintype "input"))
    )
    (net (code "143") (name "Net-(U51-B(2))") (class "Default")
      (node (ref "R118") (pin "2") (pinfunction "2_2") (pintype "passive"))
      (node (ref "U51") (pin "1") (pinfunction "B(2)_1") (pintype "input"))
    )
    (net (code "144") (name "Net-(U58-B(2))") (class "Default")
      (node (ref "R134") (pin "2") (pinfunction "2_2") (pintype "passive"))
      (node (ref "U58") (pin "1") (pinfunction "B(2)_1") (pintype "input"))
    )
    (net (code "145") (name "Net-(U59-B(2))") (class "Default")
      (node (ref "R135") (pin "2") (pinfunction "2_2") (pintype "passive"))
      (node (ref "U59") (pin "1") (pinfunction "B(2)_1") (pintype "input"))
    )
    (net (code "146") (name "Net-(U60-B(2))") (class "Default")
      (node (ref "R136") (pin "2") (pinfunction "2_2") (pintype "passive"))
      (node (ref "U60") (pin "1") (pinfunction "B(2)_1") (pintype "input"))
    )
    (net (code "147") (name "Net-(U61-B(2))") (class "Default")
      (node (ref "R140") (pin "2") (pinfunction "2_2") (pintype "passive"))
      (node (ref "U61") (pin "1") (pinfunction "B(2)_1") (pintype "input"))
    )
    (net (code "148") (name "Net-(U62-B(2))") (class "Default")
      (node (ref "R141") (pin "2") (pinfunction "2_2") (pintype "passive"))
      (node (ref "U62") (pin "1") (pinfunction "B(2)_1") (pintype "input"))
    )
    (net (code "149") (name "Net-(U63-B(2))") (class "Default")
      (node (ref "R142") (pin "2") (pinfunction "2_2") (pintype "passive"))
      (node (ref "U63") (pin "1") (pinfunction "B(2)_1") (pintype "input"))
    )
    (net (code "150") (name "Net-(U70-B(2))") (class "Default")
      (node (ref "R158") (pin "2") (pinfunction "2_2") (pintype "passive"))
      (node (ref "U70") (pin "1") (pinfunction "B(2)_1") (pintype "input"))
    )
    (net (code "151") (name "Net-(U71-B(2))") (class "Default")
      (node (ref "R159") (pin "2") (pinfunction "2_2") (pintype "passive"))
      (node (ref "U71") (pin "1") (pinfunction "B(2)_1") (pintype "input"))
    )
    (net (code "152") (name "Net-(U72-B(2))") (class "Default")
      (node (ref "R160") (pin "2") (pinfunction "2_2") (pintype "passive"))
      (node (ref "U72") (pin "1") (pinfunction "B(2)_1") (pintype "input"))
    )
    (net (code "153") (name "Net-(U73-B(2))") (class "Default")
      (node (ref "R164") (pin "2") (pinfunction "2_2") (pintype "passive"))
      (node (ref "U73") (pin "1") (pinfunction "B(2)_1") (pintype "input"))
    )
    (net (code "154") (name "Net-(U74-B(2))") (class "Default")
      (node (ref "R165") (pin "2") (pinfunction "2_2") (pintype "passive"))
      (node (ref "U74") (pin "1") (pinfunction "B(2)_1") (pintype "input"))
    )
    (net (code "155") (name "Net-(U75-B(2))") (class "Default")
      (node (ref "R166") (pin "2") (pinfunction "2_2") (pintype "passive"))
      (node (ref "U75") (pin "1") (pinfunction "B(2)_1") (pintype "input"))
    )
    (net (code "156") (name "P0_00") (class "Default")
      (node (ref "J4") (pin "P$2") (pinfunction "P$2_P$2") (pintype "bidirectional"))
      (node (ref "U3") (pin "169") (pinfunction "P0_0/AN0\\00_169") (pintype "bidirectional"))
    )
    (net (code "157") (name "P0_01") (class "Default")
      (node (ref "J4") (pin "P$1") (pinfunction "P$1_P$1") (pintype "bidirectional"))
      (node (ref "U3") (pin "168") (pinfunction "P0_1/AN001_168") (pintype "bidirectional"))
    )
    (net (code "158") (name "P0_02") (class "Default")
      (node (ref "J39") (pin "P$20") (pinfunction "P$20_P$20") (pintype "bidirectional"))
      (node (ref "R25") (pin "P$1") (pinfunction "1_P$1") (pintype "passive"))
      (node (ref "U3") (pin "167") (pinfunction "P0_2/AN002_167") (pintype "bidirectional"))
    )
    (net (code "159") (name "P0_03") (class "Default")
      (node (ref "J39") (pin "P$18") (pinfunction "P$18_P$18") (pintype "bidirectional"))
      (node (ref "R26") (pin "P$1") (pinfunction "1_P$1") (pintype "passive"))
      (node (ref "U3") (pin "166") (pinfunction "P0_3/PGAVSS000_166") (pintype "bidirectional"))
    )
    (net (code "160") (name "P0_04") (class "Default")
      (node (ref "J39") (pin "P$16") (pinfunction "P$16_P$16") (pintype "bidirectional"))
      (node (ref "R27") (pin "P$1") (pinfunction "1_P$1") (pintype "passive"))
      (node (ref "U3") (pin "165") (pinfunction "P0_4/AN100_165") (pintype "bidirectional"))
    )
    (net (code "161") (name "P0_05") (class "Default")
      (node (ref "J39") (pin "P$14") (pinfunction "P$14_P$14") (pintype "bidirectional"))
      (node (ref "R102") (pin "P$1") (pinfunction "1_P$1") (pintype "passive"))
      (node (ref "U3") (pin "164") (pinfunction "P0_5/AN101_164") (pintype "bidirectional"))
    )
    (net (code "162") (name "P0_06") (class "Default")
      (node (ref "J39") (pin "P$12") (pinfunction "P$12_P$12") (pintype "bidirectional"))
      (node (ref "R103") (pin "P$1") (pinfunction "1_P$1") (pintype "passive"))
      (node (ref "U3") (pin "163") (pinfunction "P0_6/AN102_163") (pintype "bidirectional"))
    )
    (net (code "163") (name "P0_07") (class "Default")
      (node (ref "J39") (pin "P$10") (pinfunction "P$10_P$10") (pintype "bidirectional"))
      (node (ref "R104") (pin "P$1") (pinfunction "1_P$1") (pintype "passive"))
      (node (ref "U3") (pin "162") (pinfunction "P0_7/PGVSS100_162") (pintype "bidirectional"))
    )
    (net (code "164") (name "P0_08") (class "Default")
      (node (ref "J39") (pin "P$8") (pinfunction "P$8_P$8") (pintype "bidirectional"))
      (node (ref "R105") (pin "P$1") (pinfunction "1_P$1") (pintype "passive"))
      (node (ref "U3") (pin "161") (pinfunction "P0_8/AN003_161") (pintype "bidirectional"))
    )
    (net (code "165") (name "P0_09") (class "Default")
      (node (ref "J39") (pin "P$6") (pinfunction "P$6_P$6") (pintype "bidirectional"))
      (node (ref "R106") (pin "P$1") (pinfunction "1_P$1") (pintype "passive"))
      (node (ref "U3") (pin "160") (pinfunction "P0_9/AN004_160") (pintype "bidirectional"))
    )
    (net (code "166") (name "P0_14") (class "Default")
      (node (ref "J39") (pin "P$4") (pinfunction "P$4_P$4") (pintype "bidirectional"))
      (node (ref "R107") (pin "P$1") (pinfunction "1_P$1") (pintype "passive"))
      (node (ref "U3") (pin "152") (pinfunction "P0_14/DA0/AN005/AN105_152") (pintype "bidirectional"))
    )
    (net (code "167") (name "P0_15") (class "Default")
      (node (ref "J39") (pin "P$2") (pinfunction "P$2_P$2") (pintype "bidirectional"))
      (node (ref "R108") (pin "P$1") (pinfunction "1_P$1") (pintype "passive"))
      (node (ref "U3") (pin "151") (pinfunction "P0_15/DA1/AN006/AN106_151") (pintype "bidirectional"))
    )
    (net (code "168") (name "P1_02") (class "Default")
      (node (ref "J8") (pin "P$10") (pinfunction "P$10_P$10") (pintype "bidirectional"))
      (node (ref "U3") (pin "130") (pinfunction "P1_2_130") (pintype "bidirectional"))
    )
    (net (code "169") (name "P1_03") (class "Default")
      (node (ref "J8") (pin "P$9") (pinfunction "P$9_P$9") (pintype "bidirectional"))
      (node (ref "U3") (pin "129") (pinfunction "P1_3_129") (pintype "bidirectional"))
    )
    (net (code "170") (name "P1_04") (class "Default")
      (node (ref "J8") (pin "P$11") (pinfunction "P$11_P$11") (pintype "bidirectional"))
      (node (ref "U3") (pin "128") (pinfunction "P1_4_128") (pintype "bidirectional"))
    )
    (net (code "171") (name "P1_05") (class "Default")
      (node (ref "J8") (pin "P$13") (pinfunction "P$13_P$13") (pintype "bidirectional"))
      (node (ref "U3") (pin "127") (pinfunction "P1_5_127") (pintype "bidirectional"))
    )
    (net (code "172") (name "P1_06") (class "Default")
      (node (ref "J8") (pin "P$15") (pinfunction "P$15_P$15") (pintype "bidirectional"))
      (node (ref "U3") (pin "126") (pinfunction "P1_6_126") (pintype "bidirectional"))
    )
    (net (code "173") (name "P1_07") (class "Default")
      (node (ref "J8") (pin "P$17") (pinfunction "P$17_P$17") (pintype "bidirectional"))
      (node (ref "U3") (pin "125") (pinfunction "P1_7_125") (pintype "bidirectional"))
    )
    (net (code "174") (name "P4_00") (class "Default")
      (node (ref "J4") (pin "P$7") (pinfunction "P$7_P$7") (pintype "bidirectional"))
      (node (ref "U3") (pin "1") (pinfunction "P4_0_1") (pintype "bidirectional"))
    )
    (net (code "175") (name "P4_01") (class "Default")
      (node (ref "J4") (pin "P$8") (pinfunction "P$8_P$8") (pintype "bidirectional"))
      (node (ref "U3") (pin "2") (pinfunction "P4_1_2") (pintype "bidirectional"))
    )
    (net (code "176") (name "P4_02") (class "Default")
      (node (ref "J4") (pin "P$9") (pinfunction "P$9_P$9") (pintype "bidirectional"))
      (node (ref "U3") (pin "3") (pinfunction "P4_2_3") (pintype "bidirectional"))
    )
    (net (code "177") (name "P4_08") (class "Default")
      (node (ref "J4") (pin "P$20") (pinfunction "P$20_P$20") (pintype "bidirectional"))
      (node (ref "U3") (pin "43") (pinfunction "P4_8_43") (pintype "bidirectional"))
    )
    (net (code "178") (name "P4_09") (class "Default")
      (node (ref "J4") (pin "P$19") (pinfunction "P$19_P$19") (pintype "bidirectional"))
      (node (ref "U3") (pin "42") (pinfunction "P4_9_42") (pintype "bidirectional"))
    )
    (net (code "179") (name "P4_10") (class "Default")
      (node (ref "J4") (pin "P$18") (pinfunction "P$18_P$18") (pintype "bidirectional"))
      (node (ref "U3") (pin "41") (pinfunction "P4_10_41") (pintype "bidirectional"))
    )
    (net (code "180") (name "P4_11") (class "Default")
      (node (ref "J4") (pin "P$17") (pinfunction "P$17_P$17") (pintype "bidirectional"))
      (node (ref "U3") (pin "40") (pinfunction "P4_11_40") (pintype "bidirectional"))
    )
    (net (code "181") (name "P4_12") (class "Default")
      (node (ref "J4") (pin "P$16") (pinfunction "P$16_P$16") (pintype "bidirectional"))
      (node (ref "U3") (pin "39") (pinfunction "P4_12_39") (pintype "bidirectional"))
    )
    (net (code "182") (name "P4_13") (class "Default")
      (node (ref "J4") (pin "P$15") (pinfunction "P$15_P$15") (pintype "bidirectional"))
      (node (ref "U3") (pin "38") (pinfunction "P4_13_38") (pintype "bidirectional"))
    )
    (net (code "183") (name "P4_14") (class "Default")
      (node (ref "J4") (pin "P$14") (pinfunction "P$14_P$14") (pintype "bidirectional"))
      (node (ref "U3") (pin "37") (pinfunction "P4_14_37") (pintype "bidirectional"))
    )
    (net (code "184") (name "P4_15") (class "Default")
      (node (ref "J4") (pin "P$13") (pinfunction "P$13_P$13") (pintype "bidirectional"))
      (node (ref "U3") (pin "36") (pinfunction "P4_15_36") (pintype "bidirectional"))
    )
    (net (code "185") (name "P5_11") (class "Default")
      (node (ref "J4") (pin "P$6") (pinfunction "P$6_P$6") (pintype "bidirectional"))
      (node (ref "U3") (pin "176") (pinfunction "P5_11_176") (pintype "bidirectional"))
    )
    (net (code "186") (name "P5_12") (class "Default")
      (node (ref "J4") (pin "P$5") (pinfunction "P$5_P$5") (pintype "bidirectional"))
      (node (ref "U3") (pin "175") (pinfunction "P5_12_175") (pintype "bidirectional"))
    )
    (net (code "187") (name "P5_13") (class "Default")
      (node (ref "J4") (pin "P$4") (pinfunction "P$4_P$4") (pintype "bidirectional"))
      (node (ref "U3") (pin "174") (pinfunction "P5_13_174") (pintype "bidirectional"))
    )
    (net (code "188") (name "P6_00") (class "Default")
      (node (ref "J8") (pin "P$19") (pinfunction "P$19_P$19") (pintype "bidirectional"))
      (node (ref "U3") (pin "122") (pinfunction "P6_0_122") (pintype "bidirectional"))
    )
    (net (code "189") (name "P7_06") (class "Default")
      (node (ref "J4") (pin "P$10") (pinfunction "P$10_P$10") (pintype "bidirectional"))
      (node (ref "U3") (pin "14") (pinfunction "P7_6_14") (pintype "bidirectional"))
    )
    (net (code "190") (name "P7_07") (class "Default")
      (node (ref "J4") (pin "P$11") (pinfunction "P$11_P$11") (pintype "bidirectional"))
      (node (ref "U3") (pin "15") (pinfunction "P7_7_15") (pintype "bidirectional"))
    )
    (net (code "191") (name "P8_00") (class "Default")
      (node (ref "J8") (pin "P$5") (pinfunction "P$5_P$5") (pintype "bidirectional"))
      (node (ref "U3") (pin "133") (pinfunction "P8_0_133") (pintype "bidirectional"))
    )
    (net (code "192") (name "P8_01") (class "Default")
      (node (ref "J8") (pin "P$3") (pinfunction "P$3_P$3") (pintype "bidirectional"))
      (node (ref "U3") (pin "134") (pinfunction "P8_1_134") (pintype "bidirectional"))
    )
    (net (code "193") (name "P8_02") (class "Default")
      (node (ref "J8") (pin "P$4") (pinfunction "P$4_P$4") (pintype "bidirectional"))
      (node (ref "U3") (pin "135") (pinfunction "P8_2_135") (pintype "bidirectional"))
    )
    (net (code "194") (name "P8_03") (class "Default")
      (node (ref "J8") (pin "P$1") (pinfunction "P$1_P$1") (pintype "bidirectional"))
      (node (ref "U3") (pin "136") (pinfunction "P8_3_136") (pintype "bidirectional"))
    )
    (net (code "195") (name "P8_04") (class "Default")
      (node (ref "J8") (pin "P$2") (pinfunction "P$2_P$2") (pintype "bidirectional"))
      (node (ref "U3") (pin "137") (pinfunction "P8_4_137") (pintype "bidirectional"))
    )
    (net (code "196") (name "P8_05") (class "Default")
      (node (ref "J4") (pin "P$3") (pinfunction "P$3_P$3") (pintype "bidirectional"))
      (node (ref "U3") (pin "173") (pinfunction "P8_5_173") (pintype "bidirectional"))
    )
    (net (code "197") (name "PB_00") (class "Default")
      (node (ref "J4") (pin "P$12") (pinfunction "P$12_P$12") (pintype "bidirectional"))
      (node (ref "U3") (pin "16") (pinfunction "PB_0_16") (pintype "bidirectional"))
    )
    (net (code "198") (name "R51") (class "Default")
      (node (ref "R7") (pin "P$1") (pinfunction "1_P$1") (pintype "passive"))
      (node (ref "RJ1") (pin "12") (pinfunction "YHI_12") (pintype "bidirectional"))
    )
    (net (code "199") (name "R52") (class "Default")
      (node (ref "R8") (pin "P$1") (pinfunction "1_P$1") (pintype "passive"))
      (node (ref "RJ1") (pin "9") (pinfunction "GHI_9") (pintype "bidirectional"))
    )
    (net (code "200") (name "RELAY_1") (class "Default")
      (node (ref "R29") (pin "P$1") (pinfunction "1_P$1") (pintype "passive"))
      (node (ref "U3") (pin "56") (pinfunction "P3_14_56") (pintype "bidirectional"))
    )
    (net (code "201") (name "RELAY_2") (class "Default")
      (node (ref "R30") (pin "P$1") (pinfunction "1_P$1") (pintype "passive"))
      (node (ref "U3") (pin "55") (pinfunction "P3_13_55") (pintype "bidirectional"))
    )
    (net (code "202") (name "RELAY_3") (class "Default")
      (node (ref "R49") (pin "P$1") (pinfunction "1_P$1") (pintype "passive"))
      (node (ref "U3") (pin "52") (pinfunction "P2_4_52") (pintype "bidirectional"))
    )
    (net (code "203") (name "RELAY_4") (class "Default")
      (node (ref "R50") (pin "P$1") (pinfunction "1_P$1") (pintype "passive"))
      (node (ref "U3") (pin "49") (pinfunction "P2_7_49") (pintype "bidirectional"))
    )
    (net (code "204") (name "RESET") (class "Default")
      (node (ref "C16") (pin "P$1") (pinfunction "1_P$1") (pintype "passive"))
      (node (ref "J3") (pin "9") (pinfunction "9_9") (pintype "passive"))
      (node (ref "R13") (pin "P$1") (pinfunction "1_P$1") (pintype "passive"))
      (node (ref "U3") (pin "67") (pinfunction "RES#_67") (pintype "bidirectional"))
    )
    (net (code "205") (name "REXT") (class "Default")
      (node (ref "C3") (pin "P$1") (pinfunction "1_P$1") (pintype "passive"))
      (node (ref "R1") (pin "P$2") (pinfunction "2_P$2") (pintype "passive"))
      (node (ref "U1") (pin "9") (pinfunction "REXT_9") (pintype "input"))
    )
    (net (code "206") (name "RO_NEG_1") (class "Default")
      (node (ref "J15") (pin "P$2") (pinfunction "P$2_P$2") (pintype "bidirectional"))
      (node (ref "U$1") (pin "P$3") (pinfunction "VO-_P$3") (pintype "bidirectional"))
    )
    (net (code "207") (name "RO_NEG_2") (class "Default")
      (node (ref "J16") (pin "P$2") (pinfunction "P$2_P$2") (pintype "bidirectional"))
      (node (ref "U$2") (pin "P$3") (pinfunction "VO-_P$3") (pintype "bidirectional"))
    )
    (net (code "208") (name "RO_NEG_3") (class "Default")
      (node (ref "J23") (pin "P$2") (pinfunction "P$2_P$2") (pintype "bidirectional"))
      (node (ref "U$7") (pin "P$3") (pinfunction "VO-_P$3") (pintype "bidirectional"))
    )
    (net (code "209") (name "RO_NEG_4") (class "Default")
      (node (ref "J24") (pin "P$2") (pinfunction "P$2_P$2") (pintype "bidirectional"))
      (node (ref "U$8") (pin "P$3") (pinfunction "VO-_P$3") (pintype "bidirectional"))
    )
    (net (code "210") (name "RO_POS_1") (class "Default")
      (node (ref "J15") (pin "P$1") (pinfunction "P$1_P$1") (pintype "bidirectional"))
      (node (ref "U$1") (pin "P$4") (pinfunction "VO+_P$4") (pintype "bidirectional"))
    )
    (net (code "211") (name "RO_POS_2") (class "Default")
      (node (ref "J16") (pin "P$1") (pinfunction "P$1_P$1") (pintype "bidirectional"))
      (node (ref "U$2") (pin "P$4") (pinfunction "VO+_P$4") (pintype "bidirectional"))
    )
    (net (code "212") (name "RO_POS_3") (class "Default")
      (node (ref "J23") (pin "P$1") (pinfunction "P$1_P$1") (pintype "bidirectional"))
      (node (ref "U$7") (pin "P$4") (pinfunction "VO+_P$4") (pintype "bidirectional"))
    )
    (net (code "213") (name "RO_POS_4") (class "Default")
      (node (ref "J24") (pin "P$1") (pinfunction "P$1_P$1") (pintype "bidirectional"))
      (node (ref "U$8") (pin "P$4") (pinfunction "VO+_P$4") (pintype "bidirectional"))
    )
    (net (code "214") (name "RXD0") (class "Default")
      (node (ref "R10") (pin "P$2") (pinfunction "2_P$2") (pintype "passive"))
      (node (ref "U1") (pin "13") (pinfunction "RXD0_13") (pintype "bidirectional"))
    )
    (net (code "215") (name "RXD1") (class "Default")
      (node (ref "R9") (pin "P$2") (pinfunction "2_P$2") (pintype "passive"))
      (node (ref "U1") (pin "12") (pinfunction "RXD1_12") (pintype "bidirectional"))
    )
    (net (code "216") (name "RXER") (class "Default")
      (node (ref "R11") (pin "P$2") (pinfunction "2_P$2") (pintype "passive"))
      (node (ref "U1") (pin "17") (pinfunction "RXER_17") (pintype "bidirectional"))
    )
    (net (code "217") (name "RXM") (class "Default")
      (node (ref "RJ1") (pin "6") (pinfunction "RD-_6") (pintype "bidirectional"))
      (node (ref "U1") (pin "3") (pinfunction "RXM_3") (pintype "bidirectional"))
    )
    (net (code "218") (name "RXP") (class "Default")
      (node (ref "RJ1") (pin "3") (pinfunction "RD+_3") (pintype "bidirectional"))
      (node (ref "U1") (pin "4") (pinfunction "RXP_4") (pintype "bidirectional"))
    )
    (net (code "219") (name "SD1_CD") (class "Default")
      (node (ref "J1") (pin "10") (pinfunction "CD_SWITCH2_10") (pintype "bidirectional"))
      (node (ref "U3") (pin "146") (pinfunction "P5_6/AN019_146") (pintype "bidirectional"))
    )
    (net (code "220") (name "SD1_CLK") (class "Default")
      (node (ref "J1") (pin "5") (pinfunction "CLOCK_5") (pintype "bidirectional"))
      (node (ref "U3") (pin "140") (pinfunction "P5_0/AN016_140") (pintype "bidirectional"))
    )
    (net (code "221") (name "SD1_CMD") (class "Default")
      (node (ref "J1") (pin "3") (pinfunction "COMMAND/RESPONSE_3") (pintype "bidirectional"))
      (node (ref "U3") (pin "141") (pinfunction "P5_1/AN116_141") (pintype "bidirectional"))
    )
    (net (code "222") (name "SD1_DAT0") (class "Default")
      (node (ref "J1") (pin "7") (pinfunction "DATA_LINE[BIT_0]_7") (pintype "bidirectional"))
      (node (ref "U3") (pin "142") (pinfunction "P5_2/AN017_142") (pintype "bidirectional"))
    )
    (net (code "223") (name "SD1_DAT1") (class "Default")
      (node (ref "J1") (pin "8") (pinfunction "DATA_LINE[BIT_1]_8") (pintype "bidirectional"))
      (node (ref "U3") (pin "143") (pinfunction "P5_3/AN117_143") (pintype "bidirectional"))
    )
    (net (code "224") (name "SD1_DAT2") (class "Default")
      (node (ref "J1") (pin "1") (pinfunction "DATA_LINE[BIT_2]_1") (pintype "bidirectional"))
      (node (ref "U3") (pin "144") (pinfunction "P5_4/AN018_144") (pintype "bidirectional"))
    )
    (net (code "225") (name "SD1_DAT3") (class "Default")
      (node (ref "J1") (pin "2") (pinfunction "CARD_DETECT/DATA_LINE[BIT_3]_2") (pintype "bidirectional"))
      (node (ref "U3") (pin "145") (pinfunction "P5_5/AN118_145") (pintype "bidirectional"))
    )
    (net (code "226") (name "SD1_WP") (class "Default")
      (node (ref "J1") (pin "9") (pinfunction "CD_SWITCH1_9") (pintype "bidirectional"))
      (node (ref "U3") (pin "147") (pinfunction "P5_7/AN119_147") (pintype "bidirectional"))
    )
    (net (code "227") (name "TCK") (class "Default")
      (node (ref "J3") (pin "7") (pinfunction "7_7") (pintype "passive"))
      (node (ref "U3") (pin "88") (pinfunction "P3_0_88") (pintype "bidirectional"))
    )
    (net (code "228") (name "TDI") (class "Default")
      (node (ref "J3") (pin "1") (pinfunction "1_1") (pintype "passive"))
      (node (ref "U3") (pin "91") (pinfunction "P1_10_91") (pintype "bidirectional"))
    )
    (net (code "229") (name "TDO") (class "Default")
      (node (ref "J3") (pin "3") (pinfunction "3_3") (pintype "passive"))
      (node (ref "U3") (pin "90") (pinfunction "P1_9_90") (pintype "bidirectional"))
    )
    (net (code "230") (name "TMS") (class "Default")
      (node (ref "J3") (pin "5") (pinfunction "5_5") (pintype "passive"))
      (node (ref "U3") (pin "89") (pinfunction "P1_8_89") (pintype "bidirectional"))
    )
    (net (code "231") (name "TXM") (class "Default")
      (node (ref "RJ1") (pin "2") (pinfunction "TD-_2") (pintype "bidirectional"))
      (node (ref "U1") (pin "5") (pinfunction "TXM_5") (pintype "bidirectional"))
    )
    (net (code "232") (name "TXP") (class "Default")
      (node (ref "RJ1") (pin "1") (pinfunction "TD+_1") (pintype "bidirectional"))
      (node (ref "U1") (pin "6") (pinfunction "TXP_6") (pintype "bidirectional"))
    )
    (net (code "233") (name "USBHS_FAULT") (class "Default")
      (node (ref "R19") (pin "P$1") (pinfunction "1_P$1") (pintype "passive"))
      (node (ref "U2") (pin "3") (pinfunction "FLG_3") (pintype "input"))
      (node (ref "U3") (pin "78") (pinfunction "P3_8_78") (pintype "bidirectional"))
    )
    (net (code "234") (name "USBHS_N") (class "Default")
      (node (ref "J6") (pin "D-") (pinfunction "D-_D-") (pintype "bidirectional"))
      (node (ref "U3") (pin "31") (pinfunction "USBHS_DM_31") (pintype "bidirectional"))
    )
    (net (code "235") (name "USBHS_P") (class "Default")
      (node (ref "J6") (pin "D+") (pinfunction "D+_D+") (pintype "bidirectional"))
      (node (ref "U3") (pin "32") (pinfunction "USBHS_DP_32") (pintype "bidirectional"))
    )
    (net (code "236") (name "USBHS_VBUS") (class "Default")
      (node (ref "C29") (pin "P$1") (pinfunction "1_P$1") (pintype "passive"))
      (node (ref "C31") (pin "1") (pinfunction "1_1") (pintype "passive"))
      (node (ref "J6") (pin "VBUS") (pinfunction "VBUS_VBUS") (pintype "power_in"))
      (node (ref "U2") (pin "5") (pinfunction "OUT_5") (pintype "input"))
      (node (ref "U3") (pin "17") (pinfunction "PB_1_17") (pintype "bidirectional"))
    )
    (net (code "237") (name "USBHS_VBUSEN") (class "Default")
      (node (ref "R20") (pin "P$1") (pinfunction "1_P$1") (pintype "passive"))
      (node (ref "U2") (pin "1") (pinfunction "EN_1") (pintype "input"))
    )
    (net (code "238") (name "USB_N") (class "Default")
      (node (ref "R17") (pin "P$1") (pinfunction "1_P$1") (pintype "passive"))
      (node (ref "U3") (pin "46") (pinfunction "USB_DM_46") (pintype "bidirectional"))
    )
    (net (code "239") (name "USB_P") (class "Default")
      (node (ref "R18") (pin "P$1") (pinfunction "1_P$1") (pintype "passive"))
      (node (ref "U3") (pin "47") (pinfunction "USB_DP_47") (pintype "bidirectional"))
    )
    (net (code "240") (name "USB_VBUS_B") (class "Default")
      (node (ref "R16") (pin "P$1") (pinfunction "1_P$1") (pintype "passive"))
      (node (ref "U3") (pin "44") (pinfunction "P4_7_44") (pintype "bidirectional"))
    )
    (net (code "241") (name "VCL_F(FLASH)") (class "Default")
      (node (ref "C34") (pin "P$2") (pinfunction "2_P$2") (pintype "passive"))
      (node (ref "U3") (pin "112") (pinfunction "VCL_F(FLASH)_112") (pintype "bidirectional"))
    )
    (net (code "242") (name "VDD") (class "Default")
      (node (ref "C14") (pin "P$1") (pinfunction "1_P$1") (pintype "passive"))
      (node (ref "C15") (pin "P$1") (pinfunction "1_P$1") (pintype "passive"))
      (node (ref "C19") (pin "P$2") (pinfunction "2_P$2") (pintype "passive"))
      (node (ref "C20") (pin "P$2") (pinfunction "2_P$2") (pintype "passive"))
      (node (ref "C21") (pin "P$2") (pinfunction "2_P$2") (pintype "passive"))
      (node (ref "C22") (pin "P$2") (pinfunction "2_P$2") (pintype "passive"))
      (node (ref "C25") (pin "P$2") (pinfunction "2_P$2") (pintype "passive"))
      (node (ref "C27") (pin "P$2") (pinfunction "2_P$2") (pintype "passive"))
      (node (ref "C30") (pin "P$2") (pinfunction "2_P$2") (pintype "passive"))
      (node (ref "C35") (pin "P$2") (pinfunction "2_P$2") (pintype "passive"))
      (node (ref "C36") (pin "P$1") (pinfunction "1_P$1") (pintype "passive"))
      (node (ref "C38") (pin "P$2") (pinfunction "2_P$2") (pintype "passive"))
      (node (ref "C39") (pin "P$1") (pinfunction "1_P$1") (pintype "passive"))
      (node (ref "C4") (pin "P$1") (pinfunction "1_P$1") (pintype "passive"))
      (node (ref "C40") (pin "P$1") (pinfunction "1_P$1") (pintype "passive"))
      (node (ref "C41") (pin "P$1") (pinfunction "1_P$1") (pintype "passive"))
      (node (ref "C43") (pin "P$2") (pinfunction "2_P$2") (pintype "passive"))
      (node (ref "C5") (pin "P$1") (pinfunction "1_P$1") (pintype "passive"))
      (node (ref "C7") (pin "P$1") (pinfunction "1_P$1") (pintype "passive"))
      (node (ref "FB1") (pin "1") (pinfunction "P$1_1") (pintype "bidirectional"))
      (node (ref "J1") (pin "4") (pinfunction "SUPPLY_VOLTAGE_4") (pintype "power_in"))
      (node (ref "J3") (pin "2") (pinfunction "2_2") (pintype "passive"))
      (node (ref "J3") (pin "4") (pinfunction "4_4") (pintype "passive"))
      (node (ref "L1") (pin "2") (pinfunction "P$2_2") (pintype "bidirectional"))
      (node (ref "R102") (pin "P$2") (pinfunction "2_P$2") (pintype "passive"))
      (node (ref "R103") (pin "P$2") (pinfunction "2_P$2") (pintype "passive"))
      (node (ref "R104") (pin "P$2") (pinfunction "2_P$2") (pintype "passive"))
      (node (ref "R105") (pin "P$2") (pinfunction "2_P$2") (pintype "passive"))
      (node (ref "R106") (pin "P$2") (pinfunction "2_P$2") (pintype "passive"))
      (node (ref "R107") (pin "P$2") (pinfunction "2_P$2") (pintype "passive"))
      (node (ref "R108") (pin "P$2") (pinfunction "2_P$2") (pintype "passive"))
      (node (ref "R13") (pin "P$2") (pinfunction "2_P$2") (pintype "passive"))
      (node (ref "R14") (pin "P$1") (pinfunction "1_P$1") (pintype "passive"))
      (node (ref "R15") (pin "P$1") (pinfunction "1_P$1") (pintype "passive"))
      (node (ref "R2") (pin "P$2") (pinfunction "2_P$2") (pintype "passive"))
      (node (ref "R25") (pin "P$2") (pinfunction "2_P$2") (pintype "passive"))
      (node (ref "R26") (pin "P$2") (pinfunction "2_P$2") (pintype "passive"))
      (node (ref "R27") (pin "P$2") (pinfunction "2_P$2") (pintype "passive"))
      (node (ref "R3") (pin "P$2") (pinfunction "2_P$2") (pintype "passive"))
      (node (ref "R4") (pin "P$2") (pinfunction "2_P$2") (pintype "passive"))
      (node (ref "R5") (pin "P$2") (pinfunction "2_P$2") (pintype "passive"))
      (node (ref "R6") (pin "P$2") (pinfunction "2_P$2") (pintype "passive"))
      (node (ref "R7") (pin "P$2") (pinfunction "2_P$2") (pintype "passive"))
      (node (ref "R8") (pin "P$2") (pinfunction "2_P$2") (pintype "passive"))
      (node (ref "U1") (pin "14") (pinfunction "VDDIO_14") (pintype "power_in"))
      (node (ref "U18") (pin "3") (pinfunction "C(3)_3") (pintype "input"))
      (node (ref "U19") (pin "3") (pinfunction "C(3)_3") (pintype "input"))
      (node (ref "U20") (pin "3") (pinfunction "C(3)_3") (pintype "input"))
      (node (ref "U21") (pin "3") (pinfunction "C(3)_3") (pintype "input"))
      (node (ref "U28") (pin "3") (pinfunction "C(3)_3") (pintype "input"))
      (node (ref "U29") (pin "3") (pinfunction "C(3)_3") (pintype "input"))
      (node (ref "U3") (pin "110") (pinfunction "VCC(IO)5_110") (pintype "bidirectional"))
      (node (ref "U3") (pin "123") (pinfunction "VCC(IO)6_123") (pintype "bidirectional"))
      (node (ref "U3") (pin "138") (pinfunction "VCC(IO)7_138") (pintype "bidirectional"))
      (node (ref "U3") (pin "149") (pinfunction "VCC(IO)8_149") (pintype "bidirectional"))
      (node (ref "U3") (pin "154") (pinfunction "VREFH_154") (pintype "bidirectional"))
      (node (ref "U3") (pin "155") (pinfunction "AVCC0_155") (pintype "bidirectional"))
      (node (ref "U3") (pin "158") (pinfunction "VREFH0_158") (pintype "bidirectional"))
      (node (ref "U3") (pin "171") (pinfunction "VCC(IO)9_171") (pintype "bidirectional"))
      (node (ref "U3") (pin "25") (pinfunction "VCC1_25") (pintype "bidirectional"))
      (node (ref "U3") (pin "26") (pinfunction "AVCC_SUBHS_26") (pintype "bidirectional"))
      (node (ref "U3") (pin "34") (pinfunction "VCC_USBHS_34") (pintype "bidirectional"))
      (node (ref "U3") (pin "48") (pinfunction "VCC_USB_48") (pintype "bidirectional"))
      (node (ref "U3") (pin "61") (pinfunction "VCC(IO)2_61") (pintype "bidirectional"))
      (node (ref "U3") (pin "84") (pinfunction "VCC(IO)3_84") (pintype "bidirectional"))
      (node (ref "U3") (pin "97") (pinfunction "VCC(IO)4_97") (pintype "bidirectional"))
      (node (ref "U30") (pin "3") (pinfunction "C(3)_3") (pintype "input"))
      (node (ref "U5") (pin "3") (pinfunction "C(3)_3") (pintype "input"))
      (node (ref "U8") (pin "3") (pinfunction "C(3)_3") (pintype "input"))
      (node (ref "U9") (pin "3") (pinfunction "C(3)_3") (pintype "input"))
    )
    (net (code "243") (name "VDD5") (class "Default")
      (node (ref "C23") (pin "P$1") (pinfunction "1_P$1") (pintype "passive"))
      (node (ref "C26") (pin "P$1") (pinfunction "1_P$1") (pintype "passive"))
      (node (ref "J2") (pin "P$3") (pinfunction "P$3_P$3") (pintype "bidirectional"))
      (node (ref "R19") (pin "P$2") (pinfunction "2_P$2") (pintype "passive"))
      (node (ref "R20") (pin "P$2") (pinfunction "2_P$2") (pintype "passive"))
      (node (ref "R31") (pin "P$2") (pinfunction "2_P$2") (pintype "passive"))
      (node (ref "R32") (pin "P$2") (pinfunction "2_P$2") (pintype "passive"))
      (node (ref "R51") (pin "P$2") (pinfunction "2_P$2") (pintype "passive"))
      (node (ref "R52") (pin "P$2") (pinfunction "2_P$2") (pintype "passive"))
      (node (ref "U$1") (pin "P$2") (pinfunction "VC+_P$2") (pintype "bidirectional"))
      (node (ref "U$2") (pin "P$2") (pinfunction "VC+_P$2") (pintype "bidirectional"))
      (node (ref "U$7") (pin "P$2") (pinfunction "VC+_P$2") (pintype "bidirectional"))
      (node (ref "U$8") (pin "P$2") (pinfunction "VC+_P$2") (pintype "bidirectional"))
      (node (ref "U2") (pin "4") (pinfunction "VIN_4") (pintype "input"))
    )
    (net (code "244") (name "VDD12") (class "Default")
      (node (ref "J10") (pin "3") (pinfunction "3_3") (pintype "passive"))
      (node (ref "J11") (pin "3") (pinfunction "3_3") (pintype "passive"))
      (node (ref "J12") (pin "3") (pinfunction "3_3") (pintype "passive"))
      (node (ref "J13") (pin "1") (pinfunction "1-HLFB+_1") (pintype "passive"))
      (node (ref "J13") (pin "2") (pinfunction "2-INPUT_B+_2") (pintype "passive"))
      (node (ref "J13") (pin "3") (pinfunction "3-INPUT_A+_3") (pintype "passive"))
      (node (ref "J13") (pin "4") (pinfunction "4-ENABLE+_4") (pintype "passive"))
      (node (ref "J14") (pin "1") (pinfunction "1-HLFB+_1") (pintype "passive"))
      (node (ref "J14") (pin "2") (pinfunction "2-INPUT_B+_2") (pintype "passive"))
      (node (ref "J14") (pin "3") (pinfunction "3-INPUT_A+_3") (pintype "passive"))
      (node (ref "J14") (pin "4") (pinfunction "4-ENABLE+_4") (pintype "passive"))
      (node (ref "J17") (pin "1") (pinfunction "1-HLFB+_1") (pintype "passive"))
      (node (ref "J17") (pin "2") (pinfunction "2-INPUT_B+_2") (pintype "passive"))
      (node (ref "J17") (pin "3") (pinfunction "3-INPUT_A+_3") (pintype "passive"))
      (node (ref "J17") (pin "4") (pinfunction "4-ENABLE+_4") (pintype "passive"))
      (node (ref "J18") (pin "1") (pinfunction "1-HLFB+_1") (pintype "passive"))
      (node (ref "J18") (pin "2") (pinfunction "2-INPUT_B+_2") (pintype "passive"))
      (node (ref "J18") (pin "3") (pinfunction "3-INPUT_A+_3") (pintype "passive"))
      (node (ref "J18") (pin "4") (pinfunction "4-ENABLE+_4") (pintype "passive"))
      (node (ref "J19") (pin "3") (pinfunction "3_3") (pintype "passive"))
      (node (ref "J20") (pin "3") (pinfunction "3_3") (pintype "passive"))
      (node (ref "J21") (pin "1") (pinfunction "1-HLFB+_1") (pintype "passive"))
      (node (ref "J21") (pin "2") (pinfunction "2-INPUT_B+_2") (pintype "passive"))
      (node (ref "J21") (pin "3") (pinfunction "3-INPUT_A+_3") (pintype "passive"))
      (node (ref "J21") (pin "4") (pinfunction "4-ENABLE+_4") (pintype "passive"))
      (node (ref "J22") (pin "1") (pinfunction "1-HLFB+_1") (pintype "passive"))
      (node (ref "J22") (pin "2") (pinfunction "2-INPUT_B+_2") (pintype "passive"))
      (node (ref "J22") (pin "3") (pinfunction "3-INPUT_A+_3") (pintype "passive"))
      (node (ref "J22") (pin "4") (pinfunction "4-ENABLE+_4") (pintype "passive"))
      (node (ref "J25") (pin "1") (pinfunction "1-HLFB+_1") (pintype "passive"))
      (node (ref "J25") (pin "2") (pinfunction "2-INPUT_B+_2") (pintype "passive"))
      (node (ref "J25") (pin "3") (pinfunction "3-INPUT_A+_3") (pintype "passive"))
      (node (ref "J25") (pin "4") (pinfunction "4-ENABLE+_4") (pintype "passive"))
      (node (ref "J26") (pin "1") (pinfunction "1-HLFB+_1") (pintype "passive"))
      (node (ref "J26") (pin "2") (pinfunction "2-INPUT_B+_2") (pintype "passive"))
      (node (ref "J26") (pin "3") (pinfunction "3-INPUT_A+_3") (pintype "passive"))
      (node (ref "J26") (pin "4") (pinfunction "4-ENABLE+_4") (pintype "passive"))
      (node (ref "J27") (pin "3") (pinfunction "3_3") (pintype "passive"))
      (node (ref "J28") (pin "3") (pinfunction "3_3") (pintype "passive"))
      (node (ref "J29") (pin "1") (pinfunction "1-HLFB+_1") (pintype "passive"))
      (node (ref "J29") (pin "2") (pinfunction "2-INPUT_B+_2") (pintype "passive"))
      (node (ref "J29") (pin "3") (pinfunction "3-INPUT_A+_3") (pintype "passive"))
      (node (ref "J29") (pin "4") (pinfunction "4-ENABLE+_4") (pintype "passive"))
      (node (ref "J30") (pin "1") (pinfunction "1-HLFB+_1") (pintype "passive"))
      (node (ref "J30") (pin "2") (pinfunction "2-INPUT_B+_2") (pintype "passive"))
      (node (ref "J30") (pin "3") (pinfunction "3-INPUT_A+_3") (pintype "passive"))
      (node (ref "J30") (pin "4") (pinfunction "4-ENABLE+_4") (pintype "passive"))
      (node (ref "J31") (pin "3") (pinfunction "3_3") (pintype "passive"))
      (node (ref "J32") (pin "3") (pinfunction "3_3") (pintype "passive"))
      (node (ref "J33") (pin "1") (pinfunction "1-HLFB+_1") (pintype "passive"))
      (node (ref "J33") (pin "2") (pinfunction "2-INPUT_B+_2") (pintype "passive"))
      (node (ref "J33") (pin "3") (pinfunction "3-INPUT_A+_3") (pintype "passive"))
      (node (ref "J33") (pin "4") (pinfunction "4-ENABLE+_4") (pintype "passive"))
      (node (ref "J34") (pin "1") (pinfunction "1-HLFB+_1") (pintype "passive"))
      (node (ref "J34") (pin "2") (pinfunction "2-INPUT_B+_2") (pintype "passive"))
      (node (ref "J34") (pin "3") (pinfunction "3-INPUT_A+_3") (pintype "passive"))
      (node (ref "J34") (pin "4") (pinfunction "4-ENABLE+_4") (pintype "passive"))
      (node (ref "J5") (pin "3") (pinfunction "3_3") (pintype "passive"))
      (node (ref "J9") (pin "P$1") (pinfunction "P$1_P$1") (pintype "bidirectional"))
      (node (ref "J9") (pin "P$2") (pinfunction "P$2_P$2") (pintype "bidirectional"))
      (node (ref "R109") (pin "2") (pinfunction "2_2") (pintype "passive"))
      (node (ref "R113") (pin "2") (pinfunction "2_2") (pintype "passive"))
      (node (ref "R114") (pin "2") (pinfunction "2_2") (pintype "passive"))
      (node (ref "R115") (pin "2") (pinfunction "2_2") (pintype "passive"))
      (node (ref "R119") (pin "2") (pinfunction "2_2") (pintype "passive"))
      (node (ref "R120") (pin "2") (pinfunction "2_2") (pintype "passive"))
      (node (ref "R133") (pin "2") (pinfunction "2_2") (pintype "passive"))
      (node (ref "R137") (pin "2") (pinfunction "2_2") (pintype "passive"))
      (node (ref "R138") (pin "2") (pinfunction "2_2") (pintype "passive"))
      (node (ref "R139") (pin "2") (pinfunction "2_2") (pintype "passive"))
      (node (ref "R143") (pin "2") (pinfunction "2_2") (pintype "passive"))
      (node (ref "R144") (pin "2") (pinfunction "2_2") (pintype "passive"))
      (node (ref "R157") (pin "2") (pinfunction "2_2") (pintype "passive"))
      (node (ref "R161") (pin "2") (pinfunction "2_2") (pintype "passive"))
      (node (ref "R162") (pin "2") (pinfunction "2_2") (pintype "passive"))
      (node (ref "R163") (pin "2") (pinfunction "2_2") (pintype "passive"))
      (node (ref "R167") (pin "2") (pinfunction "2_2") (pintype "passive"))
      (node (ref "R168") (pin "2") (pinfunction "2_2") (pintype "passive"))
      (node (ref "R37") (pin "2") (pinfunction "2_2") (pintype "passive"))
      (node (ref "R41") (pin "2") (pinfunction "2_2") (pintype "passive"))
      (node (ref "R42") (pin "2") (pinfunction "2_2") (pintype "passive"))
      (node (ref "R43") (pin "2") (pinfunction "2_2") (pintype "passive"))
      (node (ref "R47") (pin "2") (pinfunction "2_2") (pintype "passive"))
      (node (ref "R48") (pin "2") (pinfunction "2_2") (pintype "passive"))
      (node (ref "R61") (pin "2") (pinfunction "2_2") (pintype "passive"))
      (node (ref "R65") (pin "2") (pinfunction "2_2") (pintype "passive"))
      (node (ref "R66") (pin "2") (pinfunction "2_2") (pintype "passive"))
      (node (ref "R67") (pin "2") (pinfunction "2_2") (pintype "passive"))
      (node (ref "R71") (pin "2") (pinfunction "2_2") (pintype "passive"))
      (node (ref "R72") (pin "2") (pinfunction "2_2") (pintype "passive"))
      (node (ref "R85") (pin "2") (pinfunction "2_2") (pintype "passive"))
      (node (ref "R89") (pin "2") (pinfunction "2_2") (pintype "passive"))
      (node (ref "R90") (pin "2") (pinfunction "2_2") (pintype "passive"))
      (node (ref "R91") (pin "2") (pinfunction "2_2") (pintype "passive"))
      (node (ref "R95") (pin "2") (pinfunction "2_2") (pintype "passive"))
      (node (ref "R96") (pin "2") (pinfunction "2_2") (pintype "passive"))
    )
    (net (code "245") (name "VDDIN") (class "Default")
      (node (ref "J2") (pin "P$2") (pinfunction "P$2_P$2") (pintype "bidirectional"))
      (node (ref "L1") (pin "1") (pinfunction "P$1_1") (pintype "bidirectional"))
    )
    (net (code "246") (name "VDD_1.2") (class "Default")
      (node (ref "C10") (pin "P$1") (pinfunction "1_P$1") (pintype "passive"))
      (node (ref "C11") (pin "P$1") (pinfunction "1_P$1") (pintype "passive"))
      (node (ref "U1") (pin "1") (pinfunction "VDD_1.2_1") (pintype "power_in"))
    )
    (net (code "247") (name "WF_A_DIR") (class "Default")
      (node (ref "R159") (pin "1") (pinfunction "1_1") (pintype "passive"))
      (node (ref "U3") (pin "99") (pinfunction "P6_8_99") (pintype "bidirectional"))
    )
    (net (code "248") (name "WF_A_ENABLE") (class "Default")
      (node (ref "R160") (pin "1") (pinfunction "1_1") (pintype "passive"))
      (node (ref "U3") (pin "96") (pinfunction "P1_15_96") (pintype "bidirectional"))
    )
    (net (code "249") (name "WF_A_HLFB_OUT") (class "Default")
      (node (ref "J33") (pin "5") (pinfunction "5-HLFB-_5") (pintype "passive"))
    )
    (net (code "250") (name "WF_A_MI_DIR") (class "Default")
      (node (ref "J33") (pin "7") (pinfunction "7-INPUT_A-_7") (pintype "passive"))
      (node (ref "R161") (pin "1") (pinfunction "1_1") (pintype "passive"))
      (node (ref "U71") (pin "3") (pinfunction "C(3)_3") (pintype "input"))
    )
    (net (code "251") (name "WF_A_MI_ENABLE") (class "Default")
      (node (ref "J33") (pin "8") (pinfunction "8-ENABLE-_8") (pintype "passive"))
      (node (ref "R162") (pin "1") (pinfunction "1_1") (pintype "passive"))
      (node (ref "U72") (pin "3") (pinfunction "C(3)_3") (pintype "input"))
    )
    (net (code "252") (name "WF_A_MI_STEP") (class "Default")
      (node (ref "J33") (pin "6") (pinfunction "6-INPUT_B-_6") (pintype "passive"))
      (node (ref "R157") (pin "1") (pinfunction "1_1") (pintype "passive"))
      (node (ref "U70") (pin "3") (pinfunction "C(3)_3") (pintype "input"))
    )
    (net (code "253") (name "WF_A_STEP") (class "Default")
      (node (ref "R158") (pin "1") (pinfunction "1_1") (pintype "passive"))
      (node (ref "U3") (pin "100") (pinfunction "P6_9_100") (pintype "bidirectional"))
    )
    (net (code "254") (name "WF_B_DIR") (class "Default")
      (node (ref "R165") (pin "1") (pinfunction "1_1") (pintype "passive"))
      (node (ref "U3") (pin "94") (pinfunction "P1_13_94") (pintype "bidirectional"))
    )
    (net (code "255") (name "WF_B_ENABLE") (class "Default")
      (node (ref "R166") (pin "1") (pinfunction "1_1") (pintype "passive"))
      (node (ref "U3") (pin "93") (pinfunction "P1_12_93") (pintype "bidirectional"))
    )
    (net (code "256") (name "WF_B_HLFB_OUT") (class "Default")
      (node (ref "J34") (pin "5") (pinfunction "5-HLFB-_5") (pintype "passive"))
    )
    (net (code "257") (name "WF_B_MI_ENABLE") (class "Default")
      (node (ref "J34") (pin "8") (pinfunction "8-ENABLE-_8") (pintype "passive"))
      (node (ref "R168") (pin "1") (pinfunction "1_1") (pintype "passive"))
      (node (ref "U75") (pin "3") (pinfunction "C(3)_3") (pintype "input"))
    )
    (net (code "258") (name "WF_B_MI_STEP") (class "Default")
      (node (ref "J34") (pin "6") (pinfunction "6-INPUT_B-_6") (pintype "passive"))
      (node (ref "R163") (pin "1") (pinfunction "1_1") (pintype "passive"))
      (node (ref "U73") (pin "3") (pinfunction "C(3)_3") (pintype "input"))
    )
    (net (code "259") (name "WF_B_STEP") (class "Default")
      (node (ref "R164") (pin "1") (pinfunction "1_1") (pintype "passive"))
      (node (ref "U3") (pin "95") (pinfunction "P1_14_95") (pintype "bidirectional"))
    )
    (net (code "260") (name "XCIN") (class "Default")
      (node (ref "C32") (pin "P$1") (pinfunction "1_P$1") (pintype "passive"))
      (node (ref "U3") (pin "20") (pinfunction "XCIN_20") (pintype "bidirectional"))
      (node (ref "X3") (pin "P$1") (pinfunction "P$1_P$1") (pintype "bidirectional"))
    )
    (net (code "261") (name "XCOUT") (class "Default")
      (node (ref "C37") (pin "P$1") (pinfunction "1_P$1") (pintype "passive"))
      (node (ref "U3") (pin "21") (pinfunction "XCOUT_21") (pintype "bidirectional"))
      (node (ref "X3") (pin "P$2") (pinfunction "P$2_P$2") (pintype "bidirectional"))
    )
    (net (code "262") (name "XII") (class "Default")
      (node (ref "C1") (pin "P$1") (pinfunction "1_P$1") (pintype "passive"))
      (node (ref "U1") (pin "8") (pinfunction "XI_8") (pintype "input"))
      (node (ref "X1") (pin "1") (pinfunction "1_1") (pintype "bidirectional"))
    )
    (net (code "263") (name "XOO") (class "Default")
      (node (ref "C2") (pin "P$1") (pinfunction "1_P$1") (pintype "passive"))
      (node (ref "U1") (pin "7") (pinfunction "XO_7") (pintype "output"))
      (node (ref "X1") (pin "3") (pinfunction "3_3") (pintype "bidirectional"))
    )
    (net (code "264") (name "XTAL1") (class "Default")
      (node (ref "C17") (pin "P$1") (pinfunction "1_P$1") (pintype "passive"))
      (node (ref "U3") (pin "23") (pinfunction "P2_13/XTAL_23") (pintype "bidirectional"))
      (node (ref "X2") (pin "1") (pinfunction "1_1") (pintype "bidirectional"))
    )
    (net (code "265") (name "XTAL2") (class "Default")
      (node (ref "C18") (pin "P$1") (pinfunction "1_P$1") (pintype "passive"))
      (node (ref "U3") (pin "24") (pinfunction "P2_12/EXTAL_24") (pintype "bidirectional"))
      (node (ref "X2") (pin "3") (pinfunction "3_3") (pintype "bidirectional"))
    )
    (net (code "266") (name "X_A_DIR") (class "Default")
      (node (ref "R39") (pin "1") (pinfunction "1_1") (pintype "passive"))
      (node (ref "U3") (pin "117") (pinfunction "P6_5_117") (pintype "bidirectional"))
    )
    (net (code "267") (name "X_A_ENABLE") (class "Default")
      (node (ref "R40") (pin "1") (pinfunction "1_1") (pintype "passive"))
      (node (ref "U3") (pin "116") (pinfunction "P6_6_116") (pintype "bidirectional"))
    )
    (net (code "268") (name "X_A_HLFB_OUT") (class "Default")
      (node (ref "J13") (pin "5") (pinfunction "5-HLFB-_5") (pintype "passive"))
    )
    (net (code "269") (name "X_A_MI_DIR") (class "Default")
      (node (ref "J13") (pin "7") (pinfunction "7-INPUT_A-_7") (pintype "passive"))
      (node (ref "R41") (pin "1") (pinfunction "1_1") (pintype "passive"))
      (node (ref "U11") (pin "3") (pinfunction "C(3)_3") (pintype "input"))
    )
    (net (code "270") (name "X_A_MI_ENABLE") (class "Default")
      (node (ref "J13") (pin "8") (pinfunction "8-ENABLE-_8") (pintype "passive"))
      (node (ref "R42") (pin "1") (pinfunction "1_1") (pintype "passive"))
      (node (ref "U12") (pin "3") (pinfunction "C(3)_3") (pintype "input"))
    )
    (net (code "271") (name "X_A_MI_STEP") (class "Default")
      (node (ref "J13") (pin "6") (pinfunction "6-INPUT_B-_6") (pintype "passive"))
      (node (ref "R37") (pin "1") (pinfunction "1_1") (pintype "passive"))
      (node (ref "U10") (pin "3") (pinfunction "C(3)_3") (pintype "input"))
    )
    (net (code "272") (name "X_A_STEP") (class "Default")
      (node (ref "R38") (pin "1") (pinfunction "1_1") (pintype "passive"))
      (node (ref "U3") (pin "118") (pinfunction "P6_4_118") (pintype "bidirectional"))
    )
    (net (code "273") (name "X_B_DIR") (class "Default")
      (node (ref "R45") (pin "1") (pinfunction "1_1") (pintype "passive"))
      (node (ref "U3") (pin "120") (pinfunction "P6_2_120") (pintype "bidirectional"))
    )
    (net (code "274") (name "X_B_ENABLE") (class "Default")
      (node (ref "R46") (pin "1") (pinfunction "1_1") (pintype "passive"))
      (node (ref "U3") (pin "119") (pinfunction "P6_3_119") (pintype "bidirectional"))
    )
    (net (code "275") (name "X_B_HLFB_OUT") (class "Default")
      (node (ref "J14") (pin "5") (pinfunction "5-HLFB-_5") (pintype "passive"))
    )
    (net (code "276") (name "X_B_MI_DIR") (class "Default")
      (node (ref "J14") (pin "7") (pinfunction "7-INPUT_A-_7") (pintype "passive"))
      (node (ref "R47") (pin "1") (pinfunction "1_1") (pintype "passive"))
      (node (ref "U14") (pin "3") (pinfunction "C(3)_3") (pintype "input"))
    )
    (net (code "277") (name "X_B_MI_ENABLE") (class "Default")
      (node (ref "J14") (pin "8") (pinfunction "8-ENABLE-_8") (pintype "passive"))
      (node (ref "R48") (pin "1") (pinfunction "1_1") (pintype "passive"))
      (node (ref "U15") (pin "3") (pinfunction "C(3)_3") (pintype "input"))
    )
    (net (code "278") (name "X_B_MI_STEP") (class "Default")
      (node (ref "J14") (pin "6") (pinfunction "6-INPUT_B-_6") (pintype "passive"))
      (node (ref "R43") (pin "1") (pinfunction "1_1") (pintype "passive"))
      (node (ref "U13") (pin "3") (pinfunction "C(3)_3") (pintype "input"))
    )
    (net (code "279") (name "X_B_STEP") (class "Default")
      (node (ref "R44") (pin "1") (pinfunction "1_1") (pintype "passive"))
      (node (ref "U3") (pin "121") (pinfunction "P6_1_121") (pintype "bidirectional"))
    )
    (net (code "280") (name "Y_A_DIR") (class "Default")
      (node (ref "R63") (pin "1") (pinfunction "1_1") (pintype "passive"))
      (node (ref "U3") (pin "114") (pinfunction "PA_0_114") (pintype "bidirectional"))
    )
    (net (code "281") (name "Y_A_ENABLE") (class "Default")
      (node (ref "R64") (pin "1") (pinfunction "1_1") (pintype "passive"))
      (node (ref "U3") (pin "113") (pinfunction "PA_1_113") (pintype "bidirectional"))
    )
    (net (code "282") (name "Y_A_HLFB_OUT") (class "Default")
      (node (ref "J17") (pin "5") (pinfunction "5-HLFB-_5") (pintype "passive"))
    )
    (net (code "283") (name "Y_A_MI_DIR") (class "Default")
      (node (ref "J17") (pin "7") (pinfunction "7-INPUT_A-_7") (pintype "passive"))
      (node (ref "R65") (pin "1") (pinfunction "1_1") (pintype "passive"))
      (node (ref "U23") (pin "3") (pinfunction "C(3)_3") (pintype "input"))
    )
    (net (code "284") (name "Y_A_MI_ENABLE") (class "Default")
      (node (ref "J17") (pin "8") (pinfunction "8-ENABLE-_8") (pintype "passive"))
      (node (ref "R66") (pin "1") (pinfunction "1_1") (pintype "passive"))
      (node (ref "U24") (pin "3") (pinfunction "C(3)_3") (pintype "input"))
    )
    (net (code "285") (name "Y_A_MI_STEP") (class "Default")
      (node (ref "J17") (pin "6") (pinfunction "6-INPUT_B-_6") (pintype "passive"))
      (node (ref "R61") (pin "1") (pinfunction "1_1") (pintype "passive"))
      (node (ref "U22") (pin "3") (pinfunction "C(3)_3") (pintype "input"))
    )
    (net (code "286") (name "Y_A_STEP") (class "Default")
      (node (ref "R62") (pin "1") (pinfunction "1_1") (pintype "passive"))
      (node (ref "U3") (pin "115") (pinfunction "P6_7_115") (pintype "bidirectional"))
    )
    (net (code "287") (name "Y_B_DIR") (class "Default")
      (node (ref "R69") (pin "1") (pinfunction "1_1") (pintype "passive"))
      (node (ref "U3") (pin "108") (pinfunction "PA_9_108") (pintype "bidirectional"))
    )
    (net (code "288") (name "Y_B_ENABLE") (class "Default")
      (node (ref "R70") (pin "1") (pinfunction "1_1") (pintype "passive"))
      (node (ref "U3") (pin "107") (pinfunction "PA_8_107") (pintype "bidirectional"))
    )
    (net (code "289") (name "Y_B_HLFB_OUT") (class "Default")
      (node (ref "J18") (pin "5") (pinfunction "5-HLFB-_5") (pintype "passive"))
    )
    (net (code "290") (name "Y_B_MI_DIR") (class "Default")
      (node (ref "J18") (pin "7") (pinfunction "7-INPUT_A-_7") (pintype "passive"))
      (node (ref "R71") (pin "1") (pinfunction "1_1") (pintype "passive"))
      (node (ref "U26") (pin "3") (pinfunction "C(3)_3") (pintype "input"))
    )
    (net (code "291") (name "Y_B_MI_ENABLE") (class "Default")
      (node (ref "J18") (pin "8") (pinfunction "8-ENABLE-_8") (pintype "passive"))
      (node (ref "R72") (pin "1") (pinfunction "1_1") (pintype "passive"))
      (node (ref "U27") (pin "3") (pinfunction "C(3)_3") (pintype "input"))
    )
    (net (code "292") (name "Y_B_MI_STEP") (class "Default")
      (node (ref "J18") (pin "6") (pinfunction "6-INPUT_B-_6") (pintype "passive"))
      (node (ref "R67") (pin "1") (pinfunction "1_1") (pintype "passive"))
      (node (ref "U25") (pin "3") (pinfunction "C(3)_3") (pintype "input"))
    )
    (net (code "293") (name "Y_B_STEP") (class "Default")
      (node (ref "R68") (pin "1") (pinfunction "1_1") (pintype "passive"))
      (node (ref "U3") (pin "109") (pinfunction "PA_10_109") (pintype "bidirectional"))
    )
    (net (code "294") (name "Z_A_DIR") (class "Default")
      (node (ref "R87") (pin "1") (pinfunction "1_1") (pintype "passive"))
      (node (ref "U3") (pin "105") (pinfunction "P6_14_105") (pintype "bidirectional"))
    )
    (net (code "295") (name "Z_A_ENABLE") (class "Default")
      (node (ref "R88") (pin "1") (pinfunction "1_1") (pintype "passive"))
      (node (ref "U3") (pin "104") (pinfunction "P6_13_104") (pintype "bidirectional"))
    )
    (net (code "296") (name "Z_A_HLFB_OUT") (class "Default")
      (node (ref "J21") (pin "5") (pinfunction "5-HLFB-_5") (pintype "passive"))
    )
    (net (code "297") (name "Z_A_MI_DIR") (class "Default")
      (node (ref "J21") (pin "7") (pinfunction "7-INPUT_A-_7") (pintype "passive"))
      (node (ref "R89") (pin "1") (pinfunction "1_1") (pintype "passive"))
      (node (ref "U35") (pin "3") (pinfunction "C(3)_3") (pintype "input"))
    )
    (net (code "298") (name "Z_A_MI_ENABLE") (class "Default")
      (node (ref "J21") (pin "8") (pinfunction "8-ENABLE-_8") (pintype "passive"))
      (node (ref "R90") (pin "1") (pinfunction "1_1") (pintype "passive"))
      (node (ref "U36") (pin "3") (pinfunction "C(3)_3") (pintype "input"))
    )
    (net (code "299") (name "Z_A_MI_STEP") (class "Default")
      (node (ref "J21") (pin "6") (pinfunction "6-INPUT_B-_6") (pintype "passive"))
      (node (ref "R85") (pin "1") (pinfunction "1_1") (pintype "passive"))
      (node (ref "U34") (pin "3") (pinfunction "C(3)_3") (pintype "input"))
    )
    (net (code "300") (name "Z_A_STEP") (class "Default")
      (node (ref "R86") (pin "1") (pinfunction "1_1") (pintype "passive"))
      (node (ref "U3") (pin "106") (pinfunction "P6_15_106") (pintype "bidirectional"))
    )
    (net (code "301") (name "Z_B_DIR") (class "Default")
      (node (ref "R93") (pin "1") (pinfunction "1_1") (pintype "passive"))
      (node (ref "U3") (pin "102") (pinfunction "P6_11_102") (pintype "bidirectional"))
    )
    (net (code "302") (name "Z_B_ENABLE") (class "Default")
      (node (ref "R94") (pin "1") (pinfunction "1_1") (pintype "passive"))
      (node (ref "U3") (pin "101") (pinfunction "P6_10_101") (pintype "bidirectional"))
    )
    (net (code "303") (name "Z_B_HLFB_OUT") (class "Default")
      (node (ref "J22") (pin "5") (pinfunction "5-HLFB-_5") (pintype "passive"))
    )
    (net (code "304") (name "Z_B_MI_DIR") (class "Default")
      (node (ref "J22") (pin "7") (pinfunction "7-INPUT_A-_7") (pintype "passive"))
      (node (ref "R95") (pin "1") (pinfunction "1_1") (pintype "passive"))
      (node (ref "U38") (pin "3") (pinfunction "C(3)_3") (pintype "input"))
    )
    (net (code "305") (name "Z_B_MI_ENABLE") (class "Default")
      (node (ref "J22") (pin "8") (pinfunction "8-ENABLE-_8") (pintype "passive"))
      (node (ref "R96") (pin "1") (pinfunction "1_1") (pintype "passive"))
      (node (ref "U39") (pin "3") (pinfunction "C(3)_3") (pintype "input"))
    )
    (net (code "306") (name "Z_B_MI_STEP") (class "Default")
      (node (ref "J22") (pin "6") (pinfunction "6-INPUT_B-_6") (pintype "passive"))
      (node (ref "R91") (pin "1") (pinfunction "1_1") (pintype "passive"))
      (node (ref "U37") (pin "3") (pinfunction "C(3)_3") (pintype "input"))
    )
    (net (code "307") (name "Z_B_STEP") (class "Default")
      (node (ref "R92") (pin "1") (pinfunction "1_1") (pintype "passive"))
      (node (ref "U3") (pin "103") (pinfunction "P6_12_103") (pintype "bidirectional"))
    )
    (net (code "308") (name "unconnected-(U3-VBAT-Pad18)") (class "Default")
      (node (ref "U3") (pin "18") (pinfunction "VBAT_18") (pintype "bidirectional"))
    )
  )
)
